# ProPrj_MN42_v2_2026-01-12.net
KiCad netlist of a schematic drawn in EasyEDA Pro
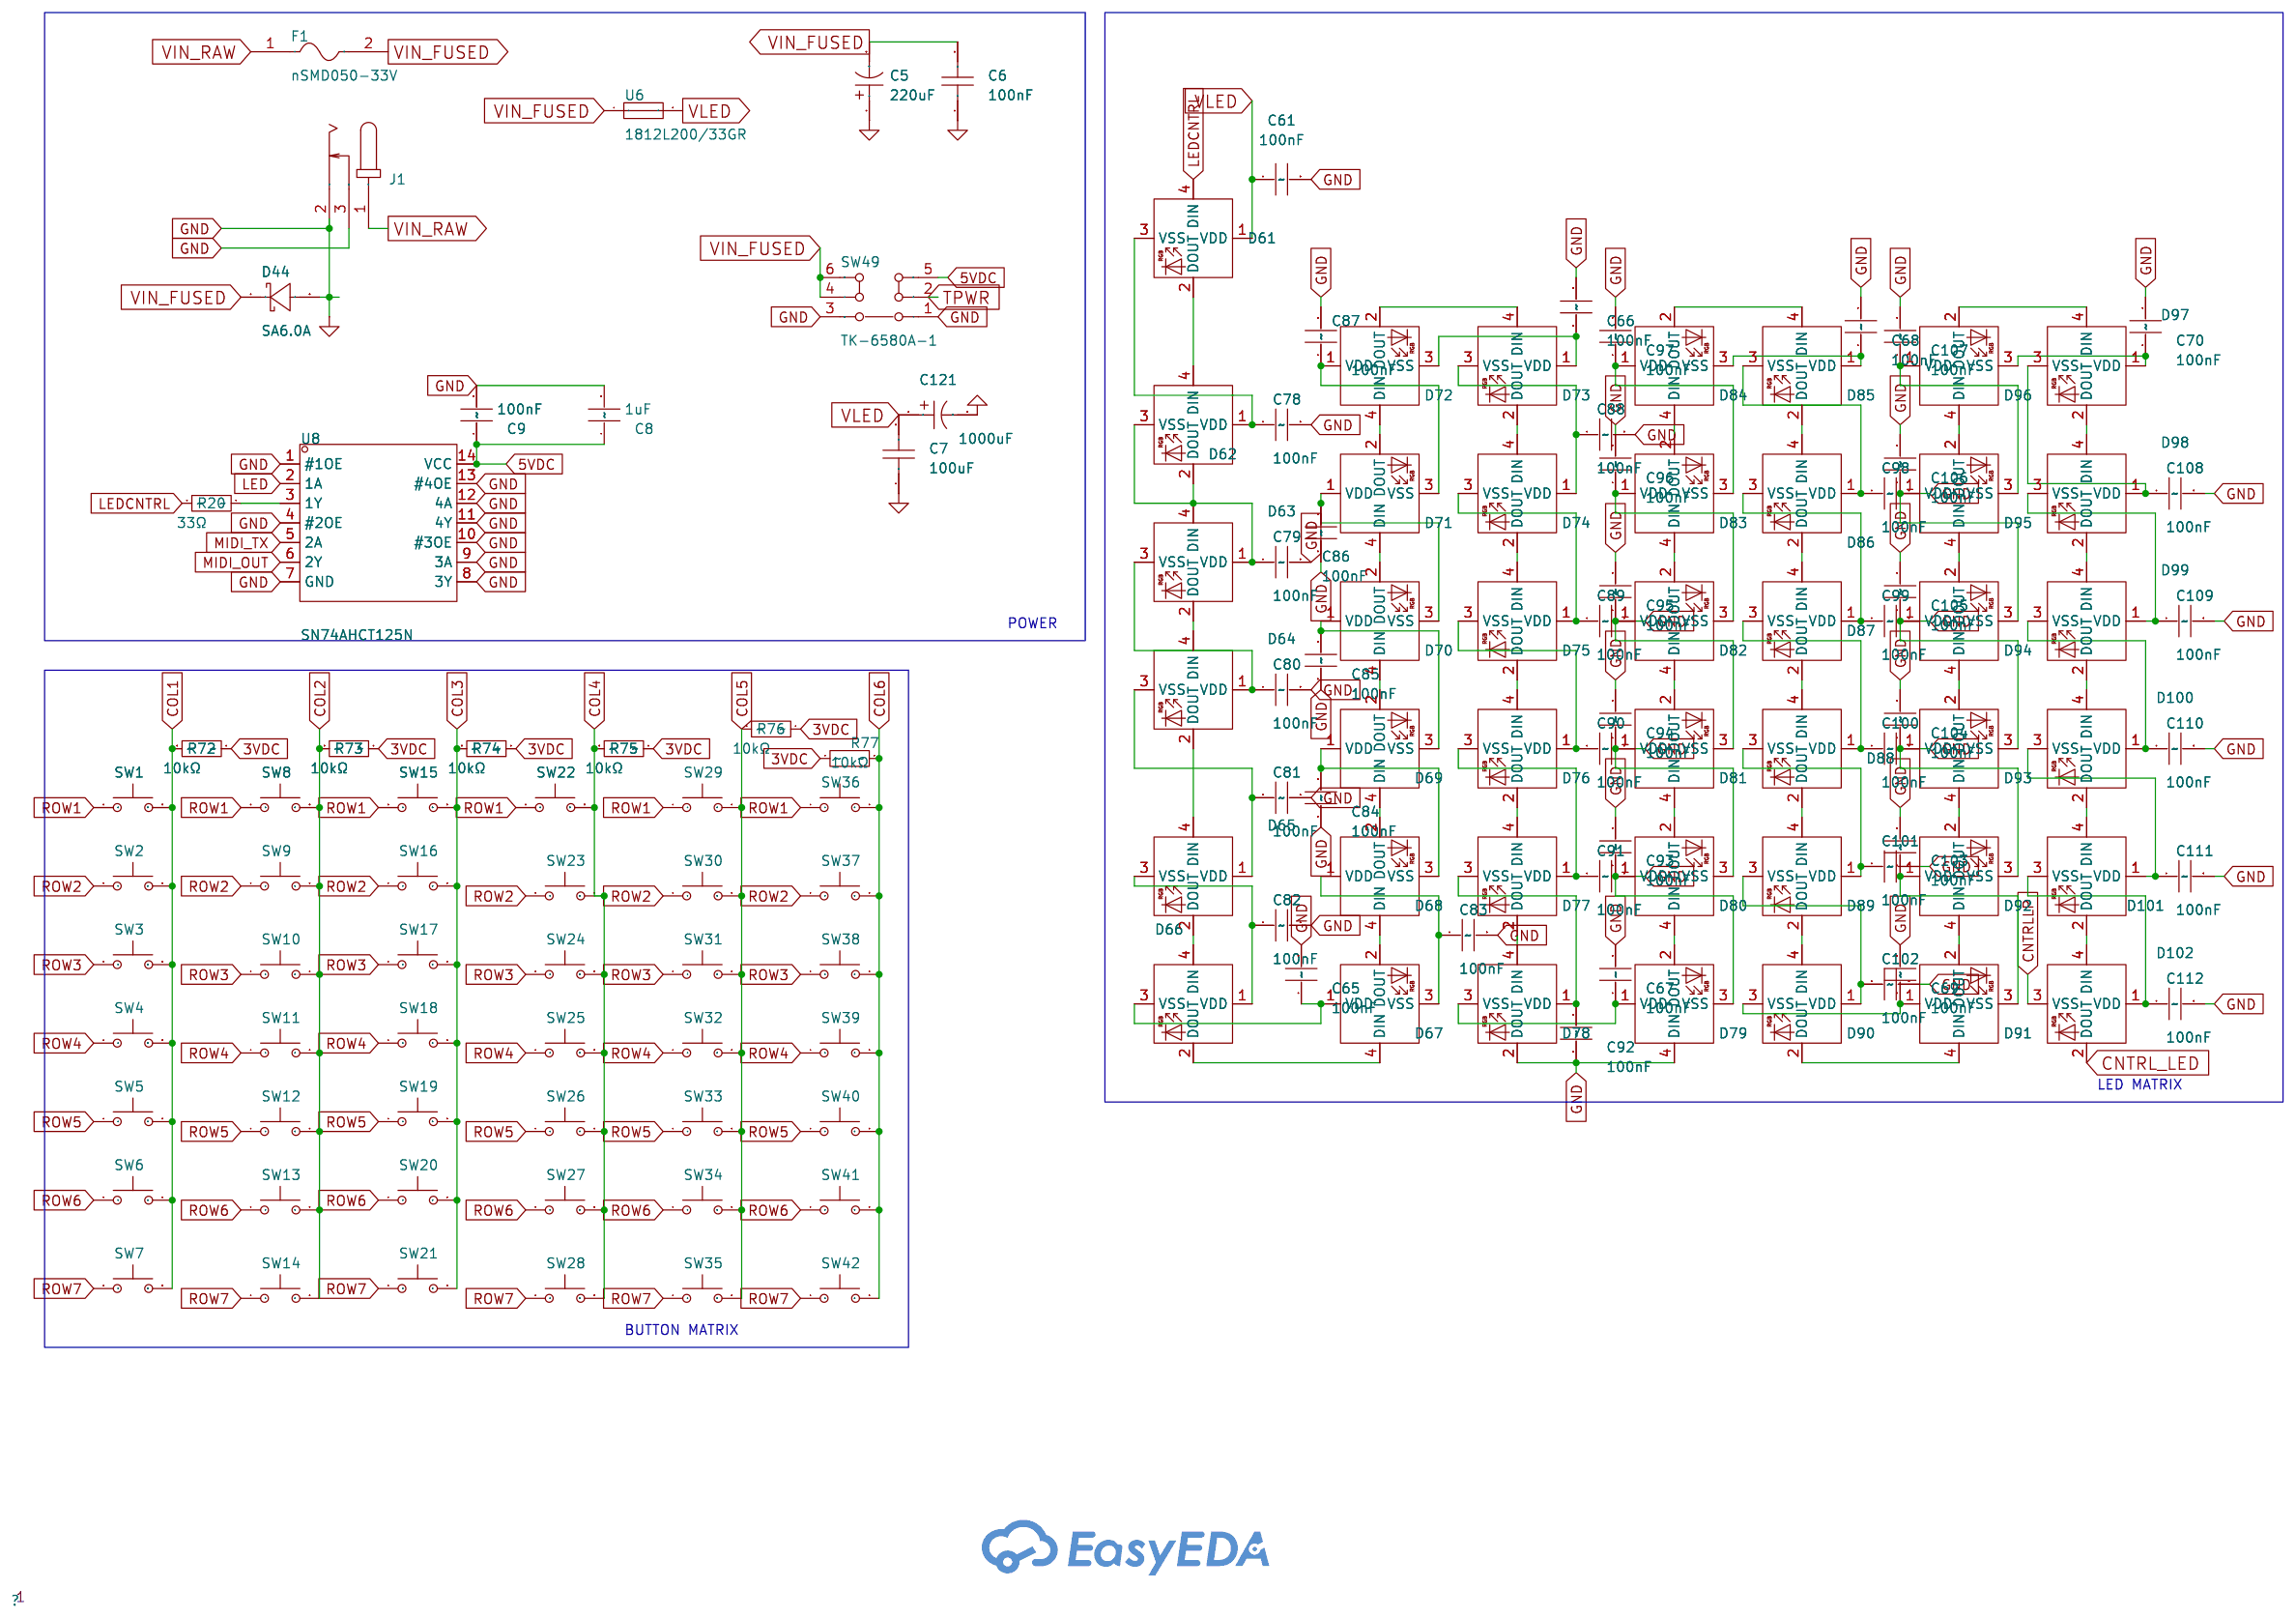
[diagram p0: PWR/BUTTON/LED]
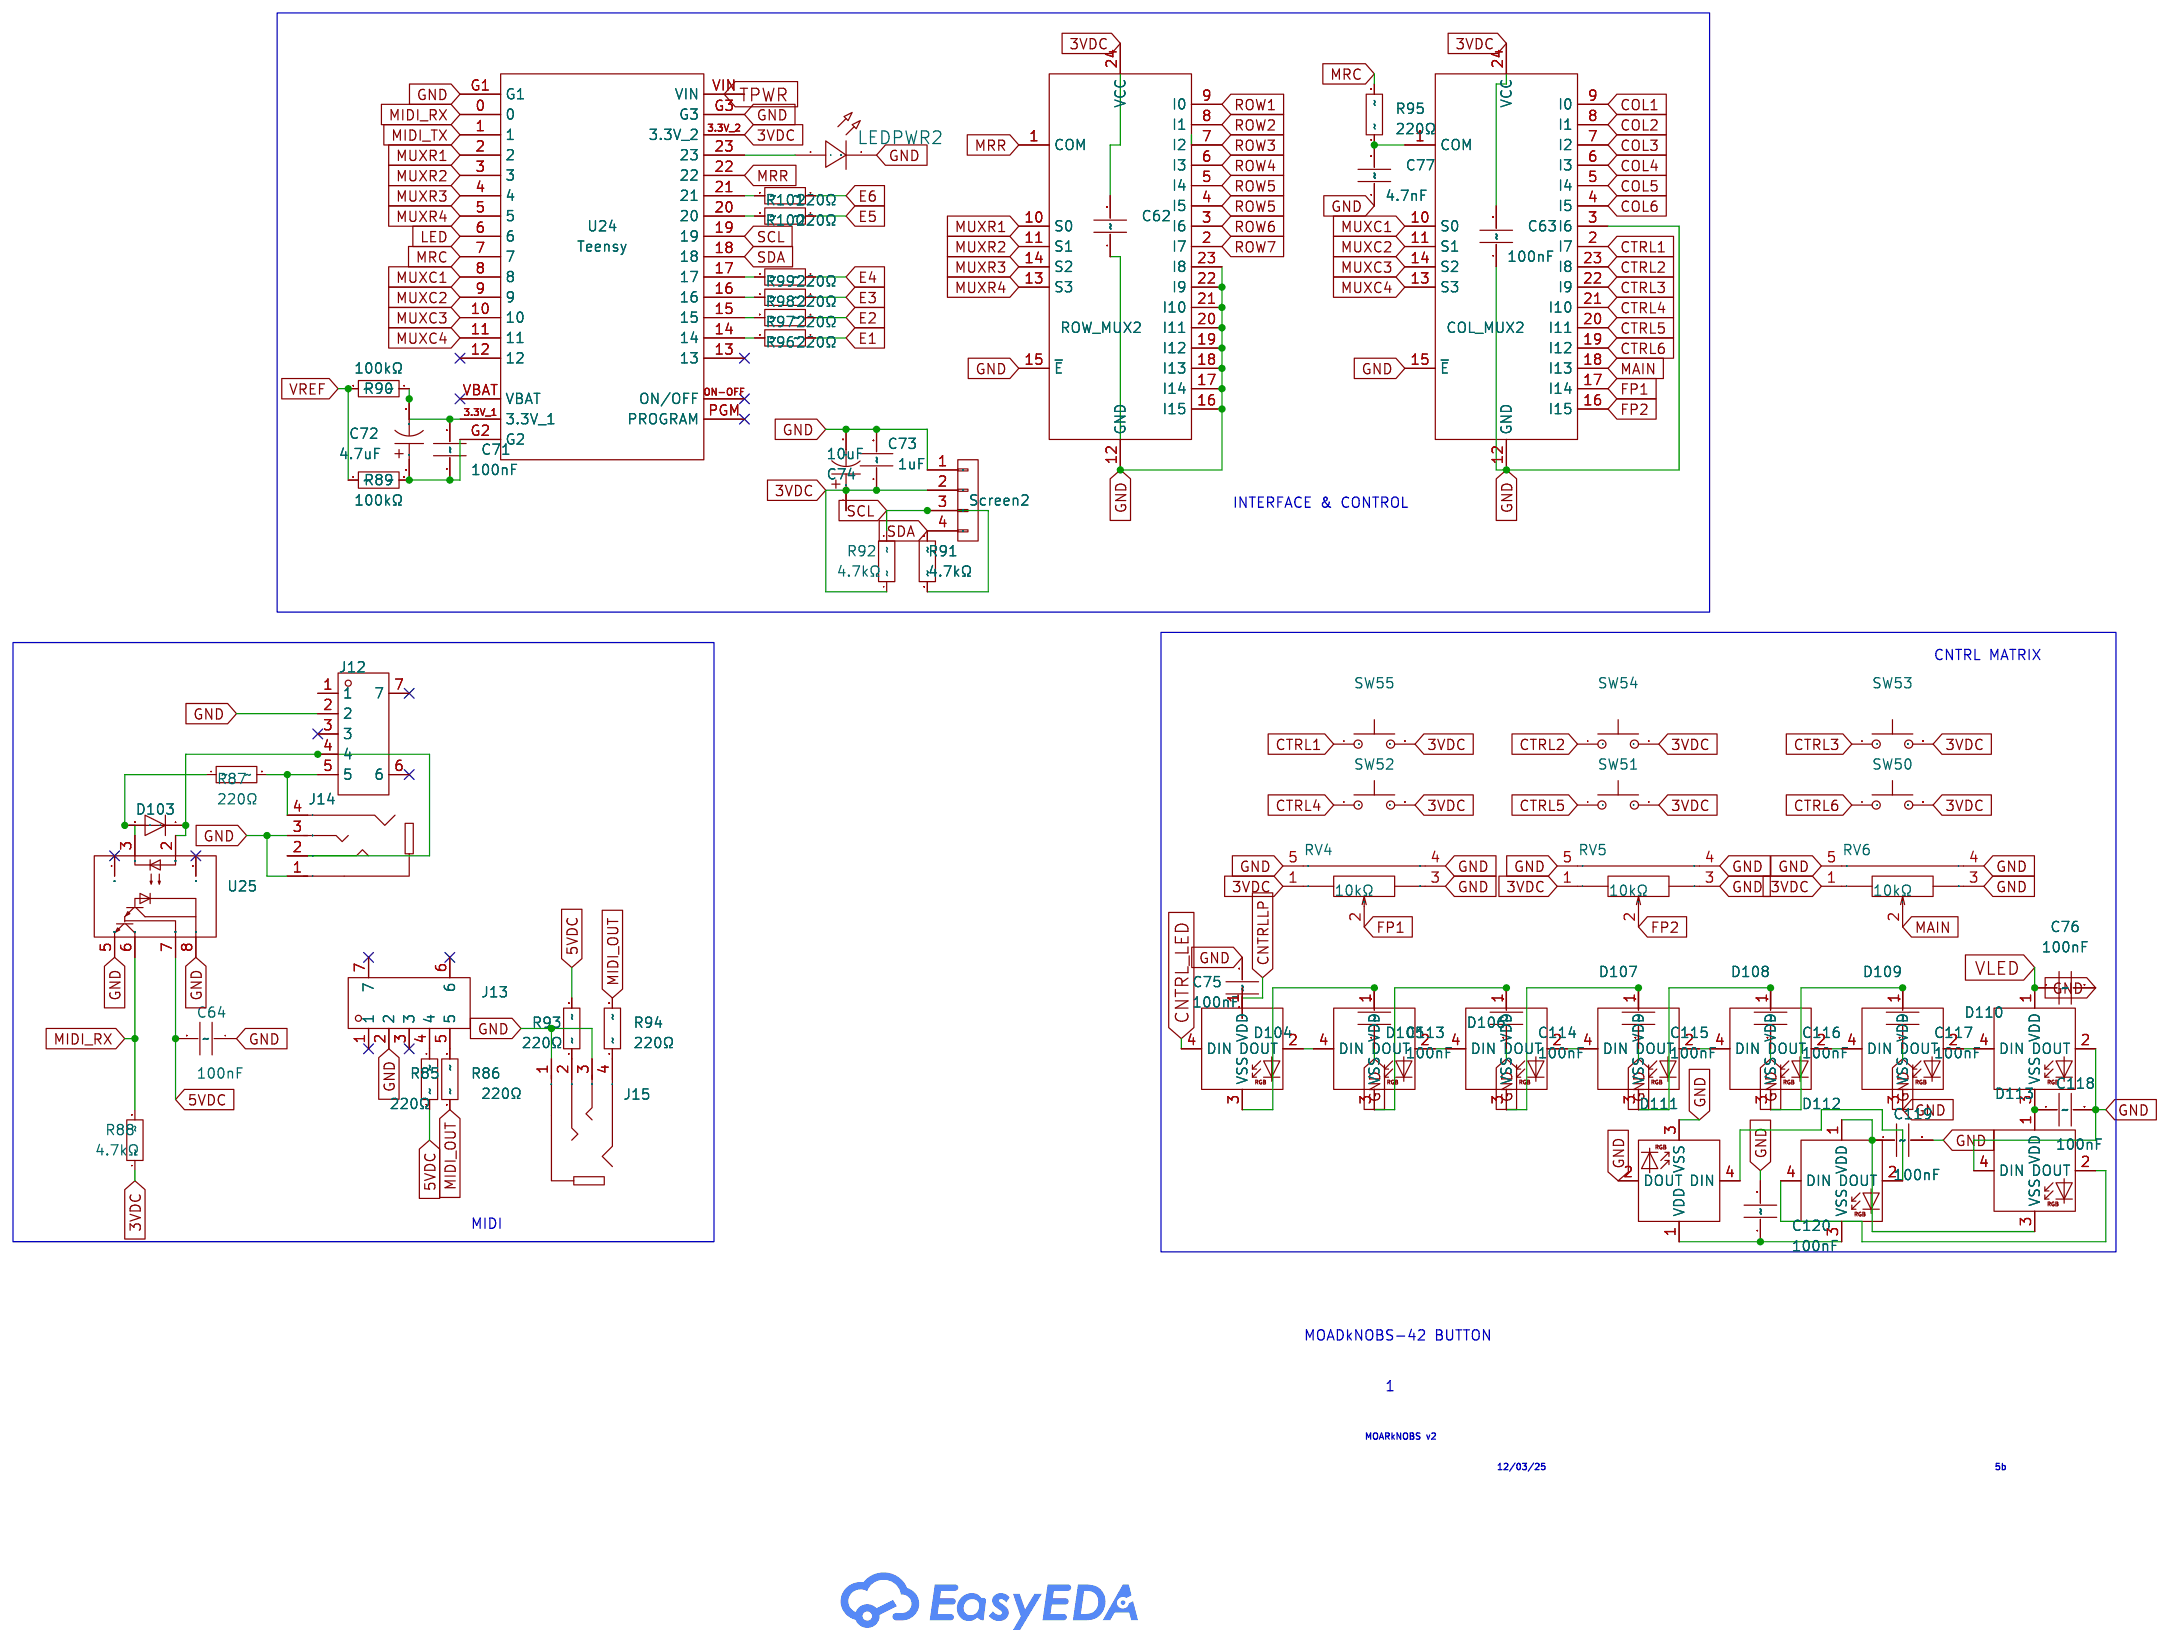
[diagram p1: INTERFACE/MIDI/CNTRL]
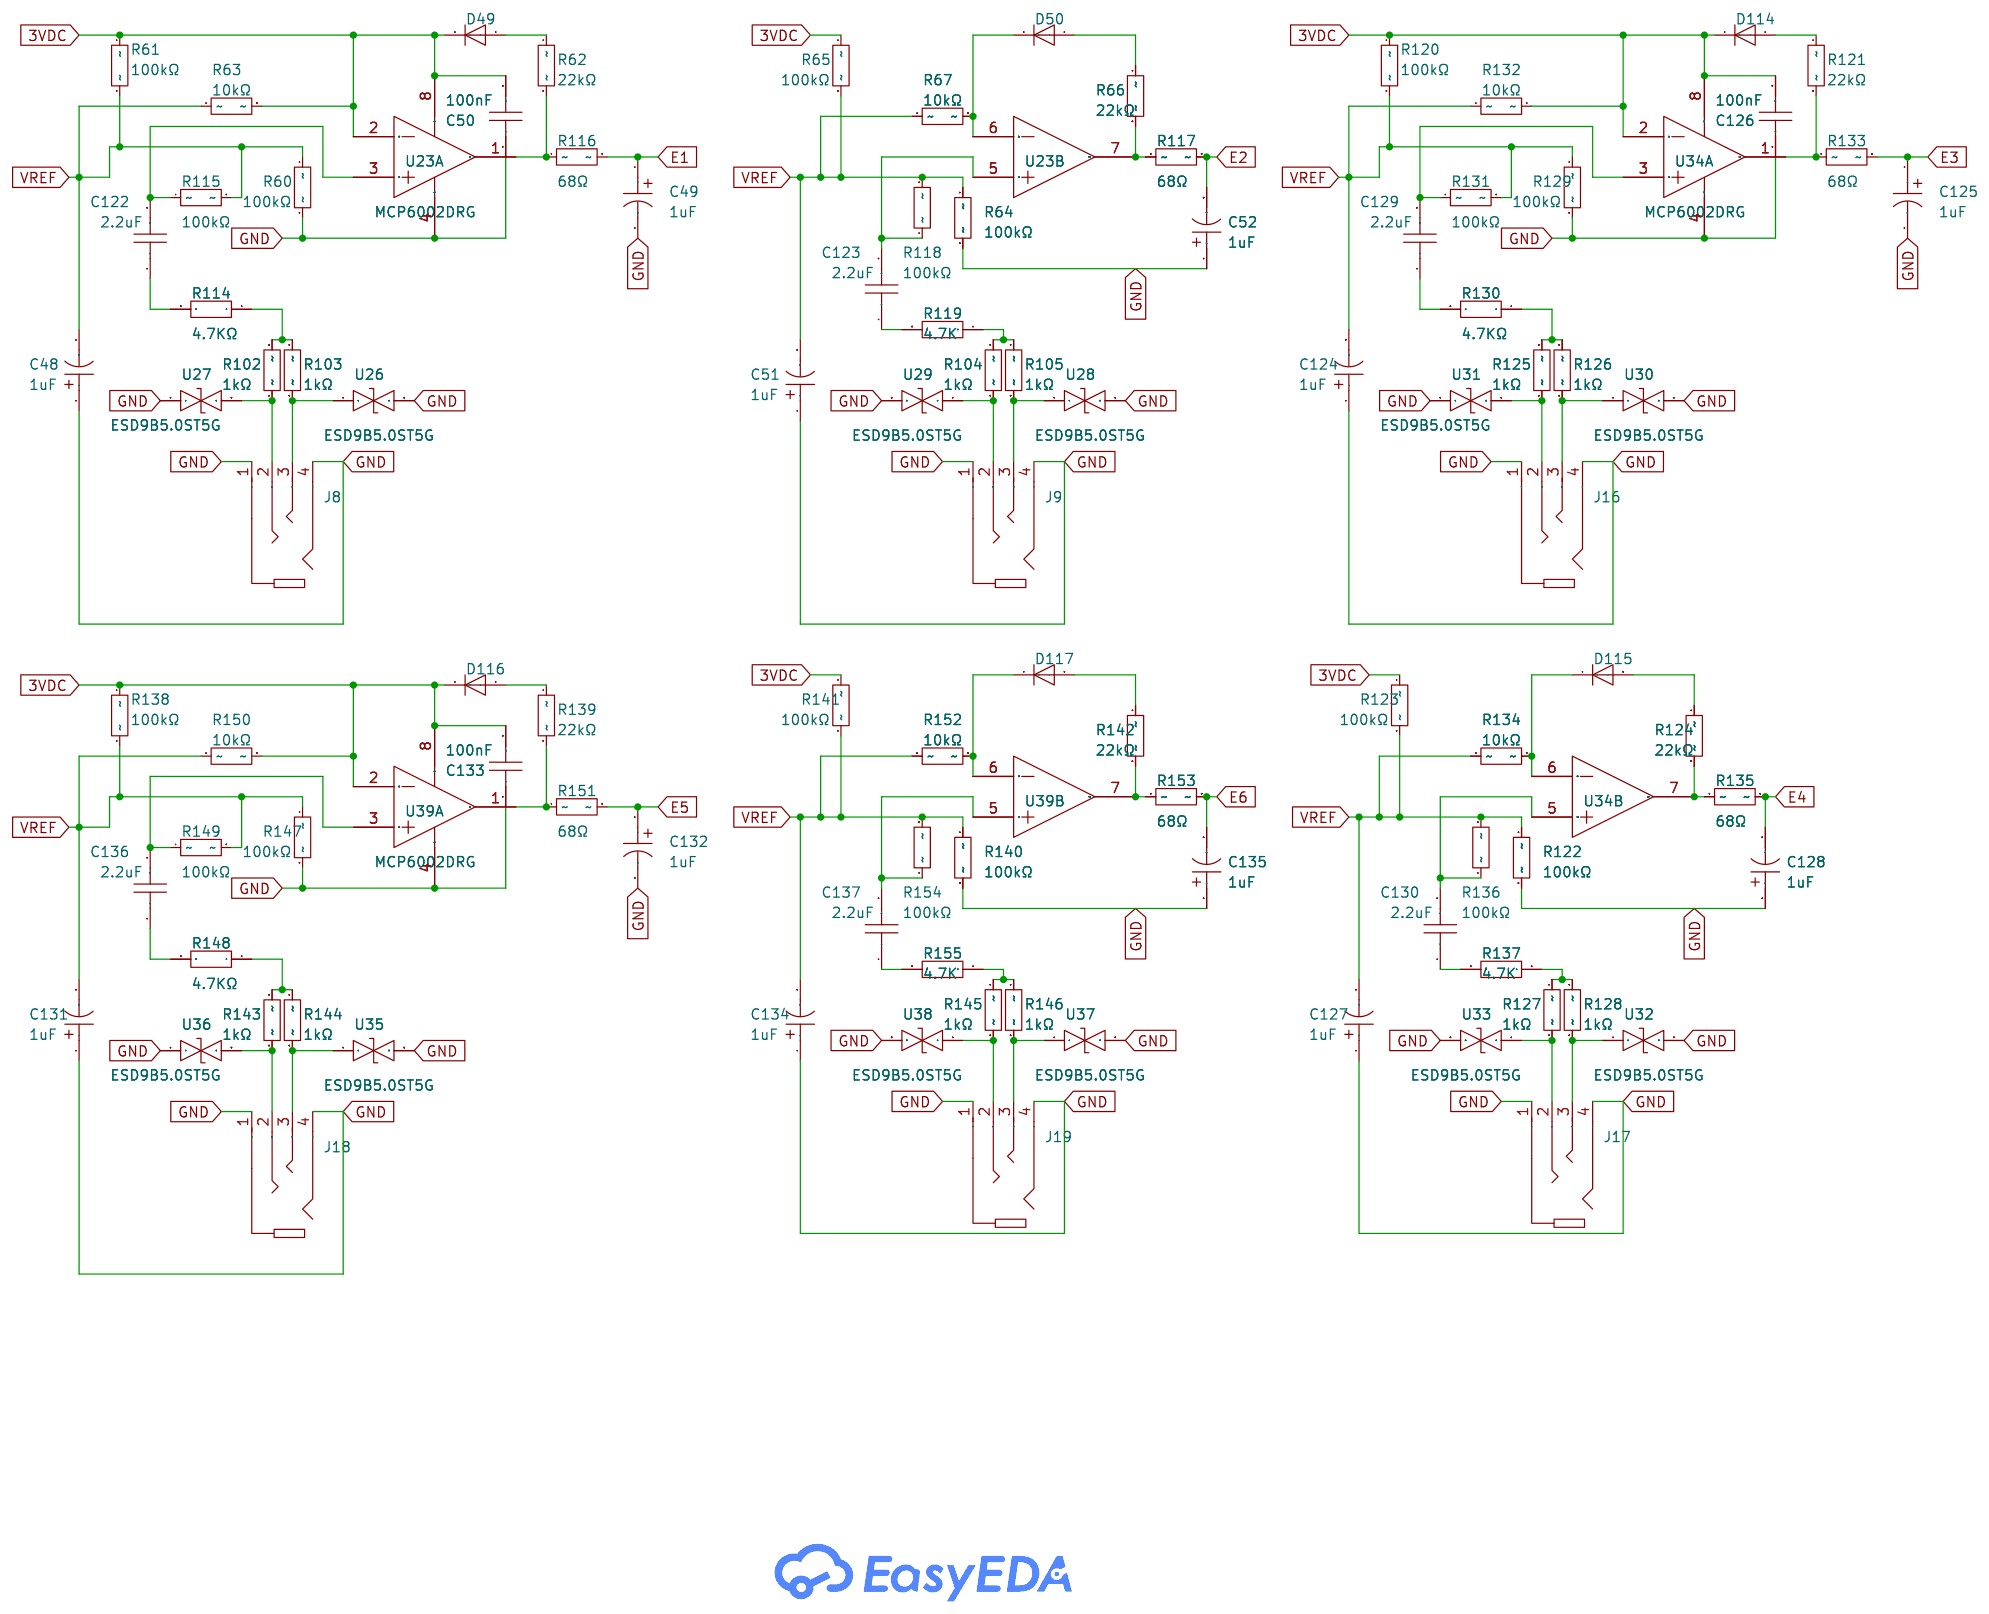
[diagram p2: ENVELOPE]

(export (version "E")
  (design (tool "Eeschema 10.0.6"))
  (components
    (comp (ref "C5")
      (value "220uF")
      (footprint "easyedapro:CAP-SMD_BD6.3-L6.6-W6.6-FD")
      (fields (field (name "Manufacturer Part") "189RV0019") (field (name "Manufacturer") "KNSCHA(科尼盛)"))
      (libsource (lib "easyedapro") (part "189RV0019"))
    )
    (comp (ref "C6")
      (value "100nF")
      (footprint "easyedapro:CAP-TH_L5.0-W2.5-P5.00-D1.0")
      (fields
        (field (name "Manufacturer Part") "CC1H104MC1FD3F6C10MF")
        (field (name "Manufacturer") "Dersonic(德尔创)")
      )
      (libsource (lib "easyedapro") (part "CC1H104MC1FD3F6C10MF"))
    )
    (comp (ref "C7")
      (value "100uF")
      (footprint "easyedapro:C1206")
      (description "Capacitance:100uF Tolerance:±20% Tolerance:±20% Voltage Rating:10V Temperature Coefficient:X5R")
      (fields
        (field (name "Manufacturer Part") "HGC1206R5107M100NSPJ")
        (field (name "Manufacturer") "Chinocera(华瓷)")
      )
      (libsource (lib "easyedapro") (part "HGC1206R5107M100NSPJ"))
    )
    (comp (ref "C8")
      (value "1uF")
      (footprint "easyedapro:Capacitor_THT:C_Disc_D3.4mm_W2.1mm_P2.50mm")
      (description "Capacitance:100nF Tolerance:±10% Tolerance:±10% Voltage Rating:63V Temperature Coefficient:-")
      (fields
        (field (name "Manufacturer Part") "CT4G-0805-2X1-63V-0.1μF-K")
        (field (name "Manufacturer") "TORCH(火炬)")
      )
      (libsource (lib "easyedapro") (part "Device_C"))
    )
    (comp (ref "C9")
      (value "100nF")
      (footprint "easyedapro:Capacitor_THT:C_Disc_D3.4mm_W2.1mm_P2.50mm")
      (description "Capacitance:100nF Tolerance:±10% Tolerance:±10% Voltage Rating:50V Temperature Coefficient:X7R")
      (fields
        (field (name "Manufacturer Part") "TCC0603X7R104K500CT")
        (field (name "Manufacturer") "CCTC(三环)")
      )
      (libsource (lib "easyedapro") (part "Device_C"))
    )
    (comp (ref "C61")
      (value "100nF")
      (footprint "easyedapro:Capacitor_THT:C_Disc_D3.4mm_W2.1mm_P2.50mm")
      (description "Capacitance:100nF Tolerance:±10% Tolerance:±10% Voltage Rating:50V Temperature Coefficient:X7R")
      (fields
        (field (name "Manufacturer Part") "TCC0603X7R104K500CT")
        (field (name "Manufacturer") "CCTC(三环)")
      )
      (libsource (lib "easyedapro") (part "Device_C"))
    )
    (comp (ref "C65")
      (value "100nF")
      (footprint "easyedapro:Capacitor_THT:C_Disc_D3.4mm_W2.1mm_P2.50mm")
      (description "Capacitance:100nF Tolerance:±10% Tolerance:±10% Voltage Rating:50V Temperature Coefficient:X7R")
      (fields
        (field (name "Manufacturer Part") "TCC0603X7R104K500CT")
        (field (name "Manufacturer") "CCTC(三环)")
      )
      (libsource (lib "easyedapro") (part "Device_C"))
    )
    (comp (ref "C66")
      (value "100nF")
      (footprint "easyedapro:Capacitor_THT:C_Disc_D3.4mm_W2.1mm_P2.50mm")
      (description "Capacitance:100nF Tolerance:±10% Tolerance:±10% Voltage Rating:50V Temperature Coefficient:X7R")
      (fields
        (field (name "Manufacturer Part") "TCC0603X7R104K500CT")
        (field (name "Manufacturer") "CCTC(三环)")
      )
      (libsource (lib "easyedapro") (part "Device_C"))
    )
    (comp (ref "C67")
      (value "100nF")
      (footprint "easyedapro:Capacitor_THT:C_Disc_D3.4mm_W2.1mm_P2.50mm")
      (description "Capacitance:100nF Tolerance:±10% Tolerance:±10% Voltage Rating:50V Temperature Coefficient:X7R")
      (fields
        (field (name "Manufacturer Part") "TCC0603X7R104K500CT")
        (field (name "Manufacturer") "CCTC(三环)")
      )
      (libsource (lib "easyedapro") (part "Device_C"))
    )
    (comp (ref "C68")
      (value "100nF")
      (footprint "easyedapro:Capacitor_THT:C_Disc_D3.4mm_W2.1mm_P2.50mm")
      (description "Capacitance:100nF Tolerance:±10% Tolerance:±10% Voltage Rating:50V Temperature Coefficient:X7R")
      (fields
        (field (name "Manufacturer Part") "TCC0603X7R104K500CT")
        (field (name "Manufacturer") "CCTC(三环)")
      )
      (libsource (lib "easyedapro") (part "Device_C"))
    )
    (comp (ref "C69")
      (value "100nF")
      (footprint "easyedapro:Capacitor_THT:C_Disc_D3.4mm_W2.1mm_P2.50mm")
      (description "Capacitance:100nF Tolerance:±10% Tolerance:±10% Voltage Rating:50V Temperature Coefficient:X7R")
      (fields
        (field (name "Manufacturer Part") "TCC0603X7R104K500CT")
        (field (name "Manufacturer") "CCTC(三环)")
      )
      (libsource (lib "easyedapro") (part "Device_C"))
    )
    (comp (ref "C70")
      (value "100nF")
      (footprint "easyedapro:Capacitor_THT:C_Disc_D3.4mm_W2.1mm_P2.50mm")
      (description "Capacitance:100nF Tolerance:±10% Tolerance:±10% Voltage Rating:50V Temperature Coefficient:X7R")
      (fields
        (field (name "Manufacturer Part") "TCC0603X7R104K500CT")
        (field (name "Manufacturer") "CCTC(三环)")
      )
      (libsource (lib "easyedapro") (part "Device_C"))
    )
    (comp (ref "C78")
      (value "100nF")
      (footprint "easyedapro:Capacitor_THT:C_Disc_D3.4mm_W2.1mm_P2.50mm")
      (description "Capacitance:100nF Tolerance:±10% Tolerance:±10% Voltage Rating:50V Temperature Coefficient:X7R")
      (fields
        (field (name "Manufacturer Part") "TCC0603X7R104K500CT")
        (field (name "Manufacturer") "CCTC(三环)")
      )
      (libsource (lib "easyedapro") (part "Device_C"))
    )
    (comp (ref "C79")
      (value "100nF")
      (footprint "easyedapro:Capacitor_THT:C_Disc_D3.4mm_W2.1mm_P2.50mm")
      (description "Capacitance:100nF Tolerance:±10% Tolerance:±10% Voltage Rating:50V Temperature Coefficient:X7R")
      (fields
        (field (name "Manufacturer Part") "TCC0603X7R104K500CT")
        (field (name "Manufacturer") "CCTC(三环)")
      )
      (libsource (lib "easyedapro") (part "Device_C"))
    )
    (comp (ref "C80")
      (value "100nF")
      (footprint "easyedapro:Capacitor_THT:C_Disc_D3.4mm_W2.1mm_P2.50mm")
      (description "Capacitance:100nF Tolerance:±10% Tolerance:±10% Voltage Rating:50V Temperature Coefficient:X7R")
      (fields
        (field (name "Manufacturer Part") "TCC0603X7R104K500CT")
        (field (name "Manufacturer") "CCTC(三环)")
      )
      (libsource (lib "easyedapro") (part "Device_C"))
    )
    (comp (ref "C81")
      (value "100nF")
      (footprint "easyedapro:Capacitor_THT:C_Disc_D3.4mm_W2.1mm_P2.50mm")
      (description "Capacitance:100nF Tolerance:±10% Tolerance:±10% Voltage Rating:50V Temperature Coefficient:X7R")
      (fields
        (field (name "Manufacturer Part") "TCC0603X7R104K500CT")
        (field (name "Manufacturer") "CCTC(三环)")
      )
      (libsource (lib "easyedapro") (part "Device_C"))
    )
    (comp (ref "C82")
      (value "100nF")
      (footprint "easyedapro:Capacitor_THT:C_Disc_D3.4mm_W2.1mm_P2.50mm")
      (description "Capacitance:100nF Tolerance:±10% Tolerance:±10% Voltage Rating:50V Temperature Coefficient:X7R")
      (fields
        (field (name "Manufacturer Part") "TCC0603X7R104K500CT")
        (field (name "Manufacturer") "CCTC(三环)")
      )
      (libsource (lib "easyedapro") (part "Device_C"))
    )
    (comp (ref "C83")
      (value "100nF")
      (footprint "easyedapro:Capacitor_THT:C_Disc_D3.4mm_W2.1mm_P2.50mm")
      (description "Capacitance:100nF Tolerance:±10% Tolerance:±10% Voltage Rating:50V Temperature Coefficient:X7R")
      (fields
        (field (name "Manufacturer Part") "TCC0603X7R104K500CT")
        (field (name "Manufacturer") "CCTC(三环)")
      )
      (libsource (lib "easyedapro") (part "Device_C"))
    )
    (comp (ref "C84")
      (value "100nF")
      (footprint "easyedapro:Capacitor_THT:C_Disc_D3.4mm_W2.1mm_P2.50mm")
      (description "Capacitance:100nF Tolerance:±10% Tolerance:±10% Voltage Rating:50V Temperature Coefficient:X7R")
      (fields
        (field (name "Manufacturer Part") "TCC0603X7R104K500CT")
        (field (name "Manufacturer") "CCTC(三环)")
      )
      (libsource (lib "easyedapro") (part "Device_C"))
    )
    (comp (ref "C85")
      (value "100nF")
      (footprint "easyedapro:Capacitor_THT:C_Disc_D3.4mm_W2.1mm_P2.50mm")
      (description "Capacitance:100nF Tolerance:±10% Tolerance:±10% Voltage Rating:50V Temperature Coefficient:X7R")
      (fields
        (field (name "Manufacturer Part") "TCC0603X7R104K500CT")
        (field (name "Manufacturer") "CCTC(三环)")
      )
      (libsource (lib "easyedapro") (part "Device_C"))
    )
    (comp (ref "C86")
      (value "100nF")
      (footprint "easyedapro:Capacitor_THT:C_Disc_D3.4mm_W2.1mm_P2.50mm")
      (description "Capacitance:100nF Tolerance:±10% Tolerance:±10% Voltage Rating:50V Temperature Coefficient:X7R")
      (fields
        (field (name "Manufacturer Part") "TCC0603X7R104K500CT")
        (field (name "Manufacturer") "CCTC(三环)")
      )
      (libsource (lib "easyedapro") (part "Device_C"))
    )
    (comp (ref "C87")
      (value "100nF")
      (footprint "easyedapro:Capacitor_THT:C_Disc_D3.4mm_W2.1mm_P2.50mm")
      (description "Capacitance:100nF Tolerance:±10% Tolerance:±10% Voltage Rating:50V Temperature Coefficient:X7R")
      (fields
        (field (name "Manufacturer Part") "TCC0603X7R104K500CT")
        (field (name "Manufacturer") "CCTC(三环)")
      )
      (libsource (lib "easyedapro") (part "Device_C"))
    )
    (comp (ref "C88")
      (value "100nF")
      (footprint "easyedapro:Capacitor_THT:C_Disc_D3.4mm_W2.1mm_P2.50mm")
      (description "Capacitance:100nF Tolerance:±10% Tolerance:±10% Voltage Rating:50V Temperature Coefficient:X7R")
      (fields
        (field (name "Manufacturer Part") "TCC0603X7R104K500CT")
        (field (name "Manufacturer") "CCTC(三环)")
      )
      (libsource (lib "easyedapro") (part "Device_C"))
    )
    (comp (ref "C89")
      (value "100nF")
      (footprint "easyedapro:Capacitor_THT:C_Disc_D3.4mm_W2.1mm_P2.50mm")
      (description "Capacitance:100nF Tolerance:±10% Tolerance:±10% Voltage Rating:50V Temperature Coefficient:X7R")
      (fields
        (field (name "Manufacturer Part") "TCC0603X7R104K500CT")
        (field (name "Manufacturer") "CCTC(三环)")
      )
      (libsource (lib "easyedapro") (part "Device_C"))
    )
    (comp (ref "C90")
      (value "100nF")
      (footprint "easyedapro:Capacitor_THT:C_Disc_D3.4mm_W2.1mm_P2.50mm")
      (description "Capacitance:100nF Tolerance:±10% Tolerance:±10% Voltage Rating:50V Temperature Coefficient:X7R")
      (fields
        (field (name "Manufacturer Part") "TCC0603X7R104K500CT")
        (field (name "Manufacturer") "CCTC(三环)")
      )
      (libsource (lib "easyedapro") (part "Device_C"))
    )
    (comp (ref "C91")
      (value "100nF")
      (footprint "easyedapro:Capacitor_THT:C_Disc_D3.4mm_W2.1mm_P2.50mm")
      (description "Capacitance:100nF Tolerance:±10% Tolerance:±10% Voltage Rating:50V Temperature Coefficient:X7R")
      (fields
        (field (name "Manufacturer Part") "TCC0603X7R104K500CT")
        (field (name "Manufacturer") "CCTC(三环)")
      )
      (libsource (lib "easyedapro") (part "Device_C"))
    )
    (comp (ref "C92")
      (value "100nF")
      (footprint "easyedapro:Capacitor_THT:C_Disc_D3.4mm_W2.1mm_P2.50mm")
      (description "Capacitance:100nF Tolerance:±10% Tolerance:±10% Voltage Rating:50V Temperature Coefficient:X7R")
      (fields
        (field (name "Manufacturer Part") "TCC0603X7R104K500CT")
        (field (name "Manufacturer") "CCTC(三环)")
      )
      (libsource (lib "easyedapro") (part "Device_C"))
    )
    (comp (ref "C93")
      (value "100nF")
      (footprint "easyedapro:Capacitor_THT:C_Disc_D3.4mm_W2.1mm_P2.50mm")
      (description "Capacitance:100nF Tolerance:±10% Tolerance:±10% Voltage Rating:50V Temperature Coefficient:X7R")
      (fields
        (field (name "Manufacturer Part") "TCC0603X7R104K500CT")
        (field (name "Manufacturer") "CCTC(三环)")
      )
      (libsource (lib "easyedapro") (part "Device_C"))
    )
    (comp (ref "C94")
      (value "100nF")
      (footprint "easyedapro:Capacitor_THT:C_Disc_D3.4mm_W2.1mm_P2.50mm")
      (description "Capacitance:100nF Tolerance:±10% Tolerance:±10% Voltage Rating:50V Temperature Coefficient:X7R")
      (fields
        (field (name "Manufacturer Part") "TCC0603X7R104K500CT")
        (field (name "Manufacturer") "CCTC(三环)")
      )
      (libsource (lib "easyedapro") (part "Device_C"))
    )
    (comp (ref "C95")
      (value "100nF")
      (footprint "easyedapro:Capacitor_THT:C_Disc_D3.4mm_W2.1mm_P2.50mm")
      (description "Capacitance:100nF Tolerance:±10% Tolerance:±10% Voltage Rating:50V Temperature Coefficient:X7R")
      (fields
        (field (name "Manufacturer Part") "TCC0603X7R104K500CT")
        (field (name "Manufacturer") "CCTC(三环)")
      )
      (libsource (lib "easyedapro") (part "Device_C"))
    )
    (comp (ref "C96")
      (value "100nF")
      (footprint "easyedapro:Capacitor_THT:C_Disc_D3.4mm_W2.1mm_P2.50mm")
      (description "Capacitance:100nF Tolerance:±10% Tolerance:±10% Voltage Rating:50V Temperature Coefficient:X7R")
      (fields
        (field (name "Manufacturer Part") "TCC0603X7R104K500CT")
        (field (name "Manufacturer") "CCTC(三环)")
      )
      (libsource (lib "easyedapro") (part "Device_C"))
    )
    (comp (ref "C97")
      (value "100nF")
      (footprint "easyedapro:Capacitor_THT:C_Disc_D3.4mm_W2.1mm_P2.50mm")
      (description "Capacitance:100nF Tolerance:±10% Tolerance:±10% Voltage Rating:50V Temperature Coefficient:X7R")
      (fields
        (field (name "Manufacturer Part") "TCC0603X7R104K500CT")
        (field (name "Manufacturer") "CCTC(三环)")
      )
      (libsource (lib "easyedapro") (part "Device_C"))
    )
    (comp (ref "C98")
      (value "100nF")
      (footprint "easyedapro:Capacitor_THT:C_Disc_D3.4mm_W2.1mm_P2.50mm")
      (description "Capacitance:100nF Tolerance:±10% Tolerance:±10% Voltage Rating:50V Temperature Coefficient:X7R")
      (fields
        (field (name "Manufacturer Part") "TCC0603X7R104K500CT")
        (field (name "Manufacturer") "CCTC(三环)")
      )
      (libsource (lib "easyedapro") (part "Device_C"))
    )
    (comp (ref "C99")
      (value "100nF")
      (footprint "easyedapro:Capacitor_THT:C_Disc_D3.4mm_W2.1mm_P2.50mm")
      (description "Capacitance:100nF Tolerance:±10% Tolerance:±10% Voltage Rating:50V Temperature Coefficient:X7R")
      (fields
        (field (name "Manufacturer Part") "TCC0603X7R104K500CT")
        (field (name "Manufacturer") "CCTC(三环)")
      )
      (libsource (lib "easyedapro") (part "Device_C"))
    )
    (comp (ref "C100")
      (value "100nF")
      (footprint "easyedapro:Capacitor_THT:C_Disc_D3.4mm_W2.1mm_P2.50mm")
      (description "Capacitance:100nF Tolerance:±10% Tolerance:±10% Voltage Rating:50V Temperature Coefficient:X7R")
      (fields
        (field (name "Manufacturer Part") "TCC0603X7R104K500CT")
        (field (name "Manufacturer") "CCTC(三环)")
      )
      (libsource (lib "easyedapro") (part "Device_C"))
    )
    (comp (ref "C101")
      (value "100nF")
      (footprint "easyedapro:Capacitor_THT:C_Disc_D3.4mm_W2.1mm_P2.50mm")
      (description "Capacitance:100nF Tolerance:±10% Tolerance:±10% Voltage Rating:50V Temperature Coefficient:X7R")
      (fields
        (field (name "Manufacturer Part") "TCC0603X7R104K500CT")
        (field (name "Manufacturer") "CCTC(三环)")
      )
      (libsource (lib "easyedapro") (part "Device_C"))
    )
    (comp (ref "C102")
      (value "100nF")
      (footprint "easyedapro:Capacitor_THT:C_Disc_D3.4mm_W2.1mm_P2.50mm")
      (description "Capacitance:100nF Tolerance:±10% Tolerance:±10% Voltage Rating:50V Temperature Coefficient:X7R")
      (fields
        (field (name "Manufacturer Part") "TCC0603X7R104K500CT")
        (field (name "Manufacturer") "CCTC(三环)")
      )
      (libsource (lib "easyedapro") (part "Device_C"))
    )
    (comp (ref "C103")
      (value "100nF")
      (footprint "easyedapro:Capacitor_THT:C_Disc_D3.4mm_W2.1mm_P2.50mm")
      (description "Capacitance:100nF Tolerance:±10% Tolerance:±10% Voltage Rating:50V Temperature Coefficient:X7R")
      (fields
        (field (name "Manufacturer Part") "TCC0603X7R104K500CT")
        (field (name "Manufacturer") "CCTC(三环)")
      )
      (libsource (lib "easyedapro") (part "Device_C"))
    )
    (comp (ref "C104")
      (value "100nF")
      (footprint "easyedapro:Capacitor_THT:C_Disc_D3.4mm_W2.1mm_P2.50mm")
      (description "Capacitance:100nF Tolerance:±10% Tolerance:±10% Voltage Rating:50V Temperature Coefficient:X7R")
      (fields
        (field (name "Manufacturer Part") "TCC0603X7R104K500CT")
        (field (name "Manufacturer") "CCTC(三环)")
      )
      (libsource (lib "easyedapro") (part "Device_C"))
    )
    (comp (ref "C105")
      (value "100nF")
      (footprint "easyedapro:Capacitor_THT:C_Disc_D3.4mm_W2.1mm_P2.50mm")
      (description "Capacitance:100nF Tolerance:±10% Tolerance:±10% Voltage Rating:50V Temperature Coefficient:X7R")
      (fields
        (field (name "Manufacturer Part") "TCC0603X7R104K500CT")
        (field (name "Manufacturer") "CCTC(三环)")
      )
      (libsource (lib "easyedapro") (part "Device_C"))
    )
    (comp (ref "C106")
      (value "100nF")
      (footprint "easyedapro:Capacitor_THT:C_Disc_D3.4mm_W2.1mm_P2.50mm")
      (description "Capacitance:100nF Tolerance:±10% Tolerance:±10% Voltage Rating:50V Temperature Coefficient:X7R")
      (fields
        (field (name "Manufacturer Part") "TCC0603X7R104K500CT")
        (field (name "Manufacturer") "CCTC(三环)")
      )
      (libsource (lib "easyedapro") (part "Device_C"))
    )
    (comp (ref "C107")
      (value "100nF")
      (footprint "easyedapro:Capacitor_THT:C_Disc_D3.4mm_W2.1mm_P2.50mm")
      (description "Capacitance:100nF Tolerance:±10% Tolerance:±10% Voltage Rating:50V Temperature Coefficient:X7R")
      (fields
        (field (name "Manufacturer Part") "TCC0603X7R104K500CT")
        (field (name "Manufacturer") "CCTC(三环)")
      )
      (libsource (lib "easyedapro") (part "Device_C"))
    )
    (comp (ref "C108")
      (value "100nF")
      (footprint "easyedapro:Capacitor_THT:C_Disc_D3.4mm_W2.1mm_P2.50mm")
      (description "Capacitance:100nF Tolerance:±10% Tolerance:±10% Voltage Rating:50V Temperature Coefficient:X7R")
      (fields
        (field (name "Manufacturer Part") "TCC0603X7R104K500CT")
        (field (name "Manufacturer") "CCTC(三环)")
      )
      (libsource (lib "easyedapro") (part "Device_C"))
    )
    (comp (ref "C109")
      (value "100nF")
      (footprint "easyedapro:Capacitor_THT:C_Disc_D3.4mm_W2.1mm_P2.50mm")
      (description "Capacitance:100nF Tolerance:±10% Tolerance:±10% Voltage Rating:50V Temperature Coefficient:X7R")
      (fields
        (field (name "Manufacturer Part") "TCC0603X7R104K500CT")
        (field (name "Manufacturer") "CCTC(三环)")
      )
      (libsource (lib "easyedapro") (part "Device_C"))
    )
    (comp (ref "C110")
      (value "100nF")
      (footprint "easyedapro:Capacitor_THT:C_Disc_D3.4mm_W2.1mm_P2.50mm")
      (description "Capacitance:100nF Tolerance:±10% Tolerance:±10% Voltage Rating:50V Temperature Coefficient:X7R")
      (fields
        (field (name "Manufacturer Part") "TCC0603X7R104K500CT")
        (field (name "Manufacturer") "CCTC(三环)")
      )
      (libsource (lib "easyedapro") (part "Device_C"))
    )
    (comp (ref "C111")
      (value "100nF")
      (footprint "easyedapro:Capacitor_THT:C_Disc_D3.4mm_W2.1mm_P2.50mm")
      (description "Capacitance:100nF Tolerance:±10% Tolerance:±10% Voltage Rating:50V Temperature Coefficient:X7R")
      (fields
        (field (name "Manufacturer Part") "TCC0603X7R104K500CT")
        (field (name "Manufacturer") "CCTC(三环)")
      )
      (libsource (lib "easyedapro") (part "Device_C"))
    )
    (comp (ref "C112")
      (value "100nF")
      (footprint "easyedapro:Capacitor_THT:C_Disc_D3.4mm_W2.1mm_P2.50mm")
      (description "Capacitance:100nF Tolerance:±10% Tolerance:±10% Voltage Rating:50V Temperature Coefficient:X7R")
      (fields
        (field (name "Manufacturer Part") "TCC0603X7R104K500CT")
        (field (name "Manufacturer") "CCTC(三环)")
      )
      (libsource (lib "easyedapro") (part "Device_C"))
    )
    (comp (ref "C121")
      (value "1000uF")
      (footprint "easyedapro:CAP-TH_BD8.0-P3.50-D0.6-FD")
      (fields (field (name "Manufacturer Part") "NPXD0901B102MJTM") (field (name "Manufacturer") "Ymin(永铭)"))
      (libsource (lib "easyedapro") (part "NPXD0901B102MJTM"))
    )
    (comp (ref "D44")
      (value "SA6.0A")
      (footprint "easyedapro:DO-15_BD3.1-L6.7-P10.70-D0.8-RD")
      (fields (field (name "Manufacturer") "Littelfuse(美国力特)"))
      (libsource (lib "easyedapro") (part "SA6.0A_C1973281"))
    )
    (comp (ref "D61")
      (value "XL-5050RGBC-WS2812B")
      (footprint "easyedapro:LED_SMD:LED_WS2812B_PLCC4_5.0x5.0mm_P3.2mm")
      (fields (field (name "Manufacturer") "XINGLIGHT(成兴光)"))
      (libsource (lib "easyedapro") (part "LED_WS2812B"))
    )
    (comp (ref "D62")
      (value "XL-5050RGBC-WS2812B")
      (footprint "easyedapro:LED_SMD:LED_WS2812B_PLCC4_5.0x5.0mm_P3.2mm")
      (fields (field (name "Manufacturer") "XINGLIGHT(成兴光)"))
      (libsource (lib "easyedapro") (part "LED_WS2812B"))
    )
    (comp (ref "D63")
      (value "XL-5050RGBC-WS2812B")
      (footprint "easyedapro:LED_SMD:LED_WS2812B_PLCC4_5.0x5.0mm_P3.2mm")
      (fields (field (name "Manufacturer") "XINGLIGHT(成兴光)"))
      (libsource (lib "easyedapro") (part "LED_WS2812B"))
    )
    (comp (ref "D64")
      (value "XL-5050RGBC-WS2812B")
      (footprint "easyedapro:LED_SMD:LED_WS2812B_PLCC4_5.0x5.0mm_P3.2mm")
      (fields (field (name "Manufacturer") "XINGLIGHT(成兴光)"))
      (libsource (lib "easyedapro") (part "LED_WS2812B"))
    )
    (comp (ref "D65")
      (value "XL-5050RGBC-WS2812B")
      (footprint "easyedapro:LED_SMD:LED_WS2812B_PLCC4_5.0x5.0mm_P3.2mm")
      (fields (field (name "Manufacturer") "XINGLIGHT(成兴光)"))
      (libsource (lib "easyedapro") (part "LED_WS2812B"))
    )
    (comp (ref "D66")
      (value "XL-5050RGBC-WS2812B")
      (footprint "easyedapro:LED_SMD:LED_WS2812B_PLCC4_5.0x5.0mm_P3.2mm")
      (fields (field (name "Manufacturer") "XINGLIGHT(成兴光)"))
      (libsource (lib "easyedapro") (part "LED_WS2812B"))
    )
    (comp (ref "D67")
      (value "XL-5050RGBC-WS2812B")
      (footprint "easyedapro:LED_SMD:LED_WS2812B_PLCC4_5.0x5.0mm_P3.2mm")
      (fields (field (name "Manufacturer") "XINGLIGHT(成兴光)"))
      (libsource (lib "easyedapro") (part "LED_WS2812B"))
    )
    (comp (ref "D68")
      (value "XL-5050RGBC-WS2812B")
      (footprint "easyedapro:LED_SMD:LED_WS2812B_PLCC4_5.0x5.0mm_P3.2mm")
      (fields (field (name "Manufacturer") "XINGLIGHT(成兴光)"))
      (libsource (lib "easyedapro") (part "LED_WS2812B"))
    )
    (comp (ref "D69")
      (value "XL-5050RGBC-WS2812B")
      (footprint "easyedapro:LED_SMD:LED_WS2812B_PLCC4_5.0x5.0mm_P3.2mm")
      (fields (field (name "Manufacturer") "XINGLIGHT(成兴光)"))
      (libsource (lib "easyedapro") (part "LED_WS2812B"))
    )
    (comp (ref "D70")
      (value "XL-5050RGBC-WS2812B")
      (footprint "easyedapro:LED_SMD:LED_WS2812B_PLCC4_5.0x5.0mm_P3.2mm")
      (fields (field (name "Manufacturer") "XINGLIGHT(成兴光)"))
      (libsource (lib "easyedapro") (part "LED_WS2812B"))
    )
    (comp (ref "D71")
      (value "XL-5050RGBC-WS2812B")
      (footprint "easyedapro:LED_SMD:LED_WS2812B_PLCC4_5.0x5.0mm_P3.2mm")
      (fields (field (name "Manufacturer") "XINGLIGHT(成兴光)"))
      (libsource (lib "easyedapro") (part "LED_WS2812B"))
    )
    (comp (ref "D72")
      (value "XL-5050RGBC-WS2812B")
      (footprint "easyedapro:LED_SMD:LED_WS2812B_PLCC4_5.0x5.0mm_P3.2mm")
      (fields (field (name "Manufacturer") "XINGLIGHT(成兴光)"))
      (libsource (lib "easyedapro") (part "LED_WS2812B"))
    )
    (comp (ref "D73")
      (value "XL-5050RGBC-WS2812B")
      (footprint "easyedapro:LED_SMD:LED_WS2812B_PLCC4_5.0x5.0mm_P3.2mm")
      (fields (field (name "Manufacturer") "XINGLIGHT(成兴光)"))
      (libsource (lib "easyedapro") (part "LED_WS2812B"))
    )
    (comp (ref "D74")
      (value "XL-5050RGBC-WS2812B")
      (footprint "easyedapro:LED_SMD:LED_WS2812B_PLCC4_5.0x5.0mm_P3.2mm")
      (fields (field (name "Manufacturer") "XINGLIGHT(成兴光)"))
      (libsource (lib "easyedapro") (part "LED_WS2812B"))
    )
    (comp (ref "D75")
      (value "XL-5050RGBC-WS2812B")
      (footprint "easyedapro:LED_SMD:LED_WS2812B_PLCC4_5.0x5.0mm_P3.2mm")
      (fields (field (name "Manufacturer") "XINGLIGHT(成兴光)"))
      (libsource (lib "easyedapro") (part "LED_WS2812B"))
    )
    (comp (ref "D76")
      (value "XL-5050RGBC-WS2812B")
      (footprint "easyedapro:LED_SMD:LED_WS2812B_PLCC4_5.0x5.0mm_P3.2mm")
      (fields (field (name "Manufacturer") "XINGLIGHT(成兴光)"))
      (libsource (lib "easyedapro") (part "LED_WS2812B"))
    )
    (comp (ref "D77")
      (value "XL-5050RGBC-WS2812B")
      (footprint "easyedapro:LED_SMD:LED_WS2812B_PLCC4_5.0x5.0mm_P3.2mm")
      (fields (field (name "Manufacturer") "XINGLIGHT(成兴光)"))
      (libsource (lib "easyedapro") (part "LED_WS2812B"))
    )
    (comp (ref "D78")
      (value "XL-5050RGBC-WS2812B")
      (footprint "easyedapro:LED_SMD:LED_WS2812B_PLCC4_5.0x5.0mm_P3.2mm")
      (fields (field (name "Manufacturer") "XINGLIGHT(成兴光)"))
      (libsource (lib "easyedapro") (part "LED_WS2812B"))
    )
    (comp (ref "D79")
      (value "XL-5050RGBC-WS2812B")
      (footprint "easyedapro:LED_SMD:LED_WS2812B_PLCC4_5.0x5.0mm_P3.2mm")
      (fields (field (name "Manufacturer") "XINGLIGHT(成兴光)"))
      (libsource (lib "easyedapro") (part "LED_WS2812B"))
    )
    (comp (ref "D80")
      (value "XL-5050RGBC-WS2812B")
      (footprint "easyedapro:LED_SMD:LED_WS2812B_PLCC4_5.0x5.0mm_P3.2mm")
      (fields (field (name "Manufacturer") "XINGLIGHT(成兴光)"))
      (libsource (lib "easyedapro") (part "LED_WS2812B"))
    )
    (comp (ref "D81")
      (value "XL-5050RGBC-WS2812B")
      (footprint "easyedapro:LED_SMD:LED_WS2812B_PLCC4_5.0x5.0mm_P3.2mm")
      (fields (field (name "Manufacturer") "XINGLIGHT(成兴光)"))
      (libsource (lib "easyedapro") (part "LED_WS2812B"))
    )
    (comp (ref "D82")
      (value "XL-5050RGBC-WS2812B")
      (footprint "easyedapro:LED_SMD:LED_WS2812B_PLCC4_5.0x5.0mm_P3.2mm")
      (fields (field (name "Manufacturer") "XINGLIGHT(成兴光)"))
      (libsource (lib "easyedapro") (part "LED_WS2812B"))
    )
    (comp (ref "D83")
      (value "XL-5050RGBC-WS2812B")
      (footprint "easyedapro:LED_SMD:LED_WS2812B_PLCC4_5.0x5.0mm_P3.2mm")
      (fields (field (name "Manufacturer") "XINGLIGHT(成兴光)"))
      (libsource (lib "easyedapro") (part "LED_WS2812B"))
    )
    (comp (ref "D84")
      (value "XL-5050RGBC-WS2812B")
      (footprint "easyedapro:LED_SMD:LED_WS2812B_PLCC4_5.0x5.0mm_P3.2mm")
      (fields (field (name "Manufacturer") "XINGLIGHT(成兴光)"))
      (libsource (lib "easyedapro") (part "LED_WS2812B"))
    )
    (comp (ref "D85")
      (value "XL-5050RGBC-WS2812B")
      (footprint "easyedapro:LED_SMD:LED_WS2812B_PLCC4_5.0x5.0mm_P3.2mm")
      (fields (field (name "Manufacturer") "XINGLIGHT(成兴光)"))
      (libsource (lib "easyedapro") (part "LED_WS2812B"))
    )
    (comp (ref "D86")
      (value "XL-5050RGBC-WS2812B")
      (footprint "easyedapro:LED_SMD:LED_WS2812B_PLCC4_5.0x5.0mm_P3.2mm")
      (fields (field (name "Manufacturer") "XINGLIGHT(成兴光)"))
      (libsource (lib "easyedapro") (part "LED_WS2812B"))
    )
    (comp (ref "D87")
      (value "XL-5050RGBC-WS2812B")
      (footprint "easyedapro:LED_SMD:LED_WS2812B_PLCC4_5.0x5.0mm_P3.2mm")
      (fields (field (name "Manufacturer") "XINGLIGHT(成兴光)"))
      (libsource (lib "easyedapro") (part "LED_WS2812B"))
    )
    (comp (ref "D88")
      (value "XL-5050RGBC-WS2812B")
      (footprint "easyedapro:LED_SMD:LED_WS2812B_PLCC4_5.0x5.0mm_P3.2mm")
      (fields (field (name "Manufacturer") "XINGLIGHT(成兴光)"))
      (libsource (lib "easyedapro") (part "LED_WS2812B"))
    )
    (comp (ref "D89")
      (value "XL-5050RGBC-WS2812B")
      (footprint "easyedapro:LED_SMD:LED_WS2812B_PLCC4_5.0x5.0mm_P3.2mm")
      (fields (field (name "Manufacturer") "XINGLIGHT(成兴光)"))
      (libsource (lib "easyedapro") (part "LED_WS2812B"))
    )
    (comp (ref "D90")
      (value "XL-5050RGBC-WS2812B")
      (footprint "easyedapro:LED_SMD:LED_WS2812B_PLCC4_5.0x5.0mm_P3.2mm")
      (fields (field (name "Manufacturer") "XINGLIGHT(成兴光)"))
      (libsource (lib "easyedapro") (part "LED_WS2812B"))
    )
    (comp (ref "D91")
      (value "XL-5050RGBC-WS2812B")
      (footprint "easyedapro:LED_SMD:LED_WS2812B_PLCC4_5.0x5.0mm_P3.2mm")
      (fields (field (name "Manufacturer") "XINGLIGHT(成兴光)"))
      (libsource (lib "easyedapro") (part "LED_WS2812B"))
    )
    (comp (ref "D92")
      (value "XL-5050RGBC-WS2812B")
      (footprint "easyedapro:LED_SMD:LED_WS2812B_PLCC4_5.0x5.0mm_P3.2mm")
      (fields (field (name "Manufacturer") "XINGLIGHT(成兴光)"))
      (libsource (lib "easyedapro") (part "LED_WS2812B"))
    )
    (comp (ref "D93")
      (value "XL-5050RGBC-WS2812B")
      (footprint "easyedapro:LED_SMD:LED_WS2812B_PLCC4_5.0x5.0mm_P3.2mm")
      (fields (field (name "Manufacturer") "XINGLIGHT(成兴光)"))
      (libsource (lib "easyedapro") (part "LED_WS2812B"))
    )
    (comp (ref "D94")
      (value "XL-5050RGBC-WS2812B")
      (footprint "easyedapro:LED_SMD:LED_WS2812B_PLCC4_5.0x5.0mm_P3.2mm")
      (fields (field (name "Manufacturer") "XINGLIGHT(成兴光)"))
      (libsource (lib "easyedapro") (part "LED_WS2812B"))
    )
    (comp (ref "D95")
      (value "XL-5050RGBC-WS2812B")
      (footprint "easyedapro:LED_SMD:LED_WS2812B_PLCC4_5.0x5.0mm_P3.2mm")
      (fields (field (name "Manufacturer") "XINGLIGHT(成兴光)"))
      (libsource (lib "easyedapro") (part "LED_WS2812B"))
    )
    (comp (ref "D96")
      (value "XL-5050RGBC-WS2812B")
      (footprint "easyedapro:LED_SMD:LED_WS2812B_PLCC4_5.0x5.0mm_P3.2mm")
      (fields (field (name "Manufacturer") "XINGLIGHT(成兴光)"))
      (libsource (lib "easyedapro") (part "LED_WS2812B"))
    )
    (comp (ref "D97")
      (value "XL-5050RGBC-WS2812B")
      (footprint "easyedapro:LED_SMD:LED_WS2812B_PLCC4_5.0x5.0mm_P3.2mm")
      (fields (field (name "Manufacturer") "XINGLIGHT(成兴光)"))
      (libsource (lib "easyedapro") (part "LED_WS2812B"))
    )
    (comp (ref "D98")
      (value "XL-5050RGBC-WS2812B")
      (footprint "easyedapro:LED_SMD:LED_WS2812B_PLCC4_5.0x5.0mm_P3.2mm")
      (fields (field (name "Manufacturer") "XINGLIGHT(成兴光)"))
      (libsource (lib "easyedapro") (part "LED_WS2812B"))
    )
    (comp (ref "D99")
      (value "XL-5050RGBC-WS2812B")
      (footprint "easyedapro:LED_SMD:LED_WS2812B_PLCC4_5.0x5.0mm_P3.2mm")
      (fields (field (name "Manufacturer") "XINGLIGHT(成兴光)"))
      (libsource (lib "easyedapro") (part "LED_WS2812B"))
    )
    (comp (ref "D100")
      (value "XL-5050RGBC-WS2812B")
      (footprint "easyedapro:LED_SMD:LED_WS2812B_PLCC4_5.0x5.0mm_P3.2mm")
      (fields (field (name "Manufacturer") "XINGLIGHT(成兴光)"))
      (libsource (lib "easyedapro") (part "LED_WS2812B"))
    )
    (comp (ref "D101")
      (value "XL-5050RGBC-WS2812B")
      (footprint "easyedapro:LED_SMD:LED_WS2812B_PLCC4_5.0x5.0mm_P3.2mm")
      (fields (field (name "Manufacturer") "XINGLIGHT(成兴光)"))
      (libsource (lib "easyedapro") (part "LED_WS2812B"))
    )
    (comp (ref "D102")
      (value "XL-5050RGBC-WS2812B")
      (footprint "easyedapro:LED_SMD:LED_WS2812B_PLCC4_5.0x5.0mm_P3.2mm")
      (fields (field (name "Manufacturer") "XINGLIGHT(成兴光)"))
      (libsource (lib "easyedapro") (part "LED_WS2812B"))
    )
    (comp (ref "F1")
      (value "nSMD050-33V")
      (footprint "easyedapro:F1206")
      (description "Voltage - Max:33V Current - Max:100A Hold Current:500mA Trip Current:1A")
      (fields (field (name "Manufacturer") "台湾陆海"))
      (libsource (lib "easyedapro") (part "nSMD050-33V"))
    )
    (comp (ref "J1")
      (value "DC005")
      (footprint "easyedapro:DC-IN-TH_DC005")
      (fields (field (name "Manufacturer") "SHOU HAN(首韩)"))
      (libsource (lib "easyedapro") (part "DC005_C431533"))
    )
    (comp (ref "R20")
      (value "33Ω")
      (footprint "easyedapro:Resistor_THT:R_Axial_DIN0204_L3.6mm_D1.6mm_P2.54mm_Vertical")
      (fields
        (field (name "Manufacturer Part") "RN1/8W10KFT/BA1")
        (field (name "Manufacturer") "Tyohm(幸亚电阻)")
      )
      (libsource (lib "easyedapro") (part "Device_R"))
    )
    (comp (ref "R72")
      (value "10kΩ")
      (footprint "easyedapro:Resistor_THT:R_Axial_DIN0204_L3.6mm_D1.6mm_P2.54mm_Vertical")
      (fields
        (field (name "Manufacturer Part") "RN1/8W10KFT/BA1")
        (field (name "Manufacturer") "Tyohm(幸亚电阻)")
      )
      (libsource (lib "easyedapro") (part "Device_R"))
    )
    (comp (ref "R73")
      (value "10kΩ")
      (footprint "easyedapro:Resistor_THT:R_Axial_DIN0204_L3.6mm_D1.6mm_P2.54mm_Vertical")
      (fields
        (field (name "Manufacturer Part") "RN1/8W10KFT/BA1")
        (field (name "Manufacturer") "Tyohm(幸亚电阻)")
      )
      (libsource (lib "easyedapro") (part "Device_R"))
    )
    (comp (ref "R74")
      (value "10kΩ")
      (footprint "easyedapro:Resistor_THT:R_Axial_DIN0204_L3.6mm_D1.6mm_P2.54mm_Vertical")
      (fields
        (field (name "Manufacturer Part") "RN1/8W10KFT/BA1")
        (field (name "Manufacturer") "Tyohm(幸亚电阻)")
      )
      (libsource (lib "easyedapro") (part "Device_R"))
    )
    (comp (ref "R75")
      (value "10kΩ")
      (footprint "easyedapro:Resistor_THT:R_Axial_DIN0204_L3.6mm_D1.6mm_P2.54mm_Vertical")
      (fields
        (field (name "Manufacturer Part") "RN1/8W10KFT/BA1")
        (field (name "Manufacturer") "Tyohm(幸亚电阻)")
      )
      (libsource (lib "easyedapro") (part "Device_R"))
    )
    (comp (ref "R76")
      (value "10kΩ")
      (footprint "easyedapro:Resistor_THT:R_Axial_DIN0204_L3.6mm_D1.6mm_P2.54mm_Vertical")
      (fields
        (field (name "Manufacturer Part") "RN1/8W10KFT/BA1")
        (field (name "Manufacturer") "Tyohm(幸亚电阻)")
      )
      (libsource (lib "easyedapro") (part "Device_R"))
    )
    (comp (ref "R77")
      (value "10kΩ")
      (footprint "easyedapro:Resistor_THT:R_Axial_DIN0204_L3.6mm_D1.6mm_P2.54mm_Vertical")
      (fields
        (field (name "Manufacturer Part") "RN1/8W10KFT/BA1")
        (field (name "Manufacturer") "Tyohm(幸亚电阻)")
      )
      (libsource (lib "easyedapro") (part "Device_R"))
    )
    (comp (ref "SW1")
      (value "HX B3F-4055-Y")
      (footprint "easyedapro:Button_Switch_SMD:SW_SPST_PTS645")
      (fields (field (name "Manufacturer") "hanxia(韩下)"))
      (libsource (lib "easyedapro") (part "Switch_SW_Push"))
    )
    (comp (ref "SW2")
      (value "HX B3F-4055-Y")
      (footprint "easyedapro:Button_Switch_SMD:SW_SPST_PTS645")
      (fields (field (name "Manufacturer") "hanxia(韩下)"))
      (libsource (lib "easyedapro") (part "Switch_SW_Push"))
    )
    (comp (ref "SW3")
      (value "HX B3F-4055-Y")
      (footprint "easyedapro:Button_Switch_SMD:SW_SPST_PTS645")
      (fields (field (name "Manufacturer") "hanxia(韩下)"))
      (libsource (lib "easyedapro") (part "Switch_SW_Push"))
    )
    (comp (ref "SW4")
      (value "HX B3F-4055-Y")
      (footprint "easyedapro:Button_Switch_SMD:SW_SPST_PTS645")
      (fields (field (name "Manufacturer") "hanxia(韩下)"))
      (libsource (lib "easyedapro") (part "Switch_SW_Push"))
    )
    (comp (ref "SW5")
      (value "HX B3F-4055-Y")
      (footprint "easyedapro:Button_Switch_SMD:SW_SPST_PTS645")
      (fields (field (name "Manufacturer") "hanxia(韩下)"))
      (libsource (lib "easyedapro") (part "Switch_SW_Push"))
    )
    (comp (ref "SW6")
      (value "HX B3F-4055-Y")
      (footprint "easyedapro:Button_Switch_SMD:SW_SPST_PTS645")
      (fields (field (name "Manufacturer") "hanxia(韩下)"))
      (libsource (lib "easyedapro") (part "Switch_SW_Push"))
    )
    (comp (ref "SW7")
      (value "HX B3F-4055-Y")
      (footprint "easyedapro:Button_Switch_SMD:SW_SPST_PTS645")
      (fields (field (name "Manufacturer") "hanxia(韩下)"))
      (libsource (lib "easyedapro") (part "Switch_SW_Push"))
    )
    (comp (ref "SW8")
      (value "HX B3F-4055-Y")
      (footprint "easyedapro:Button_Switch_SMD:SW_SPST_PTS645")
      (fields (field (name "Manufacturer") "hanxia(韩下)"))
      (libsource (lib "easyedapro") (part "Switch_SW_Push"))
    )
    (comp (ref "SW9")
      (value "HX B3F-4055-Y")
      (footprint "easyedapro:Button_Switch_SMD:SW_SPST_PTS645")
      (fields (field (name "Manufacturer") "hanxia(韩下)"))
      (libsource (lib "easyedapro") (part "Switch_SW_Push"))
    )
    (comp (ref "SW10")
      (value "HX B3F-4055-Y")
      (footprint "easyedapro:Button_Switch_SMD:SW_SPST_PTS645")
      (fields (field (name "Manufacturer") "hanxia(韩下)"))
      (libsource (lib "easyedapro") (part "Switch_SW_Push"))
    )
    (comp (ref "SW11")
      (value "HX B3F-4055-Y")
      (footprint "easyedapro:Button_Switch_SMD:SW_SPST_PTS645")
      (fields (field (name "Manufacturer") "hanxia(韩下)"))
      (libsource (lib "easyedapro") (part "Switch_SW_Push"))
    )
    (comp (ref "SW12")
      (value "HX B3F-4055-Y")
      (footprint "easyedapro:Button_Switch_SMD:SW_SPST_PTS645")
      (fields (field (name "Manufacturer") "hanxia(韩下)"))
      (libsource (lib "easyedapro") (part "Switch_SW_Push"))
    )
    (comp (ref "SW13")
      (value "HX B3F-4055-Y")
      (footprint "easyedapro:Button_Switch_SMD:SW_SPST_PTS645")
      (fields (field (name "Manufacturer") "hanxia(韩下)"))
      (libsource (lib "easyedapro") (part "Switch_SW_Push"))
    )
    (comp (ref "SW14")
      (value "HX B3F-4055-Y")
      (footprint "easyedapro:Button_Switch_SMD:SW_SPST_PTS645")
      (fields (field (name "Manufacturer") "hanxia(韩下)"))
      (libsource (lib "easyedapro") (part "Switch_SW_Push"))
    )
    (comp (ref "SW15")
      (value "HX B3F-4055-Y")
      (footprint "easyedapro:Button_Switch_SMD:SW_SPST_PTS645")
      (fields (field (name "Manufacturer") "hanxia(韩下)"))
      (libsource (lib "easyedapro") (part "Switch_SW_Push"))
    )
    (comp (ref "SW16")
      (value "HX B3F-4055-Y")
      (footprint "easyedapro:Button_Switch_SMD:SW_SPST_PTS645")
      (fields (field (name "Manufacturer") "hanxia(韩下)"))
      (libsource (lib "easyedapro") (part "Switch_SW_Push"))
    )
    (comp (ref "SW17")
      (value "HX B3F-4055-Y")
      (footprint "easyedapro:Button_Switch_SMD:SW_SPST_PTS645")
      (fields (field (name "Manufacturer") "hanxia(韩下)"))
      (libsource (lib "easyedapro") (part "Switch_SW_Push"))
    )
    (comp (ref "SW18")
      (value "HX B3F-4055-Y")
      (footprint "easyedapro:Button_Switch_SMD:SW_SPST_PTS645")
      (fields (field (name "Manufacturer") "hanxia(韩下)"))
      (libsource (lib "easyedapro") (part "Switch_SW_Push"))
    )
    (comp (ref "SW19")
      (value "HX B3F-4055-Y")
      (footprint "easyedapro:Button_Switch_SMD:SW_SPST_PTS645")
      (fields (field (name "Manufacturer") "hanxia(韩下)"))
      (libsource (lib "easyedapro") (part "Switch_SW_Push"))
    )
    (comp (ref "SW20")
      (value "HX B3F-4055-Y")
      (footprint "easyedapro:Button_Switch_SMD:SW_SPST_PTS645")
      (fields (field (name "Manufacturer") "hanxia(韩下)"))
      (libsource (lib "easyedapro") (part "Switch_SW_Push"))
    )
    (comp (ref "SW21")
      (value "HX B3F-4055-Y")
      (footprint "easyedapro:Button_Switch_SMD:SW_SPST_PTS645")
      (fields (field (name "Manufacturer") "hanxia(韩下)"))
      (libsource (lib "easyedapro") (part "Switch_SW_Push"))
    )
    (comp (ref "SW22")
      (value "HX B3F-4055-Y")
      (footprint "easyedapro:Button_Switch_SMD:SW_SPST_PTS645")
      (fields (field (name "Manufacturer") "hanxia(韩下)"))
      (libsource (lib "easyedapro") (part "Switch_SW_Push"))
    )
    (comp (ref "SW23")
      (value "HX B3F-4055-Y")
      (footprint "easyedapro:Button_Switch_SMD:SW_SPST_PTS645")
      (fields (field (name "Manufacturer") "hanxia(韩下)"))
      (libsource (lib "easyedapro") (part "Switch_SW_Push"))
    )
    (comp (ref "SW24")
      (value "HX B3F-4055-Y")
      (footprint "easyedapro:Button_Switch_SMD:SW_SPST_PTS645")
      (fields (field (name "Manufacturer") "hanxia(韩下)"))
      (libsource (lib "easyedapro") (part "Switch_SW_Push"))
    )
    (comp (ref "SW25")
      (value "HX B3F-4055-Y")
      (footprint "easyedapro:Button_Switch_SMD:SW_SPST_PTS645")
      (fields (field (name "Manufacturer") "hanxia(韩下)"))
      (libsource (lib "easyedapro") (part "Switch_SW_Push"))
    )
    (comp (ref "SW26")
      (value "HX B3F-4055-Y")
      (footprint "easyedapro:Button_Switch_SMD:SW_SPST_PTS645")
      (fields (field (name "Manufacturer") "hanxia(韩下)"))
      (libsource (lib "easyedapro") (part "Switch_SW_Push"))
    )
    (comp (ref "SW27")
      (value "HX B3F-4055-Y")
      (footprint "easyedapro:Button_Switch_SMD:SW_SPST_PTS645")
      (fields (field (name "Manufacturer") "hanxia(韩下)"))
      (libsource (lib "easyedapro") (part "Switch_SW_Push"))
    )
    (comp (ref "SW28")
      (value "HX B3F-4055-Y")
      (footprint "easyedapro:Button_Switch_SMD:SW_SPST_PTS645")
      (fields (field (name "Manufacturer") "hanxia(韩下)"))
      (libsource (lib "easyedapro") (part "Switch_SW_Push"))
    )
    (comp (ref "SW29")
      (value "HX B3F-4055-Y")
      (footprint "easyedapro:Button_Switch_SMD:SW_SPST_PTS645")
      (fields (field (name "Manufacturer") "hanxia(韩下)"))
      (libsource (lib "easyedapro") (part "Switch_SW_Push"))
    )
    (comp (ref "SW30")
      (value "HX B3F-4055-Y")
      (footprint "easyedapro:Button_Switch_SMD:SW_SPST_PTS645")
      (fields (field (name "Manufacturer") "hanxia(韩下)"))
      (libsource (lib "easyedapro") (part "Switch_SW_Push"))
    )
    (comp (ref "SW31")
      (value "HX B3F-4055-Y")
      (footprint "easyedapro:Button_Switch_SMD:SW_SPST_PTS645")
      (fields (field (name "Manufacturer") "hanxia(韩下)"))
      (libsource (lib "easyedapro") (part "Switch_SW_Push"))
    )
    (comp (ref "SW32")
      (value "HX B3F-4055-Y")
      (footprint "easyedapro:Button_Switch_SMD:SW_SPST_PTS645")
      (fields (field (name "Manufacturer") "hanxia(韩下)"))
      (libsource (lib "easyedapro") (part "Switch_SW_Push"))
    )
    (comp (ref "SW33")
      (value "HX B3F-4055-Y")
      (footprint "easyedapro:Button_Switch_SMD:SW_SPST_PTS645")
      (fields (field (name "Manufacturer") "hanxia(韩下)"))
      (libsource (lib "easyedapro") (part "Switch_SW_Push"))
    )
    (comp (ref "SW34")
      (value "HX B3F-4055-Y")
      (footprint "easyedapro:Button_Switch_SMD:SW_SPST_PTS645")
      (fields (field (name "Manufacturer") "hanxia(韩下)"))
      (libsource (lib "easyedapro") (part "Switch_SW_Push"))
    )
    (comp (ref "SW35")
      (value "HX B3F-4055-Y")
      (footprint "easyedapro:Button_Switch_SMD:SW_SPST_PTS645")
      (fields (field (name "Manufacturer") "hanxia(韩下)"))
      (libsource (lib "easyedapro") (part "Switch_SW_Push"))
    )
    (comp (ref "SW36")
      (value "HX B3F-4055-Y")
      (footprint "easyedapro:Button_Switch_SMD:SW_SPST_PTS645")
      (fields (field (name "Manufacturer") "hanxia(韩下)"))
      (libsource (lib "easyedapro") (part "Switch_SW_Push"))
    )
    (comp (ref "SW37")
      (value "HX B3F-4055-Y")
      (footprint "easyedapro:Button_Switch_SMD:SW_SPST_PTS645")
      (fields (field (name "Manufacturer") "hanxia(韩下)"))
      (libsource (lib "easyedapro") (part "Switch_SW_Push"))
    )
    (comp (ref "SW38")
      (value "HX B3F-4055-Y")
      (footprint "easyedapro:Button_Switch_SMD:SW_SPST_PTS645")
      (fields (field (name "Manufacturer") "hanxia(韩下)"))
      (libsource (lib "easyedapro") (part "Switch_SW_Push"))
    )
    (comp (ref "SW39")
      (value "HX B3F-4055-Y")
      (footprint "easyedapro:Button_Switch_SMD:SW_SPST_PTS645")
      (fields (field (name "Manufacturer") "hanxia(韩下)"))
      (libsource (lib "easyedapro") (part "Switch_SW_Push"))
    )
    (comp (ref "SW40")
      (value "HX B3F-4055-Y")
      (footprint "easyedapro:Button_Switch_SMD:SW_SPST_PTS645")
      (fields (field (name "Manufacturer") "hanxia(韩下)"))
      (libsource (lib "easyedapro") (part "Switch_SW_Push"))
    )
    (comp (ref "SW41")
      (value "HX B3F-4055-Y")
      (footprint "easyedapro:Button_Switch_SMD:SW_SPST_PTS645")
      (fields (field (name "Manufacturer") "hanxia(韩下)"))
      (libsource (lib "easyedapro") (part "Switch_SW_Push"))
    )
    (comp (ref "SW42")
      (value "HX B3F-4055-Y")
      (footprint "easyedapro:Button_Switch_SMD:SW_SPST_PTS645")
      (fields (field (name "Manufacturer") "hanxia(韩下)"))
      (libsource (lib "easyedapro") (part "Switch_SW_Push"))
    )
    (comp (ref "SW49")
      (value "TK-6580A-1")
      (footprint "easyedapro:SW-TH_TK-6580A-1")
      (fields (field (name "Manufacturer") "Yuandi(元迪)"))
      (libsource (lib "easyedapro") (part "TK-6580A-1"))
    )
    (comp (ref "U6")
      (value "1812L200/33GR")
      (footprint "easyedapro:F1812")
      (fields (field (name "Manufacturer") "LUTE(陆特)"))
      (libsource (lib "easyedapro") (part "1812L200/33GR"))
    )
    (comp (ref "U8")
      (value "SN74AHCT125N")
      (footprint "easyedapro:PDIP-14_L19.3-W6.4-P2.54-LS7.6-BL")
      (fields (field (name "Manufacturer") "TI(德州仪器)"))
      (libsource (lib "easyedapro") (part "SN74AHCT125N"))
    )
    (comp (ref "C62")
      (value "100nF")
      (footprint "easyedapro:Capacitor_THT:C_Disc_D3.4mm_W2.1mm_P2.50mm")
      (description "Capacitance:100nF Tolerance:±10% Tolerance:±10% Voltage Rating:50V Temperature Coefficient:X7R")
      (fields
        (field (name "Manufacturer Part") "TCC0603X7R104K500CT")
        (field (name "Manufacturer") "CCTC(三环)")
      )
      (libsource (lib "easyedapro") (part "Device_C"))
    )
    (comp (ref "C63")
      (value "100nF")
      (footprint "easyedapro:Capacitor_THT:C_Disc_D3.4mm_W2.1mm_P2.50mm")
      (description "Capacitance:100nF Tolerance:±10% Tolerance:±10% Voltage Rating:50V Temperature Coefficient:X7R")
      (fields
        (field (name "Manufacturer Part") "TCC0603X7R104K500CT")
        (field (name "Manufacturer") "CCTC(三环)")
      )
      (libsource (lib "easyedapro") (part "Device_C"))
    )
    (comp (ref "C64")
      (value "100nF")
      (footprint "easyedapro:Capacitor_THT:C_Disc_D3.4mm_W2.1mm_P2.50mm")
      (description "Capacitance:100nF Tolerance:±10% Tolerance:±10% Voltage Rating:50V Temperature Coefficient:X7R")
      (fields
        (field (name "Manufacturer Part") "TCC0603X7R104K500CT")
        (field (name "Manufacturer") "CCTC(三环)")
      )
      (libsource (lib "easyedapro") (part "Device_C"))
    )
    (comp (ref "C71")
      (value "100nF")
      (footprint "easyedapro:Capacitor_THT:C_Disc_D3.4mm_W2.1mm_P2.50mm")
      (description "Capacitance:100nF Tolerance:±10% Tolerance:±10% Voltage Rating:50V Temperature Coefficient:X7R")
      (fields
        (field (name "Manufacturer Part") "TCC0603X7R104K500CT")
        (field (name "Manufacturer") "CCTC(三环)")
      )
      (libsource (lib "easyedapro") (part "Device_C"))
    )
    (comp (ref "C72")
      (value "4.7uF")
      (footprint "easyedapro:CAP-SMD_BD6.3-L6.6-W6.6-FD")
      (fields (field (name "Manufacturer Part") "189RV0019") (field (name "Manufacturer") "KNSCHA(科尼盛)"))
      (libsource (lib "easyedapro") (part "189RV0019"))
    )
    (comp (ref "C73")
      (value "1uF")
      (footprint "easyedapro:Capacitor_THT:C_Disc_D3.4mm_W2.1mm_P2.50mm")
      (description "Capacitance:100nF Tolerance:±10% Tolerance:±10% Voltage Rating:63V Temperature Coefficient:-")
      (fields
        (field (name "Manufacturer Part") "CT4G-0805-2X1-63V-0.1μF-K")
        (field (name "Manufacturer") "TORCH(火炬)")
      )
      (libsource (lib "easyedapro") (part "Device_C"))
    )
    (comp (ref "C74")
      (value "10uF")
      (footprint "easyedapro:CAP-SMD_BD6.3-L6.6-W6.6-FD")
      (fields (field (name "Manufacturer Part") "189RV0019") (field (name "Manufacturer") "KNSCHA(科尼盛)"))
      (libsource (lib "easyedapro") (part "189RV0019"))
    )
    (comp (ref "C75")
      (value "100nF")
      (footprint "easyedapro:Capacitor_THT:C_Disc_D3.4mm_W2.1mm_P2.50mm")
      (description "Capacitance:100nF Tolerance:±10% Tolerance:±10% Voltage Rating:50V Temperature Coefficient:X7R")
      (fields
        (field (name "Manufacturer Part") "TCC0603X7R104K500CT")
        (field (name "Manufacturer") "CCTC(三环)")
      )
      (libsource (lib "easyedapro") (part "Device_C"))
    )
    (comp (ref "C76")
      (value "100nF")
      (footprint "easyedapro:Capacitor_THT:C_Disc_D3.4mm_W2.1mm_P2.50mm")
      (description "Capacitance:100nF Tolerance:±10% Tolerance:±10% Voltage Rating:50V Temperature Coefficient:X7R")
      (fields
        (field (name "Manufacturer Part") "TCC0603X7R104K500CT")
        (field (name "Manufacturer") "CCTC(三环)")
      )
      (libsource (lib "easyedapro") (part "Device_C"))
    )
    (comp (ref "C77")
      (value "4.7nF")
      (footprint "easyedapro:Capacitor_THT:C_Disc_D3.4mm_W2.1mm_P2.50mm")
      (description "Capacitance:100nF Tolerance:±10% Tolerance:±10% Voltage Rating:63V Temperature Coefficient:-")
      (fields
        (field (name "Manufacturer Part") "CT4G-0805-2X1-63V-0.1μF-K")
        (field (name "Manufacturer") "TORCH(火炬)")
      )
      (libsource (lib "easyedapro") (part "Device_C"))
    )
    (comp (ref "C113")
      (value "100nF")
      (footprint "easyedapro:Capacitor_THT:C_Disc_D3.4mm_W2.1mm_P2.50mm")
      (description "Capacitance:100nF Tolerance:±10% Tolerance:±10% Voltage Rating:50V Temperature Coefficient:X7R")
      (fields
        (field (name "Manufacturer Part") "TCC0603X7R104K500CT")
        (field (name "Manufacturer") "CCTC(三环)")
      )
      (libsource (lib "easyedapro") (part "Device_C"))
    )
    (comp (ref "C114")
      (value "100nF")
      (footprint "easyedapro:Capacitor_THT:C_Disc_D3.4mm_W2.1mm_P2.50mm")
      (description "Capacitance:100nF Tolerance:±10% Tolerance:±10% Voltage Rating:50V Temperature Coefficient:X7R")
      (fields
        (field (name "Manufacturer Part") "TCC0603X7R104K500CT")
        (field (name "Manufacturer") "CCTC(三环)")
      )
      (libsource (lib "easyedapro") (part "Device_C"))
    )
    (comp (ref "C115")
      (value "100nF")
      (footprint "easyedapro:Capacitor_THT:C_Disc_D3.4mm_W2.1mm_P2.50mm")
      (description "Capacitance:100nF Tolerance:±10% Tolerance:±10% Voltage Rating:50V Temperature Coefficient:X7R")
      (fields
        (field (name "Manufacturer Part") "TCC0603X7R104K500CT")
        (field (name "Manufacturer") "CCTC(三环)")
      )
      (libsource (lib "easyedapro") (part "Device_C"))
    )
    (comp (ref "C116")
      (value "100nF")
      (footprint "easyedapro:Capacitor_THT:C_Disc_D3.4mm_W2.1mm_P2.50mm")
      (description "Capacitance:100nF Tolerance:±10% Tolerance:±10% Voltage Rating:50V Temperature Coefficient:X7R")
      (fields
        (field (name "Manufacturer Part") "TCC0603X7R104K500CT")
        (field (name "Manufacturer") "CCTC(三环)")
      )
      (libsource (lib "easyedapro") (part "Device_C"))
    )
    (comp (ref "C117")
      (value "100nF")
      (footprint "easyedapro:Capacitor_THT:C_Disc_D3.4mm_W2.1mm_P2.50mm")
      (description "Capacitance:100nF Tolerance:±10% Tolerance:±10% Voltage Rating:50V Temperature Coefficient:X7R")
      (fields
        (field (name "Manufacturer Part") "TCC0603X7R104K500CT")
        (field (name "Manufacturer") "CCTC(三环)")
      )
      (libsource (lib "easyedapro") (part "Device_C"))
    )
    (comp (ref "C118")
      (value "100nF")
      (footprint "easyedapro:Capacitor_THT:C_Disc_D3.4mm_W2.1mm_P2.50mm")
      (description "Capacitance:100nF Tolerance:±10% Tolerance:±10% Voltage Rating:50V Temperature Coefficient:X7R")
      (fields
        (field (name "Manufacturer Part") "TCC0603X7R104K500CT")
        (field (name "Manufacturer") "CCTC(三环)")
      )
      (libsource (lib "easyedapro") (part "Device_C"))
    )
    (comp (ref "C119")
      (value "100nF")
      (footprint "easyedapro:Capacitor_THT:C_Disc_D3.4mm_W2.1mm_P2.50mm")
      (description "Capacitance:100nF Tolerance:±10% Tolerance:±10% Voltage Rating:50V Temperature Coefficient:X7R")
      (fields
        (field (name "Manufacturer Part") "TCC0603X7R104K500CT")
        (field (name "Manufacturer") "CCTC(三环)")
      )
      (libsource (lib "easyedapro") (part "Device_C"))
    )
    (comp (ref "C120")
      (value "100nF")
      (footprint "easyedapro:Capacitor_THT:C_Disc_D3.4mm_W2.1mm_P2.50mm")
      (description "Capacitance:100nF Tolerance:±10% Tolerance:±10% Voltage Rating:50V Temperature Coefficient:X7R")
      (fields
        (field (name "Manufacturer Part") "TCC0603X7R104K500CT")
        (field (name "Manufacturer") "CCTC(三环)")
      )
      (libsource (lib "easyedapro") (part "Device_C"))
    )
    (comp (ref "COL_MUX2")
      (value "CD74HC4067M96")
      (footprint "easyedapro:Package_SO:SOIC-24W_7.5x15.4mm_P1.27mm")
      (fields (field (name "Manufacturer") "TI(德州仪器)"))
      (libsource (lib "easyedapro") (part "74xx_CD74HC4067M"))
    )
    (comp (ref "D103")
      (value "1N4148PF")
      (footprint "easyedapro:Diode_THT:D_DO-35_SOD27_P7.62mm_Horizontal")
      (fields (field (name "Manufacturer") "ST(先科)"))
      (libsource (lib "easyedapro") (part "Diode_1N4148"))
    )
    (comp (ref "D104")
      (value "XL-5050RGBC-WS2812B")
      (footprint "easyedapro:LED_SMD:LED_WS2812B_PLCC4_5.0x5.0mm_P3.2mm")
      (fields (field (name "Manufacturer") "XINGLIGHT(成兴光)"))
      (libsource (lib "easyedapro") (part "LED_WS2812B"))
    )
    (comp (ref "D105")
      (value "XL-5050RGBC-WS2812B")
      (footprint "easyedapro:LED_SMD:LED_WS2812B_PLCC4_5.0x5.0mm_P3.2mm")
      (fields (field (name "Manufacturer") "XINGLIGHT(成兴光)"))
      (libsource (lib "easyedapro") (part "LED_WS2812B"))
    )
    (comp (ref "D106")
      (value "XL-5050RGBC-WS2812B")
      (footprint "easyedapro:LED_SMD:LED_WS2812B_PLCC4_5.0x5.0mm_P3.2mm")
      (fields (field (name "Manufacturer") "XINGLIGHT(成兴光)"))
      (libsource (lib "easyedapro") (part "LED_WS2812B"))
    )
    (comp (ref "D107")
      (value "XL-5050RGBC-WS2812B")
      (footprint "easyedapro:LED_SMD:LED_WS2812B_PLCC4_5.0x5.0mm_P3.2mm")
      (fields (field (name "Manufacturer") "XINGLIGHT(成兴光)"))
      (libsource (lib "easyedapro") (part "LED_WS2812B"))
    )
    (comp (ref "D108")
      (value "XL-5050RGBC-WS2812B")
      (footprint "easyedapro:LED_SMD:LED_WS2812B_PLCC4_5.0x5.0mm_P3.2mm")
      (fields (field (name "Manufacturer") "XINGLIGHT(成兴光)"))
      (libsource (lib "easyedapro") (part "LED_WS2812B"))
    )
    (comp (ref "D109")
      (value "XL-5050RGBC-WS2812B")
      (footprint "easyedapro:LED_SMD:LED_WS2812B_PLCC4_5.0x5.0mm_P3.2mm")
      (fields (field (name "Manufacturer") "XINGLIGHT(成兴光)"))
      (libsource (lib "easyedapro") (part "LED_WS2812B"))
    )
    (comp (ref "D110")
      (value "XL-5050RGBC-WS2812B")
      (footprint "easyedapro:LED_SMD:LED_WS2812B_PLCC4_5.0x5.0mm_P3.2mm")
      (fields (field (name "Manufacturer") "XINGLIGHT(成兴光)"))
      (libsource (lib "easyedapro") (part "LED_WS2812B"))
    )
    (comp (ref "D111")
      (value "XL-5050RGBC-WS2812B")
      (footprint "easyedapro:LED_SMD:LED_WS2812B_PLCC4_5.0x5.0mm_P3.2mm")
      (fields (field (name "Manufacturer") "XINGLIGHT(成兴光)"))
      (libsource (lib "easyedapro") (part "LED_WS2812B"))
    )
    (comp (ref "D112")
      (value "XL-5050RGBC-WS2812B")
      (footprint "easyedapro:LED_SMD:LED_WS2812B_PLCC4_5.0x5.0mm_P3.2mm")
      (fields (field (name "Manufacturer") "XINGLIGHT(成兴光)"))
      (libsource (lib "easyedapro") (part "LED_WS2812B"))
    )
    (comp (ref "D113")
      (value "XL-5050RGBC-WS2812B")
      (footprint "easyedapro:LED_SMD:LED_WS2812B_PLCC4_5.0x5.0mm_P3.2mm")
      (fields (field (name "Manufacturer") "XINGLIGHT(成兴光)"))
      (libsource (lib "easyedapro") (part "LED_WS2812B"))
    )
    (comp (ref "J12")
      (value "DIN-504B-M10")
      (footprint "easyedapro:CONN-TH_DIN-504B-M10")
      (fields (field (name "Manufacturer") "HOOYA(皓宇电子)"))
      (libsource (lib "easyedapro") (part "DIN-504B-M10"))
    )
    (comp (ref "J13")
      (value "DIN-504B-M10")
      (footprint "easyedapro:CONN-TH_DIN-504B-M10")
      (fields (field (name "Manufacturer") "HOOYA(皓宇电子)"))
      (libsource (lib "easyedapro") (part "DIN-504B-M10"))
    )
    (comp (ref "J14")
      (value "HC-PJ-320A")
      (footprint "easyedapro:AUDIO-SMD_HC-PJ-320A")
      (fields (field (name "Manufacturer") "HC(虹成电子)"))
      (libsource (lib "easyedapro") (part "HC-PJ-320A"))
    )
    (comp (ref "J15")
      (value "HC-PJ-320A")
      (footprint "easyedapro:AUDIO-SMD_HC-PJ-320A")
      (fields (field (name "Manufacturer") "HC(虹成电子)"))
      (libsource (lib "easyedapro") (part "HC-PJ-320A"))
    )
    (comp (ref "LEDPWR2")
      (value "~")
      (footprint "easyedapro:LED_0603")
      (libsource (lib "easyedapro") (part "LED_R"))
    )
    (comp (ref "R85")
      (value "220Ω")
      (footprint "easyedapro:Resistor_THT:R_Axial_DIN0204_L3.6mm_D1.6mm_P2.54mm_Vertical")
      (fields
        (field (name "Manufacturer Part") "RN 1/8W 220R F T/B A1")
        (field (name "Manufacturer") "Tyohm(幸亚电阻)")
      )
      (libsource (lib "easyedapro") (part "Device_R"))
    )
    (comp (ref "R86")
      (value "220Ω")
      (footprint "easyedapro:Resistor_THT:R_Axial_DIN0204_L3.6mm_D1.6mm_P2.54mm_Vertical")
      (fields
        (field (name "Manufacturer Part") "RN 1/8W 220R F T/B A1")
        (field (name "Manufacturer") "Tyohm(幸亚电阻)")
      )
      (libsource (lib "easyedapro") (part "Device_R"))
    )
    (comp (ref "R87")
      (value "220Ω")
      (footprint "easyedapro:Resistor_THT:R_Axial_DIN0204_L3.6mm_D1.6mm_P2.54mm_Vertical")
      (fields
        (field (name "Manufacturer Part") "RN 1/8W 220R F T/B A1")
        (field (name "Manufacturer") "Tyohm(幸亚电阻)")
      )
      (libsource (lib "easyedapro") (part "Device_R"))
    )
    (comp (ref "R88")
      (value "4.7kΩ")
      (footprint "easyedapro:Resistor_THT:R_Axial_DIN0204_L3.6mm_D1.6mm_P2.54mm_Vertical")
      (fields
        (field (name "Manufacturer Part") "RN 1/8W 4K7 F T/B A1")
        (field (name "Manufacturer") "Tyohm(幸亚电阻)")
      )
      (libsource (lib "easyedapro") (part "Device_R"))
    )
    (comp (ref "R89")
      (value "100kΩ")
      (footprint "easyedapro:Resistor_THT:R_Axial_DIN0204_L3.6mm_D1.6mm_P2.54mm_Vertical")
      (fields
        (field (name "Manufacturer Part") "RN1/8W10KFT/BA1")
        (field (name "Manufacturer") "Tyohm(幸亚电阻)")
      )
      (libsource (lib "easyedapro") (part "Device_R"))
    )
    (comp (ref "R90")
      (value "100kΩ")
      (footprint "easyedapro:Resistor_THT:R_Axial_DIN0204_L3.6mm_D1.6mm_P2.54mm_Vertical")
      (fields
        (field (name "Manufacturer Part") "RN1/8W10KFT/BA1")
        (field (name "Manufacturer") "Tyohm(幸亚电阻)")
      )
      (libsource (lib "easyedapro") (part "Device_R"))
    )
    (comp (ref "R91")
      (value "4.7kΩ")
      (footprint "easyedapro:Resistor_THT:R_Axial_DIN0204_L3.6mm_D1.6mm_P2.54mm_Vertical")
      (fields
        (field (name "Manufacturer Part") "RN 1/8W 4K7 F T/B A1")
        (field (name "Manufacturer") "Tyohm(幸亚电阻)")
      )
      (libsource (lib "easyedapro") (part "Device_R"))
    )
    (comp (ref "R92")
      (value "4.7kΩ")
      (footprint "easyedapro:Resistor_THT:R_Axial_DIN0204_L3.6mm_D1.6mm_P2.54mm_Vertical")
      (fields
        (field (name "Manufacturer Part") "RN 1/8W 4K7 F T/B A1")
        (field (name "Manufacturer") "Tyohm(幸亚电阻)")
      )
      (libsource (lib "easyedapro") (part "Device_R"))
    )
    (comp (ref "R93")
      (value "220Ω")
      (footprint "easyedapro:Resistor_THT:R_Axial_DIN0204_L3.6mm_D1.6mm_P2.54mm_Vertical")
      (fields
        (field (name "Manufacturer Part") "RN 1/8W 220R F T/B A1")
        (field (name "Manufacturer") "Tyohm(幸亚电阻)")
      )
      (libsource (lib "easyedapro") (part "Device_R"))
    )
    (comp (ref "R94")
      (value "220Ω")
      (footprint "easyedapro:Resistor_THT:R_Axial_DIN0204_L3.6mm_D1.6mm_P2.54mm_Vertical")
      (fields
        (field (name "Manufacturer Part") "RN 1/8W 220R F T/B A1")
        (field (name "Manufacturer") "Tyohm(幸亚电阻)")
      )
      (libsource (lib "easyedapro") (part "Device_R"))
    )
    (comp (ref "R95")
      (value "220Ω")
      (footprint "easyedapro:Resistor_THT:R_Axial_DIN0204_L3.6mm_D1.6mm_P2.54mm_Vertical")
      (fields
        (field (name "Manufacturer Part") "RN 1/8W 220R F T/B A1")
        (field (name "Manufacturer") "Tyohm(幸亚电阻)")
      )
      (libsource (lib "easyedapro") (part "Device_R"))
    )
    (comp (ref "R96")
      (value "220Ω")
      (footprint "easyedapro:Resistor_THT:R_Axial_DIN0204_L3.6mm_D1.6mm_P2.54mm_Vertical")
      (fields
        (field (name "Manufacturer Part") "RN 1/8W 4K7 F T/B A1")
        (field (name "Manufacturer") "Tyohm(幸亚电阻)")
      )
      (libsource (lib "easyedapro") (part "Device_R"))
    )
    (comp (ref "R97")
      (value "220Ω")
      (footprint "easyedapro:Resistor_THT:R_Axial_DIN0204_L3.6mm_D1.6mm_P2.54mm_Vertical")
      (fields
        (field (name "Manufacturer Part") "RN 1/8W 4K7 F T/B A1")
        (field (name "Manufacturer") "Tyohm(幸亚电阻)")
      )
      (libsource (lib "easyedapro") (part "Device_R"))
    )
    (comp (ref "R98")
      (value "220Ω")
      (footprint "easyedapro:Resistor_THT:R_Axial_DIN0204_L3.6mm_D1.6mm_P2.54mm_Vertical")
      (fields
        (field (name "Manufacturer Part") "RN 1/8W 4K7 F T/B A1")
        (field (name "Manufacturer") "Tyohm(幸亚电阻)")
      )
      (libsource (lib "easyedapro") (part "Device_R"))
    )
    (comp (ref "R99")
      (value "220Ω")
      (footprint "easyedapro:Resistor_THT:R_Axial_DIN0204_L3.6mm_D1.6mm_P2.54mm_Vertical")
      (fields
        (field (name "Manufacturer Part") "RN 1/8W 4K7 F T/B A1")
        (field (name "Manufacturer") "Tyohm(幸亚电阻)")
      )
      (libsource (lib "easyedapro") (part "Device_R"))
    )
    (comp (ref "R100")
      (value "220Ω")
      (footprint "easyedapro:Resistor_THT:R_Axial_DIN0204_L3.6mm_D1.6mm_P2.54mm_Vertical")
      (fields
        (field (name "Manufacturer Part") "RN 1/8W 4K7 F T/B A1")
        (field (name "Manufacturer") "Tyohm(幸亚电阻)")
      )
      (libsource (lib "easyedapro") (part "Device_R"))
    )
    (comp (ref "R101")
      (value "220Ω")
      (footprint "easyedapro:Resistor_THT:R_Axial_DIN0204_L3.6mm_D1.6mm_P2.54mm_Vertical")
      (fields
        (field (name "Manufacturer Part") "RN 1/8W 4K7 F T/B A1")
        (field (name "Manufacturer") "Tyohm(幸亚电阻)")
      )
      (libsource (lib "easyedapro") (part "Device_R"))
    )
    (comp (ref "ROW_MUX2")
      (value "CD74HC4067M96")
      (footprint "easyedapro:Package_SO:SOIC-24W_7.5x15.4mm_P1.27mm")
      (fields (field (name "Manufacturer") "TI(德州仪器)"))
      (libsource (lib "easyedapro") (part "74xx_CD74HC4067M"))
    )
    (comp (ref "RV4")
      (value "10kΩ")
      (footprint "easyedapro:RES-ADJ-TH_RK09K1130A5R")
      (description "Resistance: Tolerance:±20% Tolerance:±20%")
      (fields
        (field (name "Manufacturer Part") "RK09K1130A5R")
        (field (name "Manufacturer") "ALPSALPINE(阿尔卑斯阿尔派)")
      )
      (libsource (lib "easyedapro") (part "RK09K1130A5R"))
    )
    (comp (ref "RV5")
      (value "10kΩ")
      (footprint "easyedapro:RES-ADJ-TH_RK09K1130A5R")
      (description "Resistance: Tolerance:±20% Tolerance:±20%")
      (fields
        (field (name "Manufacturer Part") "RK09K1130A5R")
        (field (name "Manufacturer") "ALPSALPINE(阿尔卑斯阿尔派)")
      )
      (libsource (lib "easyedapro") (part "RK09K1130A5R"))
    )
    (comp (ref "RV6")
      (value "10kΩ")
      (footprint "easyedapro:RES-ADJ-TH_RK09K1130A5R")
      (description "Resistance: Tolerance:±20% Tolerance:±20%")
      (fields
        (field (name "Manufacturer Part") "RK09K1130A5R")
        (field (name "Manufacturer") "ALPSALPINE(阿尔卑斯阿尔派)")
      )
      (libsource (lib "easyedapro") (part "RK09K1130A5R"))
    )
    (comp (ref "Screen2")
      (value "HS96L03W2C03")
      (footprint "easyedapro:Connector_JST:JST_EH_S4B-EH_1x04_P2.50mm_Horizontal")
      (fields (field (name "Manufacturer") "HS(汉昇)"))
      (libsource (lib "easyedapro") (part "Connector_Generic_Conn_01x04"))
    )
    (comp (ref "SW50")
      (value "HX B3F-4055-Y")
      (footprint "easyedapro:Button_Switch_SMD:SW_SPST_PTS645")
      (fields (field (name "Manufacturer") "hanxia(韩下)"))
      (libsource (lib "easyedapro") (part "Switch_SW_Push"))
    )
    (comp (ref "SW51")
      (value "HX B3F-4055-Y")
      (footprint "easyedapro:Button_Switch_SMD:SW_SPST_PTS645")
      (fields (field (name "Manufacturer") "hanxia(韩下)"))
      (libsource (lib "easyedapro") (part "Switch_SW_Push"))
    )
    (comp (ref "SW52")
      (value "HX B3F-4055-Y")
      (footprint "easyedapro:Button_Switch_SMD:SW_SPST_PTS645")
      (fields (field (name "Manufacturer") "hanxia(韩下)"))
      (libsource (lib "easyedapro") (part "Switch_SW_Push"))
    )
    (comp (ref "SW53")
      (value "HX B3F-4055-Y")
      (footprint "easyedapro:Button_Switch_SMD:SW_SPST_PTS645")
      (fields (field (name "Manufacturer") "hanxia(韩下)"))
      (libsource (lib "easyedapro") (part "Switch_SW_Push"))
    )
    (comp (ref "SW54")
      (value "HX B3F-4055-Y")
      (footprint "easyedapro:Button_Switch_SMD:SW_SPST_PTS645")
      (fields (field (name "Manufacturer") "hanxia(韩下)"))
      (libsource (lib "easyedapro") (part "Switch_SW_Push"))
    )
    (comp (ref "SW55")
      (value "HX B3F-4055-Y")
      (footprint "easyedapro:Button_Switch_SMD:SW_SPST_PTS645")
      (fields (field (name "Manufacturer") "hanxia(韩下)"))
      (libsource (lib "easyedapro") (part "Switch_SW_Push"))
    )
    (comp (ref "U24")
      (value "Teensy")
      (footprint "easyedapro:teensy 4.0:MODULE_DEV-15583")
      (libsource (lib "easyedapro") (part "teensy40_DEV-15583"))
    )
    (comp (ref "U25")
      (value "6N138")
      (footprint "easyedapro:Package_DIP:DIP-8_W7.62mm")
      (fields (field (name "Manufacturer") "ISOCOM(英国安数光)"))
      (libsource (lib "easyedapro") (part "Isolator_6N138"))
    )
    (comp (ref "C48")
      (value "1uF")
      (footprint "easyedapro:CAP-SMD_BD6.3-L6.6-W6.6-FD")
      (fields (field (name "Manufacturer Part") "189RV0019") (field (name "Manufacturer") "KNSCHA(科尼盛)"))
      (libsource (lib "easyedapro") (part "189RV0019"))
    )
    (comp (ref "C49")
      (value "1uF")
      (footprint "easyedapro:CAP-SMD_BD6.3-L6.6-W6.6-FD")
      (fields (field (name "Manufacturer Part") "189RV0019") (field (name "Manufacturer") "KNSCHA(科尼盛)"))
      (libsource (lib "easyedapro") (part "189RV0019"))
    )
    (comp (ref "C50")
      (value "100nF")
      (footprint "easyedapro:CAP-TH_L5.0-W2.5-P5.00-D1.0")
      (fields
        (field (name "Manufacturer Part") "CC1H104MC1FD3F6C10MF")
        (field (name "Manufacturer") "Dersonic(德尔创)")
      )
      (libsource (lib "easyedapro") (part "CC1H104MC1FD3F6C10MF"))
    )
    (comp (ref "C51")
      (value "1uF")
      (footprint "easyedapro:CAP-SMD_BD6.3-L6.6-W6.6-FD")
      (fields (field (name "Manufacturer Part") "189RV0019") (field (name "Manufacturer") "KNSCHA(科尼盛)"))
      (libsource (lib "easyedapro") (part "189RV0019"))
    )
    (comp (ref "C52")
      (value "1uF")
      (footprint "easyedapro:CAP-SMD_BD6.3-L6.6-W6.6-FD")
      (fields (field (name "Manufacturer Part") "189RV0019") (field (name "Manufacturer") "KNSCHA(科尼盛)"))
      (libsource (lib "easyedapro") (part "189RV0019"))
    )
    (comp (ref "C122")
      (value "2.2uF")
      (footprint "easyedapro:CAP-TH_L5.0-W2.5-P5.00-D1.0")
      (fields
        (field (name "Manufacturer Part") "CC1H104MC1FD3F6C10MF")
        (field (name "Manufacturer") "Dersonic(德尔创)")
      )
      (libsource (lib "easyedapro") (part "CC1H104MC1FD3F6C10MF"))
    )
    (comp (ref "C123")
      (value "2.2uF")
      (footprint "easyedapro:CAP-TH_L5.0-W2.5-P5.00-D1.0")
      (fields
        (field (name "Manufacturer Part") "CC1H104MC1FD3F6C10MF")
        (field (name "Manufacturer") "Dersonic(德尔创)")
      )
      (libsource (lib "easyedapro") (part "CC1H104MC1FD3F6C10MF"))
    )
    (comp (ref "C124")
      (value "1uF")
      (footprint "easyedapro:CAP-SMD_BD6.3-L6.6-W6.6-FD")
      (fields (field (name "Manufacturer Part") "189RV0019") (field (name "Manufacturer") "KNSCHA(科尼盛)"))
      (libsource (lib "easyedapro") (part "189RV0019"))
    )
    (comp (ref "C125")
      (value "1uF")
      (footprint "easyedapro:CAP-SMD_BD6.3-L6.6-W6.6-FD")
      (fields (field (name "Manufacturer Part") "189RV0019") (field (name "Manufacturer") "KNSCHA(科尼盛)"))
      (libsource (lib "easyedapro") (part "189RV0019"))
    )
    (comp (ref "C126")
      (value "100nF")
      (footprint "easyedapro:CAP-TH_L5.0-W2.5-P5.00-D1.0")
      (fields
        (field (name "Manufacturer Part") "CC1H104MC1FD3F6C10MF")
        (field (name "Manufacturer") "Dersonic(德尔创)")
      )
      (libsource (lib "easyedapro") (part "CC1H104MC1FD3F6C10MF"))
    )
    (comp (ref "C127")
      (value "1uF")
      (footprint "easyedapro:CAP-SMD_BD6.3-L6.6-W6.6-FD")
      (fields (field (name "Manufacturer Part") "189RV0019") (field (name "Manufacturer") "KNSCHA(科尼盛)"))
      (libsource (lib "easyedapro") (part "189RV0019"))
    )
    (comp (ref "C128")
      (value "1uF")
      (footprint "easyedapro:CAP-SMD_BD6.3-L6.6-W6.6-FD")
      (fields (field (name "Manufacturer Part") "189RV0019") (field (name "Manufacturer") "KNSCHA(科尼盛)"))
      (libsource (lib "easyedapro") (part "189RV0019"))
    )
    (comp (ref "C129")
      (value "2.2uF")
      (footprint "easyedapro:CAP-TH_L5.0-W2.5-P5.00-D1.0")
      (fields
        (field (name "Manufacturer Part") "CC1H104MC1FD3F6C10MF")
        (field (name "Manufacturer") "Dersonic(德尔创)")
      )
      (libsource (lib "easyedapro") (part "CC1H104MC1FD3F6C10MF"))
    )
    (comp (ref "C130")
      (value "2.2uF")
      (footprint "easyedapro:CAP-TH_L5.0-W2.5-P5.00-D1.0")
      (fields
        (field (name "Manufacturer Part") "CC1H104MC1FD3F6C10MF")
        (field (name "Manufacturer") "Dersonic(德尔创)")
      )
      (libsource (lib "easyedapro") (part "CC1H104MC1FD3F6C10MF"))
    )
    (comp (ref "C131")
      (value "1uF")
      (footprint "easyedapro:CAP-SMD_BD6.3-L6.6-W6.6-FD")
      (fields (field (name "Manufacturer Part") "189RV0019") (field (name "Manufacturer") "KNSCHA(科尼盛)"))
      (libsource (lib "easyedapro") (part "189RV0019"))
    )
    (comp (ref "C132")
      (value "1uF")
      (footprint "easyedapro:CAP-SMD_BD6.3-L6.6-W6.6-FD")
      (fields (field (name "Manufacturer Part") "189RV0019") (field (name "Manufacturer") "KNSCHA(科尼盛)"))
      (libsource (lib "easyedapro") (part "189RV0019"))
    )
    (comp (ref "C133")
      (value "100nF")
      (footprint "easyedapro:CAP-TH_L5.0-W2.5-P5.00-D1.0")
      (fields
        (field (name "Manufacturer Part") "CC1H104MC1FD3F6C10MF")
        (field (name "Manufacturer") "Dersonic(德尔创)")
      )
      (libsource (lib "easyedapro") (part "CC1H104MC1FD3F6C10MF"))
    )
    (comp (ref "C134")
      (value "1uF")
      (footprint "easyedapro:CAP-SMD_BD6.3-L6.6-W6.6-FD")
      (fields (field (name "Manufacturer Part") "189RV0019") (field (name "Manufacturer") "KNSCHA(科尼盛)"))
      (libsource (lib "easyedapro") (part "189RV0019"))
    )
    (comp (ref "C135")
      (value "1uF")
      (footprint "easyedapro:CAP-SMD_BD6.3-L6.6-W6.6-FD")
      (fields (field (name "Manufacturer Part") "189RV0019") (field (name "Manufacturer") "KNSCHA(科尼盛)"))
      (libsource (lib "easyedapro") (part "189RV0019"))
    )
    (comp (ref "C136")
      (value "2.2uF")
      (footprint "easyedapro:CAP-TH_L5.0-W2.5-P5.00-D1.0")
      (fields
        (field (name "Manufacturer Part") "CC1H104MC1FD3F6C10MF")
        (field (name "Manufacturer") "Dersonic(德尔创)")
      )
      (libsource (lib "easyedapro") (part "CC1H104MC1FD3F6C10MF"))
    )
    (comp (ref "C137")
      (value "2.2uF")
      (footprint "easyedapro:CAP-TH_L5.0-W2.5-P5.00-D1.0")
      (fields
        (field (name "Manufacturer Part") "CC1H104MC1FD3F6C10MF")
        (field (name "Manufacturer") "Dersonic(德尔创)")
      )
      (libsource (lib "easyedapro") (part "CC1H104MC1FD3F6C10MF"))
    )
    (comp (ref "D49")
      (value "1N4148PF")
      (footprint "easyedapro:Diode_THT:D_DO-35_SOD27_P7.62mm_Horizontal")
      (fields (field (name "Manufacturer") "ST(先科)"))
      (libsource (lib "easyedapro") (part "Diode_1N4148"))
    )
    (comp (ref "D50")
      (value "1N4148PF")
      (footprint "easyedapro:Diode_THT:D_DO-35_SOD27_P7.62mm_Horizontal")
      (fields (field (name "Manufacturer") "ST(先科)"))
      (libsource (lib "easyedapro") (part "Diode_1N4148"))
    )
    (comp (ref "D114")
      (value "1N4148PF")
      (footprint "easyedapro:Diode_THT:D_DO-35_SOD27_P7.62mm_Horizontal")
      (fields (field (name "Manufacturer") "ST(先科)"))
      (libsource (lib "easyedapro") (part "Diode_1N4148"))
    )
    (comp (ref "D115")
      (value "1N4148PF")
      (footprint "easyedapro:Diode_THT:D_DO-35_SOD27_P7.62mm_Horizontal")
      (fields (field (name "Manufacturer") "ST(先科)"))
      (libsource (lib "easyedapro") (part "Diode_1N4148"))
    )
    (comp (ref "D116")
      (value "1N4148PF")
      (footprint "easyedapro:Diode_THT:D_DO-35_SOD27_P7.62mm_Horizontal")
      (fields (field (name "Manufacturer") "ST(先科)"))
      (libsource (lib "easyedapro") (part "Diode_1N4148"))
    )
    (comp (ref "D117")
      (value "1N4148PF")
      (footprint "easyedapro:Diode_THT:D_DO-35_SOD27_P7.62mm_Horizontal")
      (fields (field (name "Manufacturer") "ST(先科)"))
      (libsource (lib "easyedapro") (part "Diode_1N4148"))
    )
    (comp (ref "J8")
      (value "HC-PJ-320A")
      (footprint "easyedapro:AUDIO-SMD_HC-PJ-320A")
      (fields (field (name "Manufacturer") "HC(虹成电子)"))
      (libsource (lib "easyedapro") (part "HC-PJ-320A"))
    )
    (comp (ref "J9")
      (value "HC-PJ-320A")
      (footprint "easyedapro:AUDIO-SMD_HC-PJ-320A")
      (fields (field (name "Manufacturer") "HC(虹成电子)"))
      (libsource (lib "easyedapro") (part "HC-PJ-320A"))
    )
    (comp (ref "J16")
      (value "HC-PJ-320A")
      (footprint "easyedapro:AUDIO-SMD_HC-PJ-320A")
      (fields (field (name "Manufacturer") "HC(虹成电子)"))
      (libsource (lib "easyedapro") (part "HC-PJ-320A"))
    )
    (comp (ref "J17")
      (value "HC-PJ-320A")
      (footprint "easyedapro:AUDIO-SMD_HC-PJ-320A")
      (fields (field (name "Manufacturer") "HC(虹成电子)"))
      (libsource (lib "easyedapro") (part "HC-PJ-320A"))
    )
    (comp (ref "J18")
      (value "HC-PJ-320A")
      (footprint "easyedapro:AUDIO-SMD_HC-PJ-320A")
      (fields (field (name "Manufacturer") "HC(虹成电子)"))
      (libsource (lib "easyedapro") (part "HC-PJ-320A"))
    )
    (comp (ref "J19")
      (value "HC-PJ-320A")
      (footprint "easyedapro:AUDIO-SMD_HC-PJ-320A")
      (fields (field (name "Manufacturer") "HC(虹成电子)"))
      (libsource (lib "easyedapro") (part "HC-PJ-320A"))
    )
    (comp (ref "R60")
      (value "100kΩ")
      (footprint "easyedapro:Resistor_THT:R_Axial_DIN0204_L3.6mm_D1.6mm_P2.54mm_Vertical")
      (fields
        (field (name "Manufacturer Part") "RN 1/8W 4K7 F T/B A1")
        (field (name "Manufacturer") "Tyohm(幸亚电阻)")
      )
      (libsource (lib "easyedapro") (part "Device_R"))
    )
    (comp (ref "R61")
      (value "100kΩ")
      (footprint "easyedapro:Resistor_THT:R_Axial_DIN0204_L3.6mm_D1.6mm_P2.54mm_Vertical")
      (fields
        (field (name "Manufacturer Part") "RN 1/8W 4K7 F T/B A1")
        (field (name "Manufacturer") "Tyohm(幸亚电阻)")
      )
      (libsource (lib "easyedapro") (part "Device_R"))
    )
    (comp (ref "R62")
      (value "22kΩ")
      (footprint "easyedapro:Resistor_THT:R_Axial_DIN0204_L3.6mm_D1.6mm_P2.54mm_Vertical")
      (fields
        (field (name "Manufacturer Part") "RN 1/8W 4K7 F T/B A1")
        (field (name "Manufacturer") "Tyohm(幸亚电阻)")
      )
      (libsource (lib "easyedapro") (part "Device_R"))
    )
    (comp (ref "R63")
      (value "10kΩ")
      (footprint "easyedapro:Resistor_THT:R_Axial_DIN0204_L3.6mm_D1.6mm_P2.54mm_Vertical")
      (fields
        (field (name "Manufacturer Part") "RN 1/8W 4K7 F T/B A1")
        (field (name "Manufacturer") "Tyohm(幸亚电阻)")
      )
      (libsource (lib "easyedapro") (part "Device_R"))
    )
    (comp (ref "R64")
      (value "100kΩ")
      (footprint "easyedapro:Resistor_THT:R_Axial_DIN0204_L3.6mm_D1.6mm_P2.54mm_Vertical")
      (fields
        (field (name "Manufacturer Part") "RN 1/8W 4K7 F T/B A1")
        (field (name "Manufacturer") "Tyohm(幸亚电阻)")
      )
      (libsource (lib "easyedapro") (part "Device_R"))
    )
    (comp (ref "R65")
      (value "100kΩ")
      (footprint "easyedapro:Resistor_THT:R_Axial_DIN0204_L3.6mm_D1.6mm_P2.54mm_Vertical")
      (fields
        (field (name "Manufacturer Part") "RN 1/8W 4K7 F T/B A1")
        (field (name "Manufacturer") "Tyohm(幸亚电阻)")
      )
      (libsource (lib "easyedapro") (part "Device_R"))
    )
    (comp (ref "R66")
      (value "22kΩ")
      (footprint "easyedapro:Resistor_THT:R_Axial_DIN0204_L3.6mm_D1.6mm_P2.54mm_Vertical")
      (fields
        (field (name "Manufacturer Part") "RN 1/8W 4K7 F T/B A1")
        (field (name "Manufacturer") "Tyohm(幸亚电阻)")
      )
      (libsource (lib "easyedapro") (part "Device_R"))
    )
    (comp (ref "R67")
      (value "10kΩ")
      (footprint "easyedapro:Resistor_THT:R_Axial_DIN0204_L3.6mm_D1.6mm_P2.54mm_Vertical")
      (fields
        (field (name "Manufacturer Part") "RN 1/8W 4K7 F T/B A1")
        (field (name "Manufacturer") "Tyohm(幸亚电阻)")
      )
      (libsource (lib "easyedapro") (part "Device_R"))
    )
    (comp (ref "R102")
      (value "1kΩ")
      (footprint "easyedapro:Resistor_THT:R_Axial_DIN0204_L3.6mm_D1.6mm_P2.54mm_Vertical")
      (fields
        (field (name "Manufacturer Part") "RN 1/8W 4K7 F T/B A1")
        (field (name "Manufacturer") "Tyohm(幸亚电阻)")
      )
      (libsource (lib "easyedapro") (part "Device_R"))
    )
    (comp (ref "R103")
      (value "1kΩ")
      (footprint "easyedapro:Resistor_THT:R_Axial_DIN0204_L3.6mm_D1.6mm_P2.54mm_Vertical")
      (fields
        (field (name "Manufacturer Part") "RN 1/8W 4K7 F T/B A1")
        (field (name "Manufacturer") "Tyohm(幸亚电阻)")
      )
      (libsource (lib "easyedapro") (part "Device_R"))
    )
    (comp (ref "R104")
      (value "1kΩ")
      (footprint "easyedapro:Resistor_THT:R_Axial_DIN0204_L3.6mm_D1.6mm_P2.54mm_Vertical")
      (fields
        (field (name "Manufacturer Part") "RN 1/8W 4K7 F T/B A1")
        (field (name "Manufacturer") "Tyohm(幸亚电阻)")
      )
      (libsource (lib "easyedapro") (part "Device_R"))
    )
    (comp (ref "R105")
      (value "1kΩ")
      (footprint "easyedapro:Resistor_THT:R_Axial_DIN0204_L3.6mm_D1.6mm_P2.54mm_Vertical")
      (fields
        (field (name "Manufacturer Part") "RN 1/8W 4K7 F T/B A1")
        (field (name "Manufacturer") "Tyohm(幸亚电阻)")
      )
      (libsource (lib "easyedapro") (part "Device_R"))
    )
    (comp (ref "R114")
      (value "4.7KΩ")
      (footprint "easyedapro:R0603")
      (libsource (lib "easyedapro") (part "Res"))
    )
    (comp (ref "R115")
      (value "100kΩ")
      (footprint "easyedapro:Resistor_THT:R_Axial_DIN0204_L3.6mm_D1.6mm_P2.54mm_Vertical")
      (fields
        (field (name "Manufacturer Part") "RN 1/8W 4K7 F T/B A1")
        (field (name "Manufacturer") "Tyohm(幸亚电阻)")
      )
      (libsource (lib "easyedapro") (part "Device_R"))
    )
    (comp (ref "R116")
      (value "68Ω")
      (footprint "easyedapro:Resistor_THT:R_Axial_DIN0204_L3.6mm_D1.6mm_P2.54mm_Vertical")
      (fields
        (field (name "Manufacturer Part") "RN 1/8W 4K7 F T/B A1")
        (field (name "Manufacturer") "Tyohm(幸亚电阻)")
      )
      (libsource (lib "easyedapro") (part "Device_R"))
    )
    (comp (ref "R117")
      (value "68Ω")
      (footprint "easyedapro:Resistor_THT:R_Axial_DIN0204_L3.6mm_D1.6mm_P2.54mm_Vertical")
      (fields
        (field (name "Manufacturer Part") "RN 1/8W 4K7 F T/B A1")
        (field (name "Manufacturer") "Tyohm(幸亚电阻)")
      )
      (libsource (lib "easyedapro") (part "Device_R"))
    )
    (comp (ref "R118")
      (value "100kΩ")
      (footprint "easyedapro:Resistor_THT:R_Axial_DIN0204_L3.6mm_D1.6mm_P2.54mm_Vertical")
      (fields
        (field (name "Manufacturer Part") "RN 1/8W 4K7 F T/B A1")
        (field (name "Manufacturer") "Tyohm(幸亚电阻)")
      )
      (libsource (lib "easyedapro") (part "Device_R"))
    )
    (comp (ref "R119")
      (value "4.7K")
      (footprint "easyedapro:R0603")
      (libsource (lib "easyedapro") (part "Res"))
    )
    (comp (ref "R120")
      (value "100kΩ")
      (footprint "easyedapro:Resistor_THT:R_Axial_DIN0204_L3.6mm_D1.6mm_P2.54mm_Vertical")
      (fields
        (field (name "Manufacturer Part") "RN 1/8W 4K7 F T/B A1")
        (field (name "Manufacturer") "Tyohm(幸亚电阻)")
      )
      (libsource (lib "easyedapro") (part "Device_R"))
    )
    (comp (ref "R121")
      (value "22kΩ")
      (footprint "easyedapro:Resistor_THT:R_Axial_DIN0204_L3.6mm_D1.6mm_P2.54mm_Vertical")
      (fields
        (field (name "Manufacturer Part") "RN 1/8W 4K7 F T/B A1")
        (field (name "Manufacturer") "Tyohm(幸亚电阻)")
      )
      (libsource (lib "easyedapro") (part "Device_R"))
    )
    (comp (ref "R122")
      (value "100kΩ")
      (footprint "easyedapro:Resistor_THT:R_Axial_DIN0204_L3.6mm_D1.6mm_P2.54mm_Vertical")
      (fields
        (field (name "Manufacturer Part") "RN 1/8W 4K7 F T/B A1")
        (field (name "Manufacturer") "Tyohm(幸亚电阻)")
      )
      (libsource (lib "easyedapro") (part "Device_R"))
    )
    (comp (ref "R123")
      (value "100kΩ")
      (footprint "easyedapro:Resistor_THT:R_Axial_DIN0204_L3.6mm_D1.6mm_P2.54mm_Vertical")
      (fields
        (field (name "Manufacturer Part") "RN 1/8W 4K7 F T/B A1")
        (field (name "Manufacturer") "Tyohm(幸亚电阻)")
      )
      (libsource (lib "easyedapro") (part "Device_R"))
    )
    (comp (ref "R124")
      (value "22kΩ")
      (footprint "easyedapro:Resistor_THT:R_Axial_DIN0204_L3.6mm_D1.6mm_P2.54mm_Vertical")
      (fields
        (field (name "Manufacturer Part") "RN 1/8W 4K7 F T/B A1")
        (field (name "Manufacturer") "Tyohm(幸亚电阻)")
      )
      (libsource (lib "easyedapro") (part "Device_R"))
    )
    (comp (ref "R125")
      (value "1kΩ")
      (footprint "easyedapro:Resistor_THT:R_Axial_DIN0204_L3.6mm_D1.6mm_P2.54mm_Vertical")
      (fields
        (field (name "Manufacturer Part") "RN 1/8W 4K7 F T/B A1")
        (field (name "Manufacturer") "Tyohm(幸亚电阻)")
      )
      (libsource (lib "easyedapro") (part "Device_R"))
    )
    (comp (ref "R126")
      (value "1kΩ")
      (footprint "easyedapro:Resistor_THT:R_Axial_DIN0204_L3.6mm_D1.6mm_P2.54mm_Vertical")
      (fields
        (field (name "Manufacturer Part") "RN 1/8W 4K7 F T/B A1")
        (field (name "Manufacturer") "Tyohm(幸亚电阻)")
      )
      (libsource (lib "easyedapro") (part "Device_R"))
    )
    (comp (ref "R127")
      (value "1kΩ")
      (footprint "easyedapro:Resistor_THT:R_Axial_DIN0204_L3.6mm_D1.6mm_P2.54mm_Vertical")
      (fields
        (field (name "Manufacturer Part") "RN 1/8W 4K7 F T/B A1")
        (field (name "Manufacturer") "Tyohm(幸亚电阻)")
      )
      (libsource (lib "easyedapro") (part "Device_R"))
    )
    (comp (ref "R128")
      (value "1kΩ")
      (footprint "easyedapro:Resistor_THT:R_Axial_DIN0204_L3.6mm_D1.6mm_P2.54mm_Vertical")
      (fields
        (field (name "Manufacturer Part") "RN 1/8W 4K7 F T/B A1")
        (field (name "Manufacturer") "Tyohm(幸亚电阻)")
      )
      (libsource (lib "easyedapro") (part "Device_R"))
    )
    (comp (ref "R129")
      (value "100kΩ")
      (footprint "easyedapro:Resistor_THT:R_Axial_DIN0204_L3.6mm_D1.6mm_P2.54mm_Vertical")
      (fields
        (field (name "Manufacturer Part") "RN 1/8W 4K7 F T/B A1")
        (field (name "Manufacturer") "Tyohm(幸亚电阻)")
      )
      (libsource (lib "easyedapro") (part "Device_R"))
    )
    (comp (ref "R130")
      (value "4.7KΩ")
      (footprint "easyedapro:R0603")
      (libsource (lib "easyedapro") (part "Res"))
    )
    (comp (ref "R131")
      (value "100kΩ")
      (footprint "easyedapro:Resistor_THT:R_Axial_DIN0204_L3.6mm_D1.6mm_P2.54mm_Vertical")
      (fields
        (field (name "Manufacturer Part") "RN 1/8W 4K7 F T/B A1")
        (field (name "Manufacturer") "Tyohm(幸亚电阻)")
      )
      (libsource (lib "easyedapro") (part "Device_R"))
    )
    (comp (ref "R132")
      (value "10kΩ")
      (footprint "easyedapro:Resistor_THT:R_Axial_DIN0204_L3.6mm_D1.6mm_P2.54mm_Vertical")
      (fields
        (field (name "Manufacturer Part") "RN 1/8W 4K7 F T/B A1")
        (field (name "Manufacturer") "Tyohm(幸亚电阻)")
      )
      (libsource (lib "easyedapro") (part "Device_R"))
    )
    (comp (ref "R133")
      (value "68Ω")
      (footprint "easyedapro:Resistor_THT:R_Axial_DIN0204_L3.6mm_D1.6mm_P2.54mm_Vertical")
      (fields
        (field (name "Manufacturer Part") "RN 1/8W 4K7 F T/B A1")
        (field (name "Manufacturer") "Tyohm(幸亚电阻)")
      )
      (libsource (lib "easyedapro") (part "Device_R"))
    )
    (comp (ref "R134")
      (value "10kΩ")
      (footprint "easyedapro:Resistor_THT:R_Axial_DIN0204_L3.6mm_D1.6mm_P2.54mm_Vertical")
      (fields
        (field (name "Manufacturer Part") "RN 1/8W 4K7 F T/B A1")
        (field (name "Manufacturer") "Tyohm(幸亚电阻)")
      )
      (libsource (lib "easyedapro") (part "Device_R"))
    )
    (comp (ref "R135")
      (value "68Ω")
      (footprint "easyedapro:Resistor_THT:R_Axial_DIN0204_L3.6mm_D1.6mm_P2.54mm_Vertical")
      (fields
        (field (name "Manufacturer Part") "RN 1/8W 4K7 F T/B A1")
        (field (name "Manufacturer") "Tyohm(幸亚电阻)")
      )
      (libsource (lib "easyedapro") (part "Device_R"))
    )
    (comp (ref "R136")
      (value "100kΩ")
      (footprint "easyedapro:Resistor_THT:R_Axial_DIN0204_L3.6mm_D1.6mm_P2.54mm_Vertical")
      (fields
        (field (name "Manufacturer Part") "RN 1/8W 4K7 F T/B A1")
        (field (name "Manufacturer") "Tyohm(幸亚电阻)")
      )
      (libsource (lib "easyedapro") (part "Device_R"))
    )
    (comp (ref "R137")
      (value "4.7K")
      (footprint "easyedapro:R0603")
      (libsource (lib "easyedapro") (part "Res"))
    )
    (comp (ref "R138")
      (value "100kΩ")
      (footprint "easyedapro:Resistor_THT:R_Axial_DIN0204_L3.6mm_D1.6mm_P2.54mm_Vertical")
      (fields
        (field (name "Manufacturer Part") "RN 1/8W 4K7 F T/B A1")
        (field (name "Manufacturer") "Tyohm(幸亚电阻)")
      )
      (libsource (lib "easyedapro") (part "Device_R"))
    )
    (comp (ref "R139")
      (value "22kΩ")
      (footprint "easyedapro:Resistor_THT:R_Axial_DIN0204_L3.6mm_D1.6mm_P2.54mm_Vertical")
      (fields
        (field (name "Manufacturer Part") "RN 1/8W 4K7 F T/B A1")
        (field (name "Manufacturer") "Tyohm(幸亚电阻)")
      )
      (libsource (lib "easyedapro") (part "Device_R"))
    )
    (comp (ref "R140")
      (value "100kΩ")
      (footprint "easyedapro:Resistor_THT:R_Axial_DIN0204_L3.6mm_D1.6mm_P2.54mm_Vertical")
      (fields
        (field (name "Manufacturer Part") "RN 1/8W 4K7 F T/B A1")
        (field (name "Manufacturer") "Tyohm(幸亚电阻)")
      )
      (libsource (lib "easyedapro") (part "Device_R"))
    )
    (comp (ref "R141")
      (value "100kΩ")
      (footprint "easyedapro:Resistor_THT:R_Axial_DIN0204_L3.6mm_D1.6mm_P2.54mm_Vertical")
      (fields
        (field (name "Manufacturer Part") "RN 1/8W 4K7 F T/B A1")
        (field (name "Manufacturer") "Tyohm(幸亚电阻)")
      )
      (libsource (lib "easyedapro") (part "Device_R"))
    )
    (comp (ref "R142")
      (value "22kΩ")
      (footprint "easyedapro:Resistor_THT:R_Axial_DIN0204_L3.6mm_D1.6mm_P2.54mm_Vertical")
      (fields
        (field (name "Manufacturer Part") "RN 1/8W 4K7 F T/B A1")
        (field (name "Manufacturer") "Tyohm(幸亚电阻)")
      )
      (libsource (lib "easyedapro") (part "Device_R"))
    )
    (comp (ref "R143")
      (value "1kΩ")
      (footprint "easyedapro:Resistor_THT:R_Axial_DIN0204_L3.6mm_D1.6mm_P2.54mm_Vertical")
      (fields
        (field (name "Manufacturer Part") "RN 1/8W 4K7 F T/B A1")
        (field (name "Manufacturer") "Tyohm(幸亚电阻)")
      )
      (libsource (lib "easyedapro") (part "Device_R"))
    )
    (comp (ref "R144")
      (value "1kΩ")
      (footprint "easyedapro:Resistor_THT:R_Axial_DIN0204_L3.6mm_D1.6mm_P2.54mm_Vertical")
      (fields
        (field (name "Manufacturer Part") "RN 1/8W 4K7 F T/B A1")
        (field (name "Manufacturer") "Tyohm(幸亚电阻)")
      )
      (libsource (lib "easyedapro") (part "Device_R"))
    )
    (comp (ref "R145")
      (value "1kΩ")
      (footprint "easyedapro:Resistor_THT:R_Axial_DIN0204_L3.6mm_D1.6mm_P2.54mm_Vertical")
      (fields
        (field (name "Manufacturer Part") "RN 1/8W 4K7 F T/B A1")
        (field (name "Manufacturer") "Tyohm(幸亚电阻)")
      )
      (libsource (lib "easyedapro") (part "Device_R"))
    )
    (comp (ref "R146")
      (value "1kΩ")
      (footprint "easyedapro:Resistor_THT:R_Axial_DIN0204_L3.6mm_D1.6mm_P2.54mm_Vertical")
      (fields
        (field (name "Manufacturer Part") "RN 1/8W 4K7 F T/B A1")
        (field (name "Manufacturer") "Tyohm(幸亚电阻)")
      )
      (libsource (lib "easyedapro") (part "Device_R"))
    )
    (comp (ref "R147")
      (value "100kΩ")
      (footprint "easyedapro:Resistor_THT:R_Axial_DIN0204_L3.6mm_D1.6mm_P2.54mm_Vertical")
      (fields
        (field (name "Manufacturer Part") "RN 1/8W 4K7 F T/B A1")
        (field (name "Manufacturer") "Tyohm(幸亚电阻)")
      )
      (libsource (lib "easyedapro") (part "Device_R"))
    )
    (comp (ref "R148")
      (value "4.7KΩ")
      (footprint "easyedapro:R0603")
      (libsource (lib "easyedapro") (part "Res"))
    )
    (comp (ref "R149")
      (value "100kΩ")
      (footprint "easyedapro:Resistor_THT:R_Axial_DIN0204_L3.6mm_D1.6mm_P2.54mm_Vertical")
      (fields
        (field (name "Manufacturer Part") "RN 1/8W 4K7 F T/B A1")
        (field (name "Manufacturer") "Tyohm(幸亚电阻)")
      )
      (libsource (lib "easyedapro") (part "Device_R"))
    )
    (comp (ref "R150")
      (value "10kΩ")
      (footprint "easyedapro:Resistor_THT:R_Axial_DIN0204_L3.6mm_D1.6mm_P2.54mm_Vertical")
      (fields
        (field (name "Manufacturer Part") "RN 1/8W 4K7 F T/B A1")
        (field (name "Manufacturer") "Tyohm(幸亚电阻)")
      )
      (libsource (lib "easyedapro") (part "Device_R"))
    )
    (comp (ref "R151")
      (value "68Ω")
      (footprint "easyedapro:Resistor_THT:R_Axial_DIN0204_L3.6mm_D1.6mm_P2.54mm_Vertical")
      (fields
        (field (name "Manufacturer Part") "RN 1/8W 4K7 F T/B A1")
        (field (name "Manufacturer") "Tyohm(幸亚电阻)")
      )
      (libsource (lib "easyedapro") (part "Device_R"))
    )
    (comp (ref "R152")
      (value "10kΩ")
      (footprint "easyedapro:Resistor_THT:R_Axial_DIN0204_L3.6mm_D1.6mm_P2.54mm_Vertical")
      (fields
        (field (name "Manufacturer Part") "RN 1/8W 4K7 F T/B A1")
        (field (name "Manufacturer") "Tyohm(幸亚电阻)")
      )
      (libsource (lib "easyedapro") (part "Device_R"))
    )
    (comp (ref "R153")
      (value "68Ω")
      (footprint "easyedapro:Resistor_THT:R_Axial_DIN0204_L3.6mm_D1.6mm_P2.54mm_Vertical")
      (fields
        (field (name "Manufacturer Part") "RN 1/8W 4K7 F T/B A1")
        (field (name "Manufacturer") "Tyohm(幸亚电阻)")
      )
      (libsource (lib "easyedapro") (part "Device_R"))
    )
    (comp (ref "R154")
      (value "100kΩ")
      (footprint "easyedapro:Resistor_THT:R_Axial_DIN0204_L3.6mm_D1.6mm_P2.54mm_Vertical")
      (fields
        (field (name "Manufacturer Part") "RN 1/8W 4K7 F T/B A1")
        (field (name "Manufacturer") "Tyohm(幸亚电阻)")
      )
      (libsource (lib "easyedapro") (part "Device_R"))
    )
    (comp (ref "R155")
      (value "4.7K")
      (footprint "easyedapro:R0603")
      (libsource (lib "easyedapro") (part "Res"))
    )
    (comp (ref "U23")
      (value "MCP6002DRG")
      (footprint "easyedapro:SOP-8_L4.9-W3.9-P1.27-LS6.0-BL")
      (fields (field (name "Manufacturer") "HGC(深圳汉芯)"))
      (libsource (lib "easyedapro") (part "MCP6002DRG"))
    )
    (comp (ref "U26")
      (value "ESD9B5.0ST5G")
      (footprint "easyedapro:SOD-923_L0.8-W0.6-LS1.0-BI")
      (fields (field (name "Manufacturer") "TECH PUBLIC(台舟)"))
      (libsource (lib "easyedapro") (part "ESD9B5.0ST5G_C3021104"))
    )
    (comp (ref "U27")
      (value "ESD9B5.0ST5G")
      (footprint "easyedapro:SOD-923_L0.8-W0.6-LS1.0-BI")
      (fields (field (name "Manufacturer") "TECH PUBLIC(台舟)"))
      (libsource (lib "easyedapro") (part "ESD9B5.0ST5G_C3021104"))
    )
    (comp (ref "U28")
      (value "ESD9B5.0ST5G")
      (footprint "easyedapro:SOD-923_L0.8-W0.6-LS1.0-BI")
      (fields (field (name "Manufacturer") "TECH PUBLIC(台舟)"))
      (libsource (lib "easyedapro") (part "ESD9B5.0ST5G_C3021104"))
    )
    (comp (ref "U29")
      (value "ESD9B5.0ST5G")
      (footprint "easyedapro:SOD-923_L0.8-W0.6-LS1.0-BI")
      (fields (field (name "Manufacturer") "TECH PUBLIC(台舟)"))
      (libsource (lib "easyedapro") (part "ESD9B5.0ST5G_C3021104"))
    )
    (comp (ref "U30")
      (value "ESD9B5.0ST5G")
      (footprint "easyedapro:SOD-923_L0.8-W0.6-LS1.0-BI")
      (fields (field (name "Manufacturer") "TECH PUBLIC(台舟)"))
      (libsource (lib "easyedapro") (part "ESD9B5.0ST5G_C3021104"))
    )
    (comp (ref "U31")
      (value "ESD9B5.0ST5G")
      (footprint "easyedapro:SOD-923_L0.8-W0.6-LS1.0-BI")
      (fields (field (name "Manufacturer") "TECH PUBLIC(台舟)"))
      (libsource (lib "easyedapro") (part "ESD9B5.0ST5G_C3021104"))
    )
    (comp (ref "U32")
      (value "ESD9B5.0ST5G")
      (footprint "easyedapro:SOD-923_L0.8-W0.6-LS1.0-BI")
      (fields (field (name "Manufacturer") "TECH PUBLIC(台舟)"))
      (libsource (lib "easyedapro") (part "ESD9B5.0ST5G_C3021104"))
    )
    (comp (ref "U33")
      (value "ESD9B5.0ST5G")
      (footprint "easyedapro:SOD-923_L0.8-W0.6-LS1.0-BI")
      (fields (field (name "Manufacturer") "TECH PUBLIC(台舟)"))
      (libsource (lib "easyedapro") (part "ESD9B5.0ST5G_C3021104"))
    )
    (comp (ref "U34")
      (value "MCP6002DRG")
      (footprint "easyedapro:SOP-8_L4.9-W3.9-P1.27-LS6.0-BL")
      (fields (field (name "Manufacturer") "HGC(深圳汉芯)"))
      (libsource (lib "easyedapro") (part "MCP6002DRG"))
    )
    (comp (ref "U35")
      (value "ESD9B5.0ST5G")
      (footprint "easyedapro:SOD-923_L0.8-W0.6-LS1.0-BI")
      (fields (field (name "Manufacturer") "TECH PUBLIC(台舟)"))
      (libsource (lib "easyedapro") (part "ESD9B5.0ST5G_C3021104"))
    )
    (comp (ref "U36")
      (value "ESD9B5.0ST5G")
      (footprint "easyedapro:SOD-923_L0.8-W0.6-LS1.0-BI")
      (fields (field (name "Manufacturer") "TECH PUBLIC(台舟)"))
      (libsource (lib "easyedapro") (part "ESD9B5.0ST5G_C3021104"))
    )
    (comp (ref "U37")
      (value "ESD9B5.0ST5G")
      (footprint "easyedapro:SOD-923_L0.8-W0.6-LS1.0-BI")
      (fields (field (name "Manufacturer") "TECH PUBLIC(台舟)"))
      (libsource (lib "easyedapro") (part "ESD9B5.0ST5G_C3021104"))
    )
    (comp (ref "U38")
      (value "ESD9B5.0ST5G")
      (footprint "easyedapro:SOD-923_L0.8-W0.6-LS1.0-BI")
      (fields (field (name "Manufacturer") "TECH PUBLIC(台舟)"))
      (libsource (lib "easyedapro") (part "ESD9B5.0ST5G_C3021104"))
    )
    (comp (ref "U39")
      (value "MCP6002DRG")
      (footprint "easyedapro:SOP-8_L4.9-W3.9-P1.27-LS6.0-BL")
      (fields (field (name "Manufacturer") "HGC(深圳汉芯)"))
      (libsource (lib "easyedapro") (part "MCP6002DRG"))
    )
  )
  (nets
    (net (code "1") (name "3VDC") (class "Default")
      (node (ref "C126") (pin "2") (pinfunction "2_2") (pintype "unspecified"))
      (node (ref "C133") (pin "2") (pinfunction "2_2") (pintype "unspecified"))
      (node (ref "C50") (pin "2") (pinfunction "2_2") (pintype "unspecified"))
      (node (ref "C62") (pin "2") (pinfunction "~_2") (pintype "unspecified"))
      (node (ref "C63") (pin "2") (pinfunction "~_2") (pintype "unspecified"))
      (node (ref "C73") (pin "1") (pinfunction "~_1") (pintype "unspecified"))
      (node (ref "C74") (pin "1") (pinfunction "1_1") (pintype "input"))
      (node (ref "COL_MUX2") (pin "24") (pinfunction "VCC_24") (pintype "unspecified"))
      (node (ref "D114") (pin "1") (pinfunction "K_1") (pintype "unspecified"))
      (node (ref "D116") (pin "1") (pinfunction "K_1") (pintype "unspecified"))
      (node (ref "D49") (pin "1") (pinfunction "K_1") (pintype "unspecified"))
      (node (ref "R120") (pin "1") (pinfunction "~_1") (pintype "unspecified"))
      (node (ref "R123") (pin "1") (pinfunction "~_1") (pintype "unspecified"))
      (node (ref "R132") (pin "2") (pinfunction "~_2") (pintype "unspecified"))
      (node (ref "R138") (pin "1") (pinfunction "~_1") (pintype "unspecified"))
      (node (ref "R141") (pin "1") (pinfunction "~_1") (pintype "unspecified"))
      (node (ref "R150") (pin "2") (pinfunction "~_2") (pintype "unspecified"))
      (node (ref "R61") (pin "1") (pinfunction "~_1") (pintype "unspecified"))
      (node (ref "R63") (pin "2") (pinfunction "~_2") (pintype "unspecified"))
      (node (ref "R65") (pin "1") (pinfunction "~_1") (pintype "unspecified"))
      (node (ref "R72") (pin "1") (pinfunction "~_1") (pintype "unspecified"))
      (node (ref "R73") (pin "1") (pinfunction "~_1") (pintype "unspecified"))
      (node (ref "R74") (pin "1") (pinfunction "~_1") (pintype "unspecified"))
      (node (ref "R75") (pin "1") (pinfunction "~_1") (pintype "unspecified"))
      (node (ref "R76") (pin "1") (pinfunction "~_1") (pintype "unspecified"))
      (node (ref "R77") (pin "1") (pinfunction "~_1") (pintype "unspecified"))
      (node (ref "R88") (pin "1") (pinfunction "~_1") (pintype "unspecified"))
      (node (ref "R92") (pin "1") (pinfunction "~_1") (pintype "unspecified"))
      (node (ref "ROW_MUX2") (pin "24") (pinfunction "VCC_24") (pintype "unspecified"))
      (node (ref "RV4") (pin "1") (pinfunction "1_1") (pintype "unspecified"))
      (node (ref "RV5") (pin "1") (pinfunction "1_1") (pintype "unspecified"))
      (node (ref "RV6") (pin "1") (pinfunction "1_1") (pintype "unspecified"))
      (node (ref "SW50") (pin "2") (pinfunction "2_2") (pintype "unspecified"))
      (node (ref "SW51") (pin "2") (pinfunction "2_2") (pintype "unspecified"))
      (node (ref "SW52") (pin "2") (pinfunction "2_2") (pintype "unspecified"))
      (node (ref "SW53") (pin "2") (pinfunction "2_2") (pintype "unspecified"))
      (node (ref "SW54") (pin "2") (pinfunction "2_2") (pintype "unspecified"))
      (node (ref "SW55") (pin "2") (pinfunction "2_2") (pintype "unspecified"))
      (node (ref "Screen2") (pin "2") (pinfunction "Pin_2_2") (pintype "unspecified"))
      (node (ref "U23") (pin "2") (pinfunction "INA-_2") (pintype "unspecified"))
      (node (ref "U23") (pin "8") (pinfunction "VDD_8") (pintype "unspecified"))
      (node (ref "U24") (pin "3.3V_2") (pinfunction "3.3V_2_3.3V_2") (pintype "unspecified"))
      (node (ref "U34") (pin "2") (pinfunction "INA-_2") (pintype "unspecified"))
      (node (ref "U34") (pin "8") (pinfunction "VDD_8") (pintype "unspecified"))
      (node (ref "U39") (pin "2") (pinfunction "INA-_2") (pintype "unspecified"))
      (node (ref "U39") (pin "8") (pinfunction "VDD_8") (pintype "unspecified"))
    )
    (net (code "2") (name "5VDC") (class "Default")
      (node (ref "C64") (pin "2") (pinfunction "~_2") (pintype "unspecified"))
      (node (ref "C8") (pin "1") (pinfunction "~_1") (pintype "unspecified"))
      (node (ref "C9") (pin "1") (pinfunction "~_1") (pintype "unspecified"))
      (node (ref "R85") (pin "2") (pinfunction "~_2") (pintype "unspecified"))
      (node (ref "R93") (pin "2") (pinfunction "~_2") (pintype "unspecified"))
      (node (ref "SW49") (pin "5") (pinfunction "5_5") (pintype "unspecified"))
      (node (ref "U25") (pin "7") (pinfunction "VO1_7") (pintype "unspecified"))
      (node (ref "U8") (pin "14") (pinfunction "VCC_14") (pintype "unspecified"))
    )
    (net (code "3") (name "CNTRLLP") (class "Default")
      (node (ref "C75") (pin "1") (pinfunction "~_1") (pintype "unspecified"))
      (node (ref "D102") (pin "3") (pinfunction "VSS_3") (pintype "unspecified"))
    )
    (net (code "4") (name "CNTRL_LED") (class "Default")
      (node (ref "D102") (pin "2") (pinfunction "DOUT_2") (pintype "output"))
      (node (ref "D104") (pin "4") (pinfunction "DIN_4") (pintype "input"))
    )
    (net (code "5") (name "COL1") (class "Default")
      (node (ref "COL_MUX2") (pin "9") (pinfunction "I0_9") (pintype "unspecified"))
      (node (ref "R72") (pin "2") (pinfunction "~_2") (pintype "unspecified"))
      (node (ref "SW1") (pin "2") (pinfunction "2_2") (pintype "unspecified"))
      (node (ref "SW2") (pin "2") (pinfunction "2_2") (pintype "unspecified"))
      (node (ref "SW3") (pin "2") (pinfunction "2_2") (pintype "unspecified"))
      (node (ref "SW4") (pin "2") (pinfunction "2_2") (pintype "unspecified"))
      (node (ref "SW5") (pin "2") (pinfunction "2_2") (pintype "unspecified"))
      (node (ref "SW6") (pin "2") (pinfunction "2_2") (pintype "unspecified"))
      (node (ref "SW7") (pin "2") (pinfunction "2_2") (pintype "unspecified"))
    )
    (net (code "6") (name "COL2") (class "Default")
      (node (ref "COL_MUX2") (pin "8") (pinfunction "I1_8") (pintype "unspecified"))
      (node (ref "R73") (pin "2") (pinfunction "~_2") (pintype "unspecified"))
      (node (ref "SW10") (pin "2") (pinfunction "2_2") (pintype "unspecified"))
      (node (ref "SW11") (pin "2") (pinfunction "2_2") (pintype "unspecified"))
      (node (ref "SW12") (pin "2") (pinfunction "2_2") (pintype "unspecified"))
      (node (ref "SW13") (pin "2") (pinfunction "2_2") (pintype "unspecified"))
      (node (ref "SW14") (pin "2") (pinfunction "2_2") (pintype "unspecified"))
      (node (ref "SW8") (pin "2") (pinfunction "2_2") (pintype "unspecified"))
      (node (ref "SW9") (pin "2") (pinfunction "2_2") (pintype "unspecified"))
    )
    (net (code "7") (name "COL3") (class "Default")
      (node (ref "COL_MUX2") (pin "7") (pinfunction "I2_7") (pintype "unspecified"))
      (node (ref "R74") (pin "2") (pinfunction "~_2") (pintype "unspecified"))
      (node (ref "SW15") (pin "2") (pinfunction "2_2") (pintype "unspecified"))
      (node (ref "SW16") (pin "2") (pinfunction "2_2") (pintype "unspecified"))
      (node (ref "SW17") (pin "2") (pinfunction "2_2") (pintype "unspecified"))
      (node (ref "SW18") (pin "2") (pinfunction "2_2") (pintype "unspecified"))
      (node (ref "SW19") (pin "2") (pinfunction "2_2") (pintype "unspecified"))
      (node (ref "SW20") (pin "2") (pinfunction "2_2") (pintype "unspecified"))
      (node (ref "SW21") (pin "2") (pinfunction "2_2") (pintype "unspecified"))
    )
    (net (code "8") (name "COL4") (class "Default")
      (node (ref "COL_MUX2") (pin "6") (pinfunction "I3_6") (pintype "unspecified"))
      (node (ref "R75") (pin "2") (pinfunction "~_2") (pintype "unspecified"))
      (node (ref "SW22") (pin "2") (pinfunction "2_2") (pintype "unspecified"))
      (node (ref "SW23") (pin "2") (pinfunction "2_2") (pintype "unspecified"))
      (node (ref "SW24") (pin "2") (pinfunction "2_2") (pintype "unspecified"))
      (node (ref "SW25") (pin "2") (pinfunction "2_2") (pintype "unspecified"))
      (node (ref "SW26") (pin "2") (pinfunction "2_2") (pintype "unspecified"))
      (node (ref "SW27") (pin "2") (pinfunction "2_2") (pintype "unspecified"))
      (node (ref "SW28") (pin "2") (pinfunction "2_2") (pintype "unspecified"))
    )
    (net (code "9") (name "COL5") (class "Default")
      (node (ref "COL_MUX2") (pin "5") (pinfunction "I4_5") (pintype "unspecified"))
      (node (ref "R76") (pin "2") (pinfunction "~_2") (pintype "unspecified"))
      (node (ref "SW29") (pin "2") (pinfunction "2_2") (pintype "unspecified"))
      (node (ref "SW30") (pin "2") (pinfunction "2_2") (pintype "unspecified"))
      (node (ref "SW31") (pin "2") (pinfunction "2_2") (pintype "unspecified"))
      (node (ref "SW32") (pin "2") (pinfunction "2_2") (pintype "unspecified"))
      (node (ref "SW33") (pin "2") (pinfunction "2_2") (pintype "unspecified"))
      (node (ref "SW34") (pin "2") (pinfunction "2_2") (pintype "unspecified"))
      (node (ref "SW35") (pin "2") (pinfunction "2_2") (pintype "unspecified"))
    )
    (net (code "10") (name "COL6") (class "Default")
      (node (ref "COL_MUX2") (pin "4") (pinfunction "I5_4") (pintype "unspecified"))
      (node (ref "R77") (pin "2") (pinfunction "~_2") (pintype "unspecified"))
      (node (ref "SW36") (pin "2") (pinfunction "2_2") (pintype "unspecified"))
      (node (ref "SW37") (pin "2") (pinfunction "2_2") (pintype "unspecified"))
      (node (ref "SW38") (pin "2") (pinfunction "2_2") (pintype "unspecified"))
      (node (ref "SW39") (pin "2") (pinfunction "2_2") (pintype "unspecified"))
      (node (ref "SW40") (pin "2") (pinfunction "2_2") (pintype "unspecified"))
      (node (ref "SW41") (pin "2") (pinfunction "2_2") (pintype "unspecified"))
      (node (ref "SW42") (pin "2") (pinfunction "2_2") (pintype "unspecified"))
    )
    (net (code "11") (name "CTRL1") (class "Default")
      (node (ref "COL_MUX2") (pin "2") (pinfunction "I7_2") (pintype "unspecified"))
      (node (ref "SW55") (pin "1") (pinfunction "1_1") (pintype "unspecified"))
    )
    (net (code "12") (name "CTRL2") (class "Default")
      (node (ref "COL_MUX2") (pin "23") (pinfunction "I8_23") (pintype "unspecified"))
      (node (ref "SW54") (pin "1") (pinfunction "1_1") (pintype "unspecified"))
    )
    (net (code "13") (name "CTRL3") (class "Default")
      (node (ref "COL_MUX2") (pin "22") (pinfunction "I9_22") (pintype "unspecified"))
      (node (ref "SW53") (pin "1") (pinfunction "1_1") (pintype "unspecified"))
    )
    (net (code "14") (name "CTRL4") (class "Default")
      (node (ref "COL_MUX2") (pin "21") (pinfunction "I10_21") (pintype "unspecified"))
      (node (ref "SW52") (pin "1") (pinfunction "1_1") (pintype "unspecified"))
    )
    (net (code "15") (name "CTRL5") (class "Default")
      (node (ref "COL_MUX2") (pin "20") (pinfunction "I11_20") (pintype "unspecified"))
      (node (ref "SW51") (pin "1") (pinfunction "1_1") (pintype "unspecified"))
    )
    (net (code "16") (name "CTRL6") (class "Default")
      (node (ref "COL_MUX2") (pin "19") (pinfunction "I12_19") (pintype "unspecified"))
      (node (ref "SW50") (pin "1") (pinfunction "1_1") (pintype "unspecified"))
    )
    (net (code "17") (name "E1") (class "Default")
      (node (ref "C49") (pin "1") (pinfunction "1_1") (pintype "input"))
      (node (ref "R116") (pin "2") (pinfunction "~_2") (pintype "unspecified"))
      (node (ref "R96") (pin "1") (pinfunction "~_1") (pintype "unspecified"))
    )
    (net (code "18") (name "E2") (class "Default")
      (node (ref "C52") (pin "2") (pinfunction "2_2") (pintype "input"))
      (node (ref "R117") (pin "2") (pinfunction "~_2") (pintype "unspecified"))
      (node (ref "R97") (pin "1") (pinfunction "~_1") (pintype "unspecified"))
    )
    (net (code "19") (name "E3") (class "Default")
      (node (ref "C125") (pin "1") (pinfunction "1_1") (pintype "input"))
      (node (ref "R133") (pin "2") (pinfunction "~_2") (pintype "unspecified"))
      (node (ref "R98") (pin "1") (pinfunction "~_1") (pintype "unspecified"))
    )
    (net (code "20") (name "E4") (class "Default")
      (node (ref "C128") (pin "2") (pinfunction "2_2") (pintype "input"))
      (node (ref "R135") (pin "2") (pinfunction "~_2") (pintype "unspecified"))
      (node (ref "R99") (pin "1") (pinfunction "~_1") (pintype "unspecified"))
    )
    (net (code "21") (name "E5") (class "Default")
      (node (ref "C132") (pin "1") (pinfunction "1_1") (pintype "input"))
      (node (ref "R100") (pin "1") (pinfunction "~_1") (pintype "unspecified"))
      (node (ref "R151") (pin "2") (pinfunction "~_2") (pintype "unspecified"))
    )
    (net (code "22") (name "E6") (class "Default")
      (node (ref "C135") (pin "2") (pinfunction "2_2") (pintype "input"))
      (node (ref "R101") (pin "1") (pinfunction "~_1") (pintype "unspecified"))
      (node (ref "R153") (pin "2") (pinfunction "~_2") (pintype "unspecified"))
    )
    (net (code "23") (name "FP1") (class "Default")
      (node (ref "COL_MUX2") (pin "17") (pinfunction "I14_17") (pintype "unspecified"))
      (node (ref "RV4") (pin "2") (pinfunction "2_2") (pintype "unspecified"))
    )
    (net (code "24") (name "FP2") (class "Default")
      (node (ref "COL_MUX2") (pin "16") (pinfunction "I15_16") (pintype "unspecified"))
      (node (ref "RV5") (pin "2") (pinfunction "2_2") (pintype "unspecified"))
    )
    (net (code "25") (name "GND") (class "Default")
      (node (ref "C100") (pin "2") (pinfunction "~_2") (pintype "unspecified"))
      (node (ref "C101") (pin "2") (pinfunction "~_2") (pintype "unspecified"))
      (node (ref "C102") (pin "2") (pinfunction "~_2") (pintype "unspecified"))
      (node (ref "C103") (pin "2") (pinfunction "~_2") (pintype "unspecified"))
      (node (ref "C104") (pin "2") (pinfunction "~_2") (pintype "unspecified"))
      (node (ref "C105") (pin "2") (pinfunction "~_2") (pintype "unspecified"))
      (node (ref "C106") (pin "2") (pinfunction "~_2") (pintype "unspecified"))
      (node (ref "C107") (pin "2") (pinfunction "~_2") (pintype "unspecified"))
      (node (ref "C108") (pin "2") (pinfunction "~_2") (pintype "unspecified"))
      (node (ref "C109") (pin "2") (pinfunction "~_2") (pintype "unspecified"))
      (node (ref "C110") (pin "2") (pinfunction "~_2") (pintype "unspecified"))
      (node (ref "C111") (pin "2") (pinfunction "~_2") (pintype "unspecified"))
      (node (ref "C112") (pin "2") (pinfunction "~_2") (pintype "unspecified"))
      (node (ref "C113") (pin "2") (pinfunction "~_2") (pintype "unspecified"))
      (node (ref "C114") (pin "2") (pinfunction "~_2") (pintype "unspecified"))
      (node (ref "C115") (pin "2") (pinfunction "~_2") (pintype "unspecified"))
      (node (ref "C116") (pin "2") (pinfunction "~_2") (pintype "unspecified"))
      (node (ref "C117") (pin "2") (pinfunction "~_2") (pintype "unspecified"))
      (node (ref "C118") (pin "2") (pinfunction "~_2") (pintype "unspecified"))
      (node (ref "C119") (pin "2") (pinfunction "~_2") (pintype "unspecified"))
      (node (ref "C120") (pin "2") (pinfunction "~_2") (pintype "unspecified"))
      (node (ref "C121") (pin "2") (pinfunction "2_2") (pintype "input"))
      (node (ref "C124") (pin "1") (pinfunction "1_1") (pintype "input"))
      (node (ref "C125") (pin "2") (pinfunction "2_2") (pintype "input"))
      (node (ref "C126") (pin "1") (pinfunction "1_1") (pintype "unspecified"))
      (node (ref "C127") (pin "1") (pinfunction "1_1") (pintype "input"))
      (node (ref "C128") (pin "1") (pinfunction "1_1") (pintype "input"))
      (node (ref "C131") (pin "1") (pinfunction "1_1") (pintype "input"))
      (node (ref "C132") (pin "2") (pinfunction "2_2") (pintype "input"))
      (node (ref "C133") (pin "1") (pinfunction "1_1") (pintype "unspecified"))
      (node (ref "C134") (pin "1") (pinfunction "1_1") (pintype "input"))
      (node (ref "C135") (pin "1") (pinfunction "1_1") (pintype "input"))
      (node (ref "C48") (pin "1") (pinfunction "1_1") (pintype "input"))
      (node (ref "C49") (pin "2") (pinfunction "2_2") (pintype "input"))
      (node (ref "C5") (pin "1") (pinfunction "1_1") (pintype "input"))
      (node (ref "C50") (pin "1") (pinfunction "1_1") (pintype "unspecified"))
      (node (ref "C51") (pin "1") (pinfunction "1_1") (pintype "input"))
      (node (ref "C52") (pin "1") (pinfunction "1_1") (pintype "input"))
      (node (ref "C6") (pin "1") (pinfunction "1_1") (pintype "unspecified"))
      (node (ref "C61") (pin "2") (pinfunction "~_2") (pintype "unspecified"))
      (node (ref "C62") (pin "1") (pinfunction "~_1") (pintype "unspecified"))
      (node (ref "C63") (pin "1") (pinfunction "~_1") (pintype "unspecified"))
      (node (ref "C64") (pin "1") (pinfunction "~_1") (pintype "unspecified"))
      (node (ref "C65") (pin "2") (pinfunction "~_2") (pintype "unspecified"))
      (node (ref "C66") (pin "2") (pinfunction "~_2") (pintype "unspecified"))
      (node (ref "C67") (pin "2") (pinfunction "~_2") (pintype "unspecified"))
      (node (ref "C68") (pin "2") (pinfunction "~_2") (pintype "unspecified"))
      (node (ref "C69") (pin "2") (pinfunction "~_2") (pintype "unspecified"))
      (node (ref "C7") (pin "1") (pinfunction "1_1") (pintype "unspecified"))
      (node (ref "C70") (pin "2") (pinfunction "~_2") (pintype "unspecified"))
      (node (ref "C73") (pin "2") (pinfunction "~_2") (pintype "unspecified"))
      (node (ref "C74") (pin "2") (pinfunction "2_2") (pintype "input"))
      (node (ref "C75") (pin "2") (pinfunction "~_2") (pintype "unspecified"))
      (node (ref "C76") (pin "2") (pinfunction "~_2") (pintype "unspecified"))
      (node (ref "C77") (pin "1") (pinfunction "~_1") (pintype "unspecified"))
      (node (ref "C78") (pin "2") (pinfunction "~_2") (pintype "unspecified"))
      (node (ref "C79") (pin "2") (pinfunction "~_2") (pintype "unspecified"))
      (node (ref "C8") (pin "2") (pinfunction "~_2") (pintype "unspecified"))
      (node (ref "C80") (pin "2") (pinfunction "~_2") (pintype "unspecified"))
      (node (ref "C81") (pin "2") (pinfunction "~_2") (pintype "unspecified"))
      (node (ref "C82") (pin "2") (pinfunction "~_2") (pintype "unspecified"))
      (node (ref "C83") (pin "2") (pinfunction "~_2") (pintype "unspecified"))
      (node (ref "C84") (pin "2") (pinfunction "~_2") (pintype "unspecified"))
      (node (ref "C85") (pin "2") (pinfunction "~_2") (pintype "unspecified"))
      (node (ref "C86") (pin "2") (pinfunction "~_2") (pintype "unspecified"))
      (node (ref "C87") (pin "2") (pinfunction "~_2") (pintype "unspecified"))
      (node (ref "C88") (pin "2") (pinfunction "~_2") (pintype "unspecified"))
      (node (ref "C89") (pin "2") (pinfunction "~_2") (pintype "unspecified"))
      (node (ref "C9") (pin "2") (pinfunction "~_2") (pintype "unspecified"))
      (node (ref "C90") (pin "2") (pinfunction "~_2") (pintype "unspecified"))
      (node (ref "C91") (pin "2") (pinfunction "~_2") (pintype "unspecified"))
      (node (ref "C92") (pin "2") (pinfunction "~_2") (pintype "unspecified"))
      (node (ref "C93") (pin "2") (pinfunction "~_2") (pintype "unspecified"))
      (node (ref "C94") (pin "2") (pinfunction "~_2") (pintype "unspecified"))
      (node (ref "C95") (pin "2") (pinfunction "~_2") (pintype "unspecified"))
      (node (ref "C96") (pin "2") (pinfunction "~_2") (pintype "unspecified"))
      (node (ref "C97") (pin "2") (pinfunction "~_2") (pintype "unspecified"))
      (node (ref "C98") (pin "2") (pinfunction "~_2") (pintype "unspecified"))
      (node (ref "C99") (pin "2") (pinfunction "~_2") (pintype "unspecified"))
      (node (ref "COL_MUX2") (pin "12") (pinfunction "GND_12") (pintype "unspecified"))
      (node (ref "COL_MUX2") (pin "15") (pinfunction "~{E}_15") (pintype "input"))
      (node (ref "COL_MUX2") (pin "3") (pinfunction "I6_3") (pintype "unspecified"))
      (node (ref "D109") (pin "3") (pinfunction "VSS_3") (pintype "unspecified"))
      (node (ref "D110") (pin "2") (pinfunction "DOUT_2") (pintype "output"))
      (node (ref "D111") (pin "2") (pinfunction "DOUT_2") (pintype "output"))
      (node (ref "D111") (pin "3") (pinfunction "VSS_3") (pintype "unspecified"))
      (node (ref "D113") (pin "4") (pinfunction "DIN_4") (pintype "input"))
      (node (ref "D44") (pin "2") (pinfunction "A_2") (pintype "input"))
      (node (ref "D78") (pin "2") (pinfunction "DOUT_2") (pintype "output"))
      (node (ref "D79") (pin "4") (pinfunction "DIN_4") (pintype "input"))
      (node (ref "J1") (pin "2") (pinfunction "2_2") (pintype "unspecified"))
      (node (ref "J1") (pin "3") (pinfunction "3_3") (pintype "unspecified"))
      (node (ref "J12") (pin "2") (pinfunction "2_2") (pintype "unspecified"))
      (node (ref "J13") (pin "2") (pinfunction "2_2") (pintype "unspecified"))
      (node (ref "J14") (pin "1") (pinfunction "1_1") (pintype "unspecified"))
      (node (ref "J14") (pin "3") (pinfunction "3_3") (pintype "unspecified"))
      (node (ref "J15") (pin "1") (pinfunction "1_1") (pintype "unspecified"))
      (node (ref "J15") (pin "3") (pinfunction "3_3") (pintype "unspecified"))
      (node (ref "J16") (pin "1") (pinfunction "1_1") (pintype "unspecified"))
      (node (ref "J16") (pin "4") (pinfunction "4_4") (pintype "unspecified"))
      (node (ref "J17") (pin "1") (pinfunction "1_1") (pintype "unspecified"))
      (node (ref "J17") (pin "4") (pinfunction "4_4") (pintype "unspecified"))
      (node (ref "J18") (pin "1") (pinfunction "1_1") (pintype "unspecified"))
      (node (ref "J18") (pin "4") (pinfunction "4_4") (pintype "unspecified"))
      (node (ref "J19") (pin "1") (pinfunction "1_1") (pintype "unspecified"))
      (node (ref "J19") (pin "4") (pinfunction "4_4") (pintype "unspecified"))
      (node (ref "J8") (pin "1") (pinfunction "1_1") (pintype "unspecified"))
      (node (ref "J8") (pin "4") (pinfunction "4_4") (pintype "unspecified"))
      (node (ref "J9") (pin "1") (pinfunction "1_1") (pintype "unspecified"))
      (node (ref "J9") (pin "4") (pinfunction "4_4") (pintype "unspecified"))
      (node (ref "LEDPWR2") (pin "1") (pinfunction "C_1") (pintype "input"))
      (node (ref "R122") (pin "2") (pinfunction "~_2") (pintype "unspecified"))
      (node (ref "R129") (pin "2") (pinfunction "~_2") (pintype "unspecified"))
      (node (ref "R140") (pin "2") (pinfunction "~_2") (pintype "unspecified"))
      (node (ref "R147") (pin "2") (pinfunction "~_2") (pintype "unspecified"))
      (node (ref "R60") (pin "2") (pinfunction "~_2") (pintype "unspecified"))
      (node (ref "R64") (pin "2") (pinfunction "~_2") (pintype "unspecified"))
      (node (ref "ROW_MUX2") (pin "12") (pinfunction "GND_12") (pintype "unspecified"))
      (node (ref "ROW_MUX2") (pin "15") (pinfunction "~{E}_15") (pintype "input"))
      (node (ref "ROW_MUX2") (pin "16") (pinfunction "I15_16") (pintype "unspecified"))
      (node (ref "ROW_MUX2") (pin "17") (pinfunction "I14_17") (pintype "unspecified"))
      (node (ref "ROW_MUX2") (pin "18") (pinfunction "I13_18") (pintype "unspecified"))
      (node (ref "ROW_MUX2") (pin "19") (pinfunction "I12_19") (pintype "unspecified"))
      (node (ref "ROW_MUX2") (pin "20") (pinfunction "I11_20") (pintype "unspecified"))
      (node (ref "ROW_MUX2") (pin "21") (pinfunction "I10_21") (pintype "unspecified"))
      (node (ref "ROW_MUX2") (pin "22") (pinfunction "I9_22") (pintype "unspecified"))
      (node (ref "ROW_MUX2") (pin "23") (pinfunction "I8_23") (pintype "unspecified"))
      (node (ref "RV4") (pin "3") (pinfunction "3_3") (pintype "unspecified"))
      (node (ref "RV4") (pin "4") (pinfunction "EH_4") (pintype "unspecified"))
      (node (ref "RV4") (pin "5") (pinfunction "EH_5") (pintype "unspecified"))
      (node (ref "RV5") (pin "3") (pinfunction "3_3") (pintype "unspecified"))
      (node (ref "RV5") (pin "4") (pinfunction "EH_4") (pintype "unspecified"))
      (node (ref "RV5") (pin "5") (pinfunction "EH_5") (pintype "unspecified"))
      (node (ref "RV6") (pin "3") (pinfunction "3_3") (pintype "unspecified"))
      (node (ref "RV6") (pin "4") (pinfunction "EH_4") (pintype "unspecified"))
      (node (ref "RV6") (pin "5") (pinfunction "EH_5") (pintype "unspecified"))
      (node (ref "SW49") (pin "1") (pinfunction "1_1") (pintype "unspecified"))
      (node (ref "SW49") (pin "3") (pinfunction "3_3") (pintype "unspecified"))
      (node (ref "Screen2") (pin "1") (pinfunction "Pin_1_1") (pintype "unspecified"))
      (node (ref "U23") (pin "4") (pinfunction "VSS_4") (pintype "unspecified"))
      (node (ref "U24") (pin "G1") (pinfunction "G1_G1") (pintype "unspecified"))
      (node (ref "U24") (pin "G3") (pinfunction "G3_G3") (pintype "unspecified"))
      (node (ref "U25") (pin "5") (pinfunction "GND_5") (pintype "unspecified"))
      (node (ref "U25") (pin "8") (pinfunction "VCC_8") (pintype "unspecified"))
      (node (ref "U26") (pin "2") (pinfunction "2_2") (pintype "unspecified"))
      (node (ref "U27") (pin "1") (pinfunction "1_1") (pintype "unspecified"))
      (node (ref "U28") (pin "2") (pinfunction "2_2") (pintype "unspecified"))
      (node (ref "U29") (pin "2") (pinfunction "2_2") (pintype "unspecified"))
      (node (ref "U30") (pin "2") (pinfunction "2_2") (pintype "unspecified"))
      (node (ref "U31") (pin "1") (pinfunction "1_1") (pintype "unspecified"))
      (node (ref "U32") (pin "2") (pinfunction "2_2") (pintype "unspecified"))
      (node (ref "U33") (pin "2") (pinfunction "2_2") (pintype "unspecified"))
      (node (ref "U34") (pin "4") (pinfunction "VSS_4") (pintype "unspecified"))
      (node (ref "U35") (pin "2") (pinfunction "2_2") (pintype "unspecified"))
      (node (ref "U36") (pin "1") (pinfunction "1_1") (pintype "unspecified"))
      (node (ref "U37") (pin "2") (pinfunction "2_2") (pintype "unspecified"))
      (node (ref "U38") (pin "2") (pinfunction "2_2") (pintype "unspecified"))
      (node (ref "U39") (pin "4") (pinfunction "VSS_4") (pintype "unspecified"))
      (node (ref "U8") (pin "1") (pinfunction "#1OE_1") (pintype "unspecified"))
      (node (ref "U8") (pin "10") (pinfunction "#3OE_10") (pintype "unspecified"))
      (node (ref "U8") (pin "11") (pinfunction "4Y_11") (pintype "unspecified"))
      (node (ref "U8") (pin "12") (pinfunction "4A_12") (pintype "unspecified"))
      (node (ref "U8") (pin "13") (pinfunction "#4OE_13") (pintype "unspecified"))
      (node (ref "U8") (pin "4") (pinfunction "#2OE_4") (pintype "unspecified"))
      (node (ref "U8") (pin "7") (pinfunction "GND_7") (pintype "unspecified"))
      (node (ref "U8") (pin "8") (pinfunction "3Y_8") (pintype "unspecified"))
      (node (ref "U8") (pin "9") (pinfunction "3A_9") (pintype "unspecified"))
    )
    (net (code "26") (name "LED") (class "Default")
      (node (ref "U24") (pin "6") (pinfunction "6_6") (pintype "bidirectional"))
      (node (ref "U8") (pin "2") (pinfunction "1A_2") (pintype "unspecified"))
    )
    (net (code "27") (name "LEDCNTRL") (class "Default")
      (node (ref "D61") (pin "4") (pinfunction "DIN_4") (pintype "input"))
      (node (ref "R20") (pin "2") (pinfunction "~_2") (pintype "unspecified"))
    )
    (net (code "28") (name "MAIN") (class "Default")
      (node (ref "COL_MUX2") (pin "18") (pinfunction "I13_18") (pintype "unspecified"))
      (node (ref "RV6") (pin "2") (pinfunction "2_2") (pintype "unspecified"))
    )
    (net (code "29") (name "MIDI_OUT") (class "Default")
      (node (ref "R86") (pin "2") (pinfunction "~_2") (pintype "unspecified"))
      (node (ref "R94") (pin "2") (pinfunction "~_2") (pintype "unspecified"))
      (node (ref "U8") (pin "6") (pinfunction "2Y_6") (pintype "unspecified"))
    )
    (net (code "30") (name "MIDI_RX") (class "Default")
      (node (ref "R88") (pin "2") (pinfunction "~_2") (pintype "unspecified"))
      (node (ref "U24") (pin "0") (pinfunction "0_0") (pintype "bidirectional"))
      (node (ref "U25") (pin "6") (pinfunction "VO2_6") (pintype "unspecified"))
    )
    (net (code "31") (name "MIDI_TX") (class "Default")
      (node (ref "U24") (pin "1") (pinfunction "1_1") (pintype "bidirectional"))
      (node (ref "U8") (pin "5") (pinfunction "2A_5") (pintype "unspecified"))
    )
    (net (code "32") (name "MRC") (class "Default")
      (node (ref "R95") (pin "2") (pinfunction "~_2") (pintype "unspecified"))
      (node (ref "U24") (pin "7") (pinfunction "7_7") (pintype "bidirectional"))
    )
    (net (code "33") (name "MRR") (class "Default")
      (node (ref "ROW_MUX2") (pin "1") (pinfunction "COM_1") (pintype "unspecified"))
      (node (ref "U24") (pin "22") (pinfunction "22_22") (pintype "bidirectional"))
    )
    (net (code "34") (name "MUXC1") (class "Default")
      (node (ref "COL_MUX2") (pin "10") (pinfunction "S0_10") (pintype "input"))
      (node (ref "U24") (pin "8") (pinfunction "8_8") (pintype "bidirectional"))
    )
    (net (code "35") (name "MUXC2") (class "Default")
      (node (ref "COL_MUX2") (pin "11") (pinfunction "S1_11") (pintype "input"))
      (node (ref "U24") (pin "9") (pinfunction "9_9") (pintype "bidirectional"))
    )
    (net (code "36") (name "MUXC3") (class "Default")
      (node (ref "COL_MUX2") (pin "14") (pinfunction "S2_14") (pintype "input"))
      (node (ref "U24") (pin "10") (pinfunction "10_10") (pintype "bidirectional"))
    )
    (net (code "37") (name "MUXC4") (class "Default")
      (node (ref "COL_MUX2") (pin "13") (pinfunction "S3_13") (pintype "input"))
      (node (ref "U24") (pin "11") (pinfunction "11_11") (pintype "bidirectional"))
    )
    (net (code "38") (name "MUXR1") (class "Default")
      (node (ref "ROW_MUX2") (pin "10") (pinfunction "S0_10") (pintype "input"))
      (node (ref "U24") (pin "2") (pinfunction "2_2") (pintype "bidirectional"))
    )
    (net (code "39") (name "MUXR2") (class "Default")
      (node (ref "ROW_MUX2") (pin "11") (pinfunction "S1_11") (pintype "input"))
      (node (ref "U24") (pin "3") (pinfunction "3_3") (pintype "bidirectional"))
    )
    (net (code "40") (name "MUXR3") (class "Default")
      (node (ref "ROW_MUX2") (pin "14") (pinfunction "S2_14") (pintype "input"))
      (node (ref "U24") (pin "4") (pinfunction "4_4") (pintype "bidirectional"))
    )
    (net (code "41") (name "MUXR4") (class "Default")
      (node (ref "ROW_MUX2") (pin "13") (pinfunction "S3_13") (pintype "input"))
      (node (ref "U24") (pin "5") (pinfunction "5_5") (pintype "bidirectional"))
    )
    (net (code "42") (name "Net-(C71-~-Pad1)") (class "Default")
      (node (ref "C71") (pin "1") (pinfunction "~_1") (pintype "unspecified"))
      (node (ref "C72") (pin "1") (pinfunction "1_1") (pintype "input"))
      (node (ref "R89") (pin "1") (pinfunction "~_1") (pintype "unspecified"))
      (node (ref "U24") (pin "G2") (pinfunction "G2_G2") (pintype "unspecified"))
    )
    (net (code "43") (name "Net-(C71-~-Pad2)") (class "Default")
      (node (ref "C71") (pin "2") (pinfunction "~_2") (pintype "unspecified"))
      (node (ref "C72") (pin "2") (pinfunction "2_2") (pintype "input"))
      (node (ref "R90") (pin "1") (pinfunction "~_1") (pintype "unspecified"))
      (node (ref "U24") (pin "3.3V_1") (pinfunction "3.3V_1_3.3V_1") (pintype "unspecified"))
    )
    (net (code "44") (name "Net-(C122-Pad1)") (class "Default")
      (node (ref "C122") (pin "1") (pinfunction "1_1") (pintype "unspecified"))
      (node (ref "R114") (pin "2") (pinfunction "2_2") (pintype "input"))
    )
    (net (code "45") (name "Net-(C123-Pad1)") (class "Default")
      (node (ref "C123") (pin "1") (pinfunction "1_1") (pintype "unspecified"))
      (node (ref "R119") (pin "2") (pinfunction "2_2") (pintype "input"))
    )
    (net (code "46") (name "Net-(C129-Pad1)") (class "Default")
      (node (ref "C129") (pin "1") (pinfunction "1_1") (pintype "unspecified"))
      (node (ref "R130") (pin "2") (pinfunction "2_2") (pintype "input"))
    )
    (net (code "47") (name "Net-(C130-Pad1)") (class "Default")
      (node (ref "C130") (pin "1") (pinfunction "1_1") (pintype "unspecified"))
      (node (ref "R137") (pin "2") (pinfunction "2_2") (pintype "input"))
    )
    (net (code "48") (name "Net-(C136-Pad1)") (class "Default")
      (node (ref "C136") (pin "1") (pinfunction "1_1") (pintype "unspecified"))
      (node (ref "R148") (pin "2") (pinfunction "2_2") (pintype "input"))
    )
    (net (code "49") (name "Net-(C137-Pad1)") (class "Default")
      (node (ref "C137") (pin "1") (pinfunction "1_1") (pintype "unspecified"))
      (node (ref "R155") (pin "2") (pinfunction "2_2") (pintype "input"))
    )
    (net (code "50") (name "Net-(COL_MUX2-COM)") (class "Default")
      (node (ref "C77") (pin "2") (pinfunction "~_2") (pintype "unspecified"))
      (node (ref "COL_MUX2") (pin "1") (pinfunction "COM_1") (pintype "unspecified"))
      (node (ref "R95") (pin "1") (pinfunction "~_1") (pintype "unspecified"))
    )
    (net (code "51") (name "Net-(D49-A)") (class "Default")
      (node (ref "D49") (pin "2") (pinfunction "A_2") (pintype "unspecified"))
      (node (ref "R62") (pin "1") (pinfunction "~_1") (pintype "unspecified"))
    )
    (net (code "52") (name "Net-(D50-A)") (class "Default")
      (node (ref "D50") (pin "2") (pinfunction "A_2") (pintype "unspecified"))
      (node (ref "R66") (pin "1") (pinfunction "~_1") (pintype "unspecified"))
    )
    (net (code "53") (name "Net-(D50-K)") (class "Default")
      (node (ref "D50") (pin "1") (pinfunction "K_1") (pintype "unspecified"))
      (node (ref "R67") (pin "2") (pinfunction "~_2") (pintype "unspecified"))
      (node (ref "U23") (pin "6") (pinfunction "INB-_6") (pintype "unspecified"))
    )
    (net (code "54") (name "Net-(D61-DOUT)") (class "Default")
      (node (ref "D61") (pin "2") (pinfunction "DOUT_2") (pintype "output"))
      (node (ref "D62") (pin "4") (pinfunction "DIN_4") (pintype "input"))
    )
    (net (code "55") (name "Net-(D61-VSS)") (class "Default")
      (node (ref "C78") (pin "1") (pinfunction "~_1") (pintype "unspecified"))
      (node (ref "D61") (pin "3") (pinfunction "VSS_3") (pintype "unspecified"))
      (node (ref "D62") (pin "1") (pinfunction "VDD_1") (pintype "unspecified"))
    )
    (net (code "56") (name "Net-(D62-DOUT)") (class "Default")
      (node (ref "C79") (pin "1") (pinfunction "~_1") (pintype "unspecified"))
      (node (ref "D62") (pin "2") (pinfunction "DOUT_2") (pintype "output"))
      (node (ref "D62") (pin "3") (pinfunction "VSS_3") (pintype "unspecified"))
      (node (ref "D63") (pin "1") (pinfunction "VDD_1") (pintype "unspecified"))
      (node (ref "D63") (pin "4") (pinfunction "DIN_4") (pintype "input"))
    )
    (net (code "57") (name "Net-(D63-DOUT)") (class "Default")
      (node (ref "D63") (pin "2") (pinfunction "DOUT_2") (pintype "output"))
      (node (ref "D64") (pin "4") (pinfunction "DIN_4") (pintype "input"))
    )
    (net (code "58") (name "Net-(D63-VSS)") (class "Default")
      (node (ref "C80") (pin "1") (pinfunction "~_1") (pintype "unspecified"))
      (node (ref "D63") (pin "3") (pinfunction "VSS_3") (pintype "unspecified"))
      (node (ref "D64") (pin "1") (pinfunction "VDD_1") (pintype "unspecified"))
    )
    (net (code "59") (name "Net-(D64-DOUT)") (class "Default")
      (node (ref "D64") (pin "2") (pinfunction "DOUT_2") (pintype "output"))
      (node (ref "D65") (pin "4") (pinfunction "DIN_4") (pintype "input"))
    )
    (net (code "60") (name "Net-(D64-VSS)") (class "Default")
      (node (ref "C81") (pin "1") (pinfunction "~_1") (pintype "unspecified"))
      (node (ref "D64") (pin "3") (pinfunction "VSS_3") (pintype "unspecified"))
      (node (ref "D65") (pin "1") (pinfunction "VDD_1") (pintype "unspecified"))
    )
    (net (code "61") (name "Net-(D65-DOUT)") (class "Default")
      (node (ref "D65") (pin "2") (pinfunction "DOUT_2") (pintype "output"))
      (node (ref "D66") (pin "4") (pinfunction "DIN_4") (pintype "input"))
    )
    (net (code "62") (name "Net-(D65-VSS)") (class "Default")
      (node (ref "C82") (pin "1") (pinfunction "~_1") (pintype "unspecified"))
      (node (ref "D65") (pin "3") (pinfunction "VSS_3") (pintype "unspecified"))
      (node (ref "D66") (pin "1") (pinfunction "VDD_1") (pintype "unspecified"))
    )
    (net (code "63") (name "Net-(D66-DOUT)") (class "Default")
      (node (ref "D66") (pin "2") (pinfunction "DOUT_2") (pintype "output"))
      (node (ref "D67") (pin "4") (pinfunction "DIN_4") (pintype "input"))
    )
    (net (code "64") (name "Net-(D66-VSS)") (class "Default")
      (node (ref "C65") (pin "1") (pinfunction "~_1") (pintype "unspecified"))
      (node (ref "D66") (pin "3") (pinfunction "VSS_3") (pintype "unspecified"))
      (node (ref "D67") (pin "1") (pinfunction "VDD_1") (pintype "unspecified"))
    )
    (net (code "65") (name "Net-(D67-DOUT)") (class "Default")
      (node (ref "D67") (pin "2") (pinfunction "DOUT_2") (pintype "output"))
      (node (ref "D68") (pin "4") (pinfunction "DIN_4") (pintype "input"))
    )
    (net (code "66") (name "Net-(D67-VSS)") (class "Default")
      (node (ref "C83") (pin "1") (pinfunction "~_1") (pintype "unspecified"))
      (node (ref "D67") (pin "3") (pinfunction "VSS_3") (pintype "unspecified"))
      (node (ref "D68") (pin "1") (pinfunction "VDD_1") (pintype "unspecified"))
    )
    (net (code "67") (name "Net-(D68-DOUT)") (class "Default")
      (node (ref "D68") (pin "2") (pinfunction "DOUT_2") (pintype "output"))
      (node (ref "D69") (pin "4") (pinfunction "DIN_4") (pintype "input"))
    )
    (net (code "68") (name "Net-(D68-VSS)") (class "Default")
      (node (ref "C84") (pin "1") (pinfunction "~_1") (pintype "unspecified"))
      (node (ref "D68") (pin "3") (pinfunction "VSS_3") (pintype "unspecified"))
      (node (ref "D69") (pin "1") (pinfunction "VDD_1") (pintype "unspecified"))
    )
    (net (code "69") (name "Net-(D69-DOUT)") (class "Default")
      (node (ref "D69") (pin "2") (pinfunction "DOUT_2") (pintype "output"))
      (node (ref "D70") (pin "4") (pinfunction "DIN_4") (pintype "input"))
    )
    (net (code "70") (name "Net-(D69-VSS)") (class "Default")
      (node (ref "C85") (pin "1") (pinfunction "~_1") (pintype "unspecified"))
      (node (ref "D69") (pin "3") (pinfunction "VSS_3") (pintype "unspecified"))
      (node (ref "D70") (pin "1") (pinfunction "VDD_1") (pintype "unspecified"))
    )
    (net (code "71") (name "Net-(D70-DOUT)") (class "Default")
      (node (ref "D70") (pin "2") (pinfunction "DOUT_2") (pintype "output"))
      (node (ref "D71") (pin "4") (pinfunction "DIN_4") (pintype "input"))
    )
    (net (code "72") (name "Net-(D70-VSS)") (class "Default")
      (node (ref "C86") (pin "1") (pinfunction "~_1") (pintype "unspecified"))
      (node (ref "D70") (pin "3") (pinfunction "VSS_3") (pintype "unspecified"))
      (node (ref "D71") (pin "1") (pinfunction "VDD_1") (pintype "unspecified"))
    )
    (net (code "73") (name "Net-(D71-DOUT)") (class "Default")
      (node (ref "D71") (pin "2") (pinfunction "DOUT_2") (pintype "output"))
      (node (ref "D72") (pin "4") (pinfunction "DIN_4") (pintype "input"))
    )
    (net (code "74") (name "Net-(D71-VSS)") (class "Default")
      (node (ref "C87") (pin "1") (pinfunction "~_1") (pintype "unspecified"))
      (node (ref "D71") (pin "3") (pinfunction "VSS_3") (pintype "unspecified"))
      (node (ref "D72") (pin "1") (pinfunction "VDD_1") (pintype "unspecified"))
    )
    (net (code "75") (name "Net-(D72-DOUT)") (class "Default")
      (node (ref "D72") (pin "2") (pinfunction "DOUT_2") (pintype "output"))
      (node (ref "D73") (pin "4") (pinfunction "DIN_4") (pintype "input"))
    )
    (net (code "76") (name "Net-(D72-VSS)") (class "Default")
      (node (ref "C66") (pin "1") (pinfunction "~_1") (pintype "unspecified"))
      (node (ref "D72") (pin "3") (pinfunction "VSS_3") (pintype "unspecified"))
      (node (ref "D73") (pin "1") (pinfunction "VDD_1") (pintype "unspecified"))
    )
    (net (code "77") (name "Net-(D73-DOUT)") (class "Default")
      (node (ref "D73") (pin "2") (pinfunction "DOUT_2") (pintype "output"))
      (node (ref "D74") (pin "4") (pinfunction "DIN_4") (pintype "input"))
    )
    (net (code "78") (name "Net-(D73-VSS)") (class "Default")
      (node (ref "C88") (pin "1") (pinfunction "~_1") (pintype "unspecified"))
      (node (ref "D73") (pin "3") (pinfunction "VSS_3") (pintype "unspecified"))
      (node (ref "D74") (pin "1") (pinfunction "VDD_1") (pintype "unspecified"))
    )
    (net (code "79") (name "Net-(D74-DOUT)") (class "Default")
      (node (ref "D74") (pin "2") (pinfunction "DOUT_2") (pintype "output"))
      (node (ref "D75") (pin "4") (pinfunction "DIN_4") (pintype "input"))
    )
    (net (code "80") (name "Net-(D74-VSS)") (class "Default")
      (node (ref "C89") (pin "1") (pinfunction "~_1") (pintype "unspecified"))
      (node (ref "D74") (pin "3") (pinfunction "VSS_3") (pintype "unspecified"))
      (node (ref "D75") (pin "1") (pinfunction "VDD_1") (pintype "unspecified"))
    )
    (net (code "81") (name "Net-(D75-DOUT)") (class "Default")
      (node (ref "D75") (pin "2") (pinfunction "DOUT_2") (pintype "output"))
      (node (ref "D76") (pin "4") (pinfunction "DIN_4") (pintype "input"))
    )
    (net (code "82") (name "Net-(D75-VSS)") (class "Default")
      (node (ref "C90") (pin "1") (pinfunction "~_1") (pintype "unspecified"))
      (node (ref "D75") (pin "3") (pinfunction "VSS_3") (pintype "unspecified"))
      (node (ref "D76") (pin "1") (pinfunction "VDD_1") (pintype "unspecified"))
    )
    (net (code "83") (name "Net-(D76-DOUT)") (class "Default")
      (node (ref "D76") (pin "2") (pinfunction "DOUT_2") (pintype "output"))
      (node (ref "D77") (pin "4") (pinfunction "DIN_4") (pintype "input"))
    )
    (net (code "84") (name "Net-(D76-VSS)") (class "Default")
      (node (ref "C91") (pin "1") (pinfunction "~_1") (pintype "unspecified"))
      (node (ref "D76") (pin "3") (pinfunction "VSS_3") (pintype "unspecified"))
      (node (ref "D77") (pin "1") (pinfunction "VDD_1") (pintype "unspecified"))
    )
    (net (code "85") (name "Net-(D77-DOUT)") (class "Default")
      (node (ref "D77") (pin "2") (pinfunction "DOUT_2") (pintype "output"))
      (node (ref "D78") (pin "4") (pinfunction "DIN_4") (pintype "input"))
    )
    (net (code "86") (name "Net-(D77-VSS)") (class "Default")
      (node (ref "C92") (pin "1") (pinfunction "~_1") (pintype "unspecified"))
      (node (ref "D77") (pin "3") (pinfunction "VSS_3") (pintype "unspecified"))
      (node (ref "D78") (pin "1") (pinfunction "VDD_1") (pintype "unspecified"))
    )
    (net (code "87") (name "Net-(D78-VSS)") (class "Default")
      (node (ref "C67") (pin "1") (pinfunction "~_1") (pintype "unspecified"))
      (node (ref "D78") (pin "3") (pinfunction "VSS_3") (pintype "unspecified"))
      (node (ref "D79") (pin "1") (pinfunction "VDD_1") (pintype "unspecified"))
    )
    (net (code "88") (name "Net-(D79-DOUT)") (class "Default")
      (node (ref "D79") (pin "2") (pinfunction "DOUT_2") (pintype "output"))
      (node (ref "D80") (pin "4") (pinfunction "DIN_4") (pintype "input"))
    )
    (net (code "89") (name "Net-(D79-VSS)") (class "Default")
      (node (ref "C93") (pin "1") (pinfunction "~_1") (pintype "unspecified"))
      (node (ref "D79") (pin "3") (pinfunction "VSS_3") (pintype "unspecified"))
      (node (ref "D80") (pin "1") (pinfunction "VDD_1") (pintype "unspecified"))
    )
    (net (code "90") (name "Net-(D80-DOUT)") (class "Default")
      (node (ref "D80") (pin "2") (pinfunction "DOUT_2") (pintype "output"))
      (node (ref "D81") (pin "4") (pinfunction "DIN_4") (pintype "input"))
    )
    (net (code "91") (name "Net-(D80-VSS)") (class "Default")
      (node (ref "C94") (pin "1") (pinfunction "~_1") (pintype "unspecified"))
      (node (ref "D80") (pin "3") (pinfunction "VSS_3") (pintype "unspecified"))
      (node (ref "D81") (pin "1") (pinfunction "VDD_1") (pintype "unspecified"))
    )
    (net (code "92") (name "Net-(D81-DOUT)") (class "Default")
      (node (ref "D81") (pin "2") (pinfunction "DOUT_2") (pintype "output"))
      (node (ref "D82") (pin "4") (pinfunction "DIN_4") (pintype "input"))
    )
    (net (code "93") (name "Net-(D81-VSS)") (class "Default")
      (node (ref "C95") (pin "1") (pinfunction "~_1") (pintype "unspecified"))
      (node (ref "D81") (pin "3") (pinfunction "VSS_3") (pintype "unspecified"))
      (node (ref "D82") (pin "1") (pinfunction "VDD_1") (pintype "unspecified"))
    )
    (net (code "94") (name "Net-(D82-DOUT)") (class "Default")
      (node (ref "D82") (pin "2") (pinfunction "DOUT_2") (pintype "output"))
      (node (ref "D83") (pin "4") (pinfunction "DIN_4") (pintype "input"))
    )
    (net (code "95") (name "Net-(D82-VSS)") (class "Default")
      (node (ref "C96") (pin "1") (pinfunction "~_1") (pintype "unspecified"))
      (node (ref "D82") (pin "3") (pinfunction "VSS_3") (pintype "unspecified"))
      (node (ref "D83") (pin "1") (pinfunction "VDD_1") (pintype "unspecified"))
    )
    (net (code "96") (name "Net-(D83-DOUT)") (class "Default")
      (node (ref "D83") (pin "2") (pinfunction "DOUT_2") (pintype "output"))
      (node (ref "D84") (pin "4") (pinfunction "DIN_4") (pintype "input"))
    )
    (net (code "97") (name "Net-(D83-VSS)") (class "Default")
      (node (ref "C97") (pin "1") (pinfunction "~_1") (pintype "unspecified"))
      (node (ref "D83") (pin "3") (pinfunction "VSS_3") (pintype "unspecified"))
      (node (ref "D84") (pin "1") (pinfunction "VDD_1") (pintype "unspecified"))
    )
    (net (code "98") (name "Net-(D84-DOUT)") (class "Default")
      (node (ref "D84") (pin "2") (pinfunction "DOUT_2") (pintype "output"))
      (node (ref "D85") (pin "4") (pinfunction "DIN_4") (pintype "input"))
    )
    (net (code "99") (name "Net-(D84-VSS)") (class "Default")
      (node (ref "C68") (pin "1") (pinfunction "~_1") (pintype "unspecified"))
      (node (ref "D84") (pin "3") (pinfunction "VSS_3") (pintype "unspecified"))
      (node (ref "D85") (pin "1") (pinfunction "VDD_1") (pintype "unspecified"))
    )
    (net (code "100") (name "Net-(D85-DOUT)") (class "Default")
      (node (ref "D85") (pin "2") (pinfunction "DOUT_2") (pintype "output"))
      (node (ref "D86") (pin "4") (pinfunction "DIN_4") (pintype "input"))
    )
    (net (code "101") (name "Net-(D85-VSS)") (class "Default")
      (node (ref "C98") (pin "1") (pinfunction "~_1") (pintype "unspecified"))
      (node (ref "D85") (pin "3") (pinfunction "VSS_3") (pintype "unspecified"))
      (node (ref "D86") (pin "1") (pinfunction "VDD_1") (pintype "unspecified"))
    )
    (net (code "102") (name "Net-(D86-DOUT)") (class "Default")
      (node (ref "D86") (pin "2") (pinfunction "DOUT_2") (pintype "output"))
      (node (ref "D87") (pin "4") (pinfunction "DIN_4") (pintype "input"))
    )
    (net (code "103") (name "Net-(D86-VSS)") (class "Default")
      (node (ref "C99") (pin "1") (pinfunction "~_1") (pintype "unspecified"))
      (node (ref "D86") (pin "3") (pinfunction "VSS_3") (pintype "unspecified"))
      (node (ref "D87") (pin "1") (pinfunction "VDD_1") (pintype "unspecified"))
    )
    (net (code "104") (name "Net-(D87-DOUT)") (class "Default")
      (node (ref "D87") (pin "2") (pinfunction "DOUT_2") (pintype "output"))
      (node (ref "D88") (pin "4") (pinfunction "DIN_4") (pintype "input"))
    )
    (net (code "105") (name "Net-(D87-VSS)") (class "Default")
      (node (ref "C100") (pin "1") (pinfunction "~_1") (pintype "unspecified"))
      (node (ref "D87") (pin "3") (pinfunction "VSS_3") (pintype "unspecified"))
      (node (ref "D88") (pin "1") (pinfunction "VDD_1") (pintype "unspecified"))
    )
    (net (code "106") (name "Net-(D88-DOUT)") (class "Default")
      (node (ref "D88") (pin "2") (pinfunction "DOUT_2") (pintype "output"))
      (node (ref "D89") (pin "4") (pinfunction "DIN_4") (pintype "input"))
    )
    (net (code "107") (name "Net-(D88-VSS)") (class "Default")
      (node (ref "C101") (pin "1") (pinfunction "~_1") (pintype "unspecified"))
      (node (ref "D88") (pin "3") (pinfunction "VSS_3") (pintype "unspecified"))
      (node (ref "D89") (pin "1") (pinfunction "VDD_1") (pintype "unspecified"))
    )
    (net (code "108") (name "Net-(D89-DOUT)") (class "Default")
      (node (ref "D89") (pin "2") (pinfunction "DOUT_2") (pintype "output"))
      (node (ref "D90") (pin "4") (pinfunction "DIN_4") (pintype "input"))
    )
    (net (code "109") (name "Net-(D89-VSS)") (class "Default")
      (node (ref "C102") (pin "1") (pinfunction "~_1") (pintype "unspecified"))
      (node (ref "D89") (pin "3") (pinfunction "VSS_3") (pintype "unspecified"))
      (node (ref "D90") (pin "1") (pinfunction "VDD_1") (pintype "unspecified"))
    )
    (net (code "110") (name "Net-(D90-DOUT)") (class "Default")
      (node (ref "D90") (pin "2") (pinfunction "DOUT_2") (pintype "output"))
      (node (ref "D91") (pin "4") (pinfunction "DIN_4") (pintype "input"))
    )
    (net (code "111") (name "Net-(D90-VSS)") (class "Default")
      (node (ref "C69") (pin "1") (pinfunction "~_1") (pintype "unspecified"))
      (node (ref "D90") (pin "3") (pinfunction "VSS_3") (pintype "unspecified"))
      (node (ref "D91") (pin "1") (pinfunction "VDD_1") (pintype "unspecified"))
    )
    (net (code "112") (name "Net-(D91-DOUT)") (class "Default")
      (node (ref "D91") (pin "2") (pinfunction "DOUT_2") (pintype "output"))
      (node (ref "D92") (pin "4") (pinfunction "DIN_4") (pintype "input"))
    )
    (net (code "113") (name "Net-(D91-VSS)") (class "Default")
      (node (ref "C103") (pin "1") (pinfunction "~_1") (pintype "unspecified"))
      (node (ref "D91") (pin "3") (pinfunction "VSS_3") (pintype "unspecified"))
      (node (ref "D92") (pin "1") (pinfunction "VDD_1") (pintype "unspecified"))
    )
    (net (code "114") (name "Net-(D92-DOUT)") (class "Default")
      (node (ref "D92") (pin "2") (pinfunction "DOUT_2") (pintype "output"))
      (node (ref "D93") (pin "4") (pinfunction "DIN_4") (pintype "input"))
    )
    (net (code "115") (name "Net-(D92-VSS)") (class "Default")
      (node (ref "C104") (pin "1") (pinfunction "~_1") (pintype "unspecified"))
      (node (ref "D92") (pin "3") (pinfunction "VSS_3") (pintype "unspecified"))
      (node (ref "D93") (pin "1") (pinfunction "VDD_1") (pintype "unspecified"))
    )
    (net (code "116") (name "Net-(D93-DOUT)") (class "Default")
      (node (ref "D93") (pin "2") (pinfunction "DOUT_2") (pintype "output"))
      (node (ref "D94") (pin "4") (pinfunction "DIN_4") (pintype "input"))
    )
    (net (code "117") (name "Net-(D93-VSS)") (class "Default")
      (node (ref "C105") (pin "1") (pinfunction "~_1") (pintype "unspecified"))
      (node (ref "D93") (pin "3") (pinfunction "VSS_3") (pintype "unspecified"))
      (node (ref "D94") (pin "1") (pinfunction "VDD_1") (pintype "unspecified"))
    )
    (net (code "118") (name "Net-(D94-DOUT)") (class "Default")
      (node (ref "D94") (pin "2") (pinfunction "DOUT_2") (pintype "output"))
      (node (ref "D95") (pin "4") (pinfunction "DIN_4") (pintype "input"))
    )
    (net (code "119") (name "Net-(D94-VSS)") (class "Default")
      (node (ref "C106") (pin "1") (pinfunction "~_1") (pintype "unspecified"))
      (node (ref "D94") (pin "3") (pinfunction "VSS_3") (pintype "unspecified"))
      (node (ref "D95") (pin "1") (pinfunction "VDD_1") (pintype "unspecified"))
    )
    (net (code "120") (name "Net-(D95-DOUT)") (class "Default")
      (node (ref "D95") (pin "2") (pinfunction "DOUT_2") (pintype "output"))
      (node (ref "D96") (pin "4") (pinfunction "DIN_4") (pintype "input"))
    )
    (net (code "121") (name "Net-(D95-VSS)") (class "Default")
      (node (ref "C107") (pin "1") (pinfunction "~_1") (pintype "unspecified"))
      (node (ref "D95") (pin "3") (pinfunction "VSS_3") (pintype "unspecified"))
      (node (ref "D96") (pin "1") (pinfunction "VDD_1") (pintype "unspecified"))
    )
    (net (code "122") (name "Net-(D96-DOUT)") (class "Default")
      (node (ref "D96") (pin "2") (pinfunction "DOUT_2") (pintype "output"))
      (node (ref "D97") (pin "4") (pinfunction "DIN_4") (pintype "input"))
    )
    (net (code "123") (name "Net-(D96-VSS)") (class "Default")
      (node (ref "C70") (pin "1") (pinfunction "~_1") (pintype "unspecified"))
      (node (ref "D96") (pin "3") (pinfunction "VSS_3") (pintype "unspecified"))
      (node (ref "D97") (pin "1") (pinfunction "VDD_1") (pintype "unspecified"))
    )
    (net (code "124") (name "Net-(D97-DOUT)") (class "Default")
      (node (ref "D97") (pin "2") (pinfunction "DOUT_2") (pintype "output"))
      (node (ref "D98") (pin "4") (pinfunction "DIN_4") (pintype "input"))
    )
    (net (code "125") (name "Net-(D97-VSS)") (class "Default")
      (node (ref "C108") (pin "1") (pinfunction "~_1") (pintype "unspecified"))
      (node (ref "D97") (pin "3") (pinfunction "VSS_3") (pintype "unspecified"))
      (node (ref "D98") (pin "1") (pinfunction "VDD_1") (pintype "unspecified"))
    )
    (net (code "126") (name "Net-(D98-DOUT)") (class "Default")
      (node (ref "D98") (pin "2") (pinfunction "DOUT_2") (pintype "output"))
      (node (ref "D99") (pin "4") (pinfunction "DIN_4") (pintype "input"))
    )
    (net (code "127") (name "Net-(D98-VSS)") (class "Default")
      (node (ref "C109") (pin "1") (pinfunction "~_1") (pintype "unspecified"))
      (node (ref "D98") (pin "3") (pinfunction "VSS_3") (pintype "unspecified"))
      (node (ref "D99") (pin "1") (pinfunction "VDD_1") (pintype "unspecified"))
    )
    (net (code "128") (name "Net-(D100-DIN)") (class "Default")
      (node (ref "D100") (pin "4") (pinfunction "DIN_4") (pintype "input"))
      (node (ref "D99") (pin "2") (pinfunction "DOUT_2") (pintype "output"))
    )
    (net (code "129") (name "Net-(D100-DOUT)") (class "Default")
      (node (ref "D100") (pin "2") (pinfunction "DOUT_2") (pintype "output"))
      (node (ref "D101") (pin "4") (pinfunction "DIN_4") (pintype "input"))
    )
    (net (code "130") (name "Net-(D100-VDD)") (class "Default")
      (node (ref "C110") (pin "1") (pinfunction "~_1") (pintype "unspecified"))
      (node (ref "D100") (pin "1") (pinfunction "VDD_1") (pintype "unspecified"))
      (node (ref "D99") (pin "3") (pinfunction "VSS_3") (pintype "unspecified"))
    )
    (net (code "131") (name "Net-(D100-VSS)") (class "Default")
      (node (ref "C111") (pin "1") (pinfunction "~_1") (pintype "unspecified"))
      (node (ref "D100") (pin "3") (pinfunction "VSS_3") (pintype "unspecified"))
      (node (ref "D101") (pin "1") (pinfunction "VDD_1") (pintype "unspecified"))
    )
    (net (code "132") (name "Net-(D101-DOUT)") (class "Default")
      (node (ref "D101") (pin "2") (pinfunction "DOUT_2") (pintype "output"))
      (node (ref "D102") (pin "4") (pinfunction "DIN_4") (pintype "input"))
    )
    (net (code "133") (name "Net-(D101-VSS)") (class "Default")
      (node (ref "C112") (pin "1") (pinfunction "~_1") (pintype "unspecified"))
      (node (ref "D101") (pin "3") (pinfunction "VSS_3") (pintype "unspecified"))
      (node (ref "D102") (pin "1") (pinfunction "VDD_1") (pintype "unspecified"))
    )
    (net (code "134") (name "Net-(D103-A)") (class "Default")
      (node (ref "D103") (pin "2") (pinfunction "A_2") (pintype "unspecified"))
      (node (ref "R87") (pin "1") (pinfunction "~_1") (pintype "unspecified"))
      (node (ref "U25") (pin "3") (pinfunction "C2_3") (pintype "unspecified"))
    )
    (net (code "135") (name "Net-(D103-K)") (class "Default")
      (node (ref "D103") (pin "1") (pinfunction "K_1") (pintype "unspecified"))
      (node (ref "J12") (pin "4") (pinfunction "4_4") (pintype "unspecified"))
      (node (ref "J14") (pin "2") (pinfunction "2_2") (pintype "unspecified"))
      (node (ref "U25") (pin "2") (pinfunction "C1_2") (pintype "unspecified"))
    )
    (net (code "136") (name "Net-(D104-DOUT)") (class "Default")
      (node (ref "D104") (pin "2") (pinfunction "DOUT_2") (pintype "output"))
      (node (ref "D105") (pin "4") (pinfunction "DIN_4") (pintype "input"))
    )
    (net (code "137") (name "Net-(D104-VSS)") (class "Default")
      (node (ref "C113") (pin "1") (pinfunction "~_1") (pintype "unspecified"))
      (node (ref "D104") (pin "3") (pinfunction "VSS_3") (pintype "unspecified"))
      (node (ref "D105") (pin "1") (pinfunction "VDD_1") (pintype "unspecified"))
    )
    (net (code "138") (name "Net-(D105-DOUT)") (class "Default")
      (node (ref "D105") (pin "2") (pinfunction "DOUT_2") (pintype "output"))
      (node (ref "D106") (pin "4") (pinfunction "DIN_4") (pintype "input"))
    )
    (net (code "139") (name "Net-(D105-VSS)") (class "Default")
      (node (ref "C114") (pin "1") (pinfunction "~_1") (pintype "unspecified"))
      (node (ref "D105") (pin "3") (pinfunction "VSS_3") (pintype "unspecified"))
      (node (ref "D106") (pin "1") (pinfunction "VDD_1") (pintype "unspecified"))
    )
    (net (code "140") (name "Net-(D106-DOUT)") (class "Default")
      (node (ref "D106") (pin "2") (pinfunction "DOUT_2") (pintype "output"))
      (node (ref "D107") (pin "4") (pinfunction "DIN_4") (pintype "input"))
    )
    (net (code "141") (name "Net-(D106-VSS)") (class "Default")
      (node (ref "C115") (pin "1") (pinfunction "~_1") (pintype "unspecified"))
      (node (ref "D106") (pin "3") (pinfunction "VSS_3") (pintype "unspecified"))
      (node (ref "D107") (pin "1") (pinfunction "VDD_1") (pintype "unspecified"))
    )
    (net (code "142") (name "Net-(D107-DOUT)") (class "Default")
      (node (ref "D107") (pin "2") (pinfunction "DOUT_2") (pintype "output"))
      (node (ref "D108") (pin "4") (pinfunction "DIN_4") (pintype "input"))
    )
    (net (code "143") (name "Net-(D107-VSS)") (class "Default")
      (node (ref "C116") (pin "1") (pinfunction "~_1") (pintype "unspecified"))
      (node (ref "D107") (pin "3") (pinfunction "VSS_3") (pintype "unspecified"))
      (node (ref "D108") (pin "1") (pinfunction "VDD_1") (pintype "unspecified"))
    )
    (net (code "144") (name "Net-(D108-DOUT)") (class "Default")
      (node (ref "D108") (pin "2") (pinfunction "DOUT_2") (pintype "output"))
      (node (ref "D109") (pin "4") (pinfunction "DIN_4") (pintype "input"))
    )
    (net (code "145") (name "Net-(D108-VSS)") (class "Default")
      (node (ref "C117") (pin "1") (pinfunction "~_1") (pintype "unspecified"))
      (node (ref "D108") (pin "3") (pinfunction "VSS_3") (pintype "unspecified"))
      (node (ref "D109") (pin "1") (pinfunction "VDD_1") (pintype "unspecified"))
    )
    (net (code "146") (name "Net-(D109-DOUT)") (class "Default")
      (node (ref "D109") (pin "2") (pinfunction "DOUT_2") (pintype "output"))
      (node (ref "D110") (pin "4") (pinfunction "DIN_4") (pintype "input"))
    )
    (net (code "147") (name "Net-(D110-VSS)") (class "Default")
      (node (ref "C118") (pin "1") (pinfunction "~_1") (pintype "unspecified"))
      (node (ref "D110") (pin "3") (pinfunction "VSS_3") (pintype "unspecified"))
      (node (ref "D113") (pin "1") (pinfunction "VDD_1") (pintype "unspecified"))
    )
    (net (code "148") (name "Net-(D111-DIN)") (class "Default")
      (node (ref "D111") (pin "4") (pinfunction "DIN_4") (pintype "input"))
      (node (ref "D112") (pin "2") (pinfunction "DOUT_2") (pintype "output"))
    )
    (net (code "149") (name "Net-(D111-VDD)") (class "Default")
      (node (ref "C120") (pin "1") (pinfunction "~_1") (pintype "unspecified"))
      (node (ref "D111") (pin "1") (pinfunction "VDD_1") (pintype "unspecified"))
      (node (ref "D112") (pin "3") (pinfunction "VSS_3") (pintype "unspecified"))
    )
    (net (code "150") (name "Net-(D112-DIN)") (class "Default")
      (node (ref "D112") (pin "4") (pinfunction "DIN_4") (pintype "input"))
      (node (ref "D113") (pin "2") (pinfunction "DOUT_2") (pintype "output"))
    )
    (net (code "151") (name "Net-(D112-VDD)") (class "Default")
      (node (ref "C119") (pin "1") (pinfunction "~_1") (pintype "unspecified"))
      (node (ref "D112") (pin "1") (pinfunction "VDD_1") (pintype "unspecified"))
      (node (ref "D113") (pin "3") (pinfunction "VSS_3") (pintype "unspecified"))
    )
    (net (code "152") (name "Net-(D114-A)") (class "Default")
      (node (ref "D114") (pin "2") (pinfunction "A_2") (pintype "unspecified"))
      (node (ref "R121") (pin "1") (pinfunction "~_1") (pintype "unspecified"))
    )
    (net (code "153") (name "Net-(D115-A)") (class "Default")
      (node (ref "D115") (pin "2") (pinfunction "A_2") (pintype "unspecified"))
      (node (ref "R124") (pin "1") (pinfunction "~_1") (pintype "unspecified"))
    )
    (net (code "154") (name "Net-(D115-K)") (class "Default")
      (node (ref "D115") (pin "1") (pinfunction "K_1") (pintype "unspecified"))
      (node (ref "R134") (pin "2") (pinfunction "~_2") (pintype "unspecified"))
      (node (ref "U34") (pin "6") (pinfunction "INB-_6") (pintype "unspecified"))
    )
    (net (code "155") (name "Net-(D116-A)") (class "Default")
      (node (ref "D116") (pin "2") (pinfunction "A_2") (pintype "unspecified"))
      (node (ref "R139") (pin "1") (pinfunction "~_1") (pintype "unspecified"))
    )
    (net (code "156") (name "Net-(D117-A)") (class "Default")
      (node (ref "D117") (pin "2") (pinfunction "A_2") (pintype "unspecified"))
      (node (ref "R142") (pin "1") (pinfunction "~_1") (pintype "unspecified"))
    )
    (net (code "157") (name "Net-(D117-K)") (class "Default")
      (node (ref "D117") (pin "1") (pinfunction "K_1") (pintype "unspecified"))
      (node (ref "R152") (pin "2") (pinfunction "~_2") (pintype "unspecified"))
      (node (ref "U39") (pin "6") (pinfunction "INB-_6") (pintype "unspecified"))
    )
    (net (code "158") (name "Net-(J8-Pad2)") (class "Default")
      (node (ref "J8") (pin "2") (pinfunction "2_2") (pintype "unspecified"))
      (node (ref "R102") (pin "2") (pinfunction "~_2") (pintype "unspecified"))
      (node (ref "U27") (pin "2") (pinfunction "2_2") (pintype "unspecified"))
    )
    (net (code "159") (name "Net-(J8-Pad3)") (class "Default")
      (node (ref "J8") (pin "3") (pinfunction "3_3") (pintype "unspecified"))
      (node (ref "R103") (pin "2") (pinfunction "~_2") (pintype "unspecified"))
      (node (ref "U26") (pin "1") (pinfunction "1_1") (pintype "unspecified"))
    )
    (net (code "160") (name "Net-(J9-Pad2)") (class "Default")
      (node (ref "J9") (pin "2") (pinfunction "2_2") (pintype "unspecified"))
      (node (ref "R104") (pin "2") (pinfunction "~_2") (pintype "unspecified"))
      (node (ref "U29") (pin "1") (pinfunction "1_1") (pintype "unspecified"))
    )
    (net (code "161") (name "Net-(J9-Pad3)") (class "Default")
      (node (ref "J9") (pin "3") (pinfunction "3_3") (pintype "unspecified"))
      (node (ref "R105") (pin "2") (pinfunction "~_2") (pintype "unspecified"))
      (node (ref "U28") (pin "1") (pinfunction "1_1") (pintype "unspecified"))
    )
    (net (code "162") (name "Net-(J12-Pad5)") (class "Default")
      (node (ref "J12") (pin "5") (pinfunction "5_5") (pintype "unspecified"))
      (node (ref "J14") (pin "4") (pinfunction "4_4") (pintype "unspecified"))
      (node (ref "R87") (pin "2") (pinfunction "~_2") (pintype "unspecified"))
    )
    (net (code "163") (name "Net-(J13-Pad4)") (class "Default")
      (node (ref "J13") (pin "4") (pinfunction "4_4") (pintype "unspecified"))
      (node (ref "R85") (pin "1") (pinfunction "~_1") (pintype "unspecified"))
    )
    (net (code "164") (name "Net-(J13-Pad5)") (class "Default")
      (node (ref "J13") (pin "5") (pinfunction "5_5") (pintype "unspecified"))
      (node (ref "R86") (pin "1") (pinfunction "~_1") (pintype "unspecified"))
    )
    (net (code "165") (name "Net-(J15-Pad2)") (class "Default")
      (node (ref "J15") (pin "2") (pinfunction "2_2") (pintype "unspecified"))
      (node (ref "R93") (pin "1") (pinfunction "~_1") (pintype "unspecified"))
    )
    (net (code "166") (name "Net-(J15-Pad4)") (class "Default")
      (node (ref "J15") (pin "4") (pinfunction "4_4") (pintype "unspecified"))
      (node (ref "R94") (pin "1") (pinfunction "~_1") (pintype "unspecified"))
    )
    (net (code "167") (name "Net-(J16-Pad2)") (class "Default")
      (node (ref "J16") (pin "2") (pinfunction "2_2") (pintype "unspecified"))
      (node (ref "R125") (pin "2") (pinfunction "~_2") (pintype "unspecified"))
      (node (ref "U31") (pin "2") (pinfunction "2_2") (pintype "unspecified"))
    )
    (net (code "168") (name "Net-(J16-Pad3)") (class "Default")
      (node (ref "J16") (pin "3") (pinfunction "3_3") (pintype "unspecified"))
      (node (ref "R126") (pin "2") (pinfunction "~_2") (pintype "unspecified"))
      (node (ref "U30") (pin "1") (pinfunction "1_1") (pintype "unspecified"))
    )
    (net (code "169") (name "Net-(J17-Pad2)") (class "Default")
      (node (ref "J17") (pin "2") (pinfunction "2_2") (pintype "unspecified"))
      (node (ref "R127") (pin "2") (pinfunction "~_2") (pintype "unspecified"))
      (node (ref "U33") (pin "1") (pinfunction "1_1") (pintype "unspecified"))
    )
    (net (code "170") (name "Net-(J17-Pad3)") (class "Default")
      (node (ref "J17") (pin "3") (pinfunction "3_3") (pintype "unspecified"))
      (node (ref "R128") (pin "2") (pinfunction "~_2") (pintype "unspecified"))
      (node (ref "U32") (pin "1") (pinfunction "1_1") (pintype "unspecified"))
    )
    (net (code "171") (name "Net-(J18-Pad2)") (class "Default")
      (node (ref "J18") (pin "2") (pinfunction "2_2") (pintype "unspecified"))
      (node (ref "R143") (pin "2") (pinfunction "~_2") (pintype "unspecified"))
      (node (ref "U36") (pin "2") (pinfunction "2_2") (pintype "unspecified"))
    )
    (net (code "172") (name "Net-(J18-Pad3)") (class "Default")
      (node (ref "J18") (pin "3") (pinfunction "3_3") (pintype "unspecified"))
      (node (ref "R144") (pin "2") (pinfunction "~_2") (pintype "unspecified"))
      (node (ref "U35") (pin "1") (pinfunction "1_1") (pintype "unspecified"))
    )
    (net (code "173") (name "Net-(J19-Pad2)") (class "Default")
      (node (ref "J19") (pin "2") (pinfunction "2_2") (pintype "unspecified"))
      (node (ref "R145") (pin "2") (pinfunction "~_2") (pintype "unspecified"))
      (node (ref "U38") (pin "1") (pinfunction "1_1") (pintype "unspecified"))
    )
    (net (code "174") (name "Net-(J19-Pad3)") (class "Default")
      (node (ref "J19") (pin "3") (pinfunction "3_3") (pintype "unspecified"))
      (node (ref "R146") (pin "2") (pinfunction "~_2") (pintype "unspecified"))
      (node (ref "U37") (pin "1") (pinfunction "1_1") (pintype "unspecified"))
    )
    (net (code "175") (name "Net-(LEDPWR2-A)") (class "Default")
      (node (ref "LEDPWR2") (pin "2") (pinfunction "A_2") (pintype "input"))
      (node (ref "U24") (pin "23") (pinfunction "23_23") (pintype "bidirectional"))
    )
    (net (code "176") (name "Net-(R96-~-Pad2)") (class "Default")
      (node (ref "R96") (pin "2") (pinfunction "~_2") (pintype "unspecified"))
      (node (ref "U24") (pin "14") (pinfunction "14_14") (pintype "bidirectional"))
    )
    (net (code "177") (name "Net-(R97-~-Pad2)") (class "Default")
      (node (ref "R97") (pin "2") (pinfunction "~_2") (pintype "unspecified"))
      (node (ref "U24") (pin "15") (pinfunction "15_15") (pintype "bidirectional"))
    )
    (net (code "178") (name "Net-(R98-~-Pad2)") (class "Default")
      (node (ref "R98") (pin "2") (pinfunction "~_2") (pintype "unspecified"))
      (node (ref "U24") (pin "16") (pinfunction "16_16") (pintype "bidirectional"))
    )
    (net (code "179") (name "Net-(R99-~-Pad2)") (class "Default")
      (node (ref "R99") (pin "2") (pinfunction "~_2") (pintype "unspecified"))
      (node (ref "U24") (pin "17") (pinfunction "17_17") (pintype "bidirectional"))
    )
    (net (code "180") (name "Net-(R100-~-Pad2)") (class "Default")
      (node (ref "R100") (pin "2") (pinfunction "~_2") (pintype "unspecified"))
      (node (ref "U24") (pin "20") (pinfunction "20_20") (pintype "bidirectional"))
    )
    (net (code "181") (name "Net-(R101-~-Pad2)") (class "Default")
      (node (ref "R101") (pin "2") (pinfunction "~_2") (pintype "unspecified"))
      (node (ref "U24") (pin "21") (pinfunction "21_21") (pintype "bidirectional"))
    )
    (net (code "182") (name "Net-(R102-~-Pad1)") (class "Default")
      (node (ref "R102") (pin "1") (pinfunction "~_1") (pintype "unspecified"))
      (node (ref "R103") (pin "1") (pinfunction "~_1") (pintype "unspecified"))
      (node (ref "R114") (pin "1") (pinfunction "1_1") (pintype "input"))
    )
    (net (code "183") (name "Net-(R104-~-Pad1)") (class "Default")
      (node (ref "R104") (pin "1") (pinfunction "~_1") (pintype "unspecified"))
      (node (ref "R105") (pin "1") (pinfunction "~_1") (pintype "unspecified"))
      (node (ref "R119") (pin "1") (pinfunction "1_1") (pintype "input"))
    )
    (net (code "184") (name "Net-(R125-~-Pad1)") (class "Default")
      (node (ref "R125") (pin "1") (pinfunction "~_1") (pintype "unspecified"))
      (node (ref "R126") (pin "1") (pinfunction "~_1") (pintype "unspecified"))
      (node (ref "R130") (pin "1") (pinfunction "1_1") (pintype "input"))
    )
    (net (code "185") (name "Net-(R127-~-Pad1)") (class "Default")
      (node (ref "R127") (pin "1") (pinfunction "~_1") (pintype "unspecified"))
      (node (ref "R128") (pin "1") (pinfunction "~_1") (pintype "unspecified"))
      (node (ref "R137") (pin "1") (pinfunction "1_1") (pintype "input"))
    )
    (net (code "186") (name "Net-(R143-~-Pad1)") (class "Default")
      (node (ref "R143") (pin "1") (pinfunction "~_1") (pintype "unspecified"))
      (node (ref "R144") (pin "1") (pinfunction "~_1") (pintype "unspecified"))
      (node (ref "R148") (pin "1") (pinfunction "1_1") (pintype "input"))
    )
    (net (code "187") (name "Net-(R145-~-Pad1)") (class "Default")
      (node (ref "R145") (pin "1") (pinfunction "~_1") (pintype "unspecified"))
      (node (ref "R146") (pin "1") (pinfunction "~_1") (pintype "unspecified"))
      (node (ref "R155") (pin "1") (pinfunction "1_1") (pintype "input"))
    )
    (net (code "188") (name "Net-(U8-1Y)") (class "Default")
      (node (ref "R20") (pin "1") (pinfunction "~_1") (pintype "unspecified"))
      (node (ref "U8") (pin "3") (pinfunction "1Y_3") (pintype "unspecified"))
    )
    (net (code "189") (name "Net-(U23A-INA+)") (class "Default")
      (node (ref "C122") (pin "2") (pinfunction "2_2") (pintype "unspecified"))
      (node (ref "R115") (pin "1") (pinfunction "~_1") (pintype "unspecified"))
      (node (ref "U23") (pin "3") (pinfunction "INA+_3") (pintype "unspecified"))
    )
    (net (code "190") (name "Net-(U23A-OUTA)") (class "Default")
      (node (ref "R116") (pin "1") (pinfunction "~_1") (pintype "unspecified"))
      (node (ref "R62") (pin "2") (pinfunction "~_2") (pintype "unspecified"))
      (node (ref "U23") (pin "1") (pinfunction "OUTA_1") (pintype "output"))
    )
    (net (code "191") (name "Net-(U23B-INB+)") (class "Default")
      (node (ref "C123") (pin "2") (pinfunction "2_2") (pintype "unspecified"))
      (node (ref "R118") (pin "1") (pinfunction "~_1") (pintype "unspecified"))
      (node (ref "U23") (pin "5") (pinfunction "INB+_5") (pintype "unspecified"))
    )
    (net (code "192") (name "Net-(U23B-OUTB)") (class "Default")
      (node (ref "R117") (pin "1") (pinfunction "~_1") (pintype "unspecified"))
      (node (ref "R66") (pin "2") (pinfunction "~_2") (pintype "unspecified"))
      (node (ref "U23") (pin "7") (pinfunction "OUTB_7") (pintype "output"))
    )
    (net (code "193") (name "Net-(U34A-INA+)") (class "Default")
      (node (ref "C129") (pin "2") (pinfunction "2_2") (pintype "unspecified"))
      (node (ref "R131") (pin "1") (pinfunction "~_1") (pintype "unspecified"))
      (node (ref "U34") (pin "3") (pinfunction "INA+_3") (pintype "unspecified"))
    )
    (net (code "194") (name "Net-(U34A-OUTA)") (class "Default")
      (node (ref "R121") (pin "2") (pinfunction "~_2") (pintype "unspecified"))
      (node (ref "R133") (pin "1") (pinfunction "~_1") (pintype "unspecified"))
      (node (ref "U34") (pin "1") (pinfunction "OUTA_1") (pintype "output"))
    )
    (net (code "195") (name "Net-(U34B-INB+)") (class "Default")
      (node (ref "C130") (pin "2") (pinfunction "2_2") (pintype "unspecified"))
      (node (ref "R136") (pin "1") (pinfunction "~_1") (pintype "unspecified"))
      (node (ref "U34") (pin "5") (pinfunction "INB+_5") (pintype "unspecified"))
    )
    (net (code "196") (name "Net-(U34B-OUTB)") (class "Default")
      (node (ref "R124") (pin "2") (pinfunction "~_2") (pintype "unspecified"))
      (node (ref "R135") (pin "1") (pinfunction "~_1") (pintype "unspecified"))
      (node (ref "U34") (pin "7") (pinfunction "OUTB_7") (pintype "output"))
    )
    (net (code "197") (name "Net-(U39A-INA+)") (class "Default")
      (node (ref "C136") (pin "2") (pinfunction "2_2") (pintype "unspecified"))
      (node (ref "R149") (pin "1") (pinfunction "~_1") (pintype "unspecified"))
      (node (ref "U39") (pin "3") (pinfunction "INA+_3") (pintype "unspecified"))
    )
    (net (code "198") (name "Net-(U39A-OUTA)") (class "Default")
      (node (ref "R139") (pin "2") (pinfunction "~_2") (pintype "unspecified"))
      (node (ref "R151") (pin "1") (pinfunction "~_1") (pintype "unspecified"))
      (node (ref "U39") (pin "1") (pinfunction "OUTA_1") (pintype "output"))
    )
    (net (code "199") (name "Net-(U39B-INB+)") (class "Default")
      (node (ref "C137") (pin "2") (pinfunction "2_2") (pintype "unspecified"))
      (node (ref "R154") (pin "1") (pinfunction "~_1") (pintype "unspecified"))
      (node (ref "U39") (pin "5") (pinfunction "INB+_5") (pintype "unspecified"))
    )
    (net (code "200") (name "Net-(U39B-OUTB)") (class "Default")
      (node (ref "R142") (pin "2") (pinfunction "~_2") (pintype "unspecified"))
      (node (ref "R153") (pin "1") (pinfunction "~_1") (pintype "unspecified"))
      (node (ref "U39") (pin "7") (pinfunction "OUTB_7") (pintype "output"))
    )
    (net (code "201") (name "ROW1") (class "Default")
      (node (ref "ROW_MUX2") (pin "9") (pinfunction "I0_9") (pintype "unspecified"))
      (node (ref "SW1") (pin "1") (pinfunction "1_1") (pintype "unspecified"))
      (node (ref "SW15") (pin "1") (pinfunction "1_1") (pintype "unspecified"))
      (node (ref "SW22") (pin "1") (pinfunction "1_1") (pintype "unspecified"))
      (node (ref "SW29") (pin "1") (pinfunction "1_1") (pintype "unspecified"))
      (node (ref "SW36") (pin "1") (pinfunction "1_1") (pintype "unspecified"))
      (node (ref "SW8") (pin "1") (pinfunction "1_1") (pintype "unspecified"))
    )
    (net (code "202") (name "ROW2") (class "Default")
      (node (ref "ROW_MUX2") (pin "8") (pinfunction "I1_8") (pintype "unspecified"))
      (node (ref "SW16") (pin "1") (pinfunction "1_1") (pintype "unspecified"))
      (node (ref "SW2") (pin "1") (pinfunction "1_1") (pintype "unspecified"))
      (node (ref "SW23") (pin "1") (pinfunction "1_1") (pintype "unspecified"))
      (node (ref "SW30") (pin "1") (pinfunction "1_1") (pintype "unspecified"))
      (node (ref "SW37") (pin "1") (pinfunction "1_1") (pintype "unspecified"))
      (node (ref "SW9") (pin "1") (pinfunction "1_1") (pintype "unspecified"))
    )
    (net (code "203") (name "ROW3") (class "Default")
      (node (ref "ROW_MUX2") (pin "7") (pinfunction "I2_7") (pintype "unspecified"))
      (node (ref "SW10") (pin "1") (pinfunction "1_1") (pintype "unspecified"))
      (node (ref "SW17") (pin "1") (pinfunction "1_1") (pintype "unspecified"))
      (node (ref "SW24") (pin "1") (pinfunction "1_1") (pintype "unspecified"))
      (node (ref "SW3") (pin "1") (pinfunction "1_1") (pintype "unspecified"))
      (node (ref "SW31") (pin "1") (pinfunction "1_1") (pintype "unspecified"))
      (node (ref "SW38") (pin "1") (pinfunction "1_1") (pintype "unspecified"))
    )
    (net (code "204") (name "ROW4") (class "Default")
      (node (ref "ROW_MUX2") (pin "6") (pinfunction "I3_6") (pintype "unspecified"))
      (node (ref "SW11") (pin "1") (pinfunction "1_1") (pintype "unspecified"))
      (node (ref "SW18") (pin "1") (pinfunction "1_1") (pintype "unspecified"))
      (node (ref "SW25") (pin "1") (pinfunction "1_1") (pintype "unspecified"))
      (node (ref "SW32") (pin "1") (pinfunction "1_1") (pintype "unspecified"))
      (node (ref "SW39") (pin "1") (pinfunction "1_1") (pintype "unspecified"))
      (node (ref "SW4") (pin "1") (pinfunction "1_1") (pintype "unspecified"))
    )
    (net (code "205") (name "ROW5") (class "Default")
      (node (ref "ROW_MUX2") (pin "4") (pinfunction "I5_4") (pintype "unspecified"))
      (node (ref "ROW_MUX2") (pin "5") (pinfunction "I4_5") (pintype "unspecified"))
      (node (ref "SW12") (pin "1") (pinfunction "1_1") (pintype "unspecified"))
      (node (ref "SW19") (pin "1") (pinfunction "1_1") (pintype "unspecified"))
      (node (ref "SW26") (pin "1") (pinfunction "1_1") (pintype "unspecified"))
      (node (ref "SW33") (pin "1") (pinfunction "1_1") (pintype "unspecified"))
      (node (ref "SW40") (pin "1") (pinfunction "1_1") (pintype "unspecified"))
      (node (ref "SW5") (pin "1") (pinfunction "1_1") (pintype "unspecified"))
    )
    (net (code "206") (name "ROW6") (class "Default")
      (node (ref "ROW_MUX2") (pin "3") (pinfunction "I6_3") (pintype "unspecified"))
      (node (ref "SW13") (pin "1") (pinfunction "1_1") (pintype "unspecified"))
      (node (ref "SW20") (pin "1") (pinfunction "1_1") (pintype "unspecified"))
      (node (ref "SW27") (pin "1") (pinfunction "1_1") (pintype "unspecified"))
      (node (ref "SW34") (pin "1") (pinfunction "1_1") (pintype "unspecified"))
      (node (ref "SW41") (pin "1") (pinfunction "1_1") (pintype "unspecified"))
      (node (ref "SW6") (pin "1") (pinfunction "1_1") (pintype "unspecified"))
    )
    (net (code "207") (name "ROW7") (class "Default")
      (node (ref "ROW_MUX2") (pin "2") (pinfunction "I7_2") (pintype "unspecified"))
      (node (ref "SW14") (pin "1") (pinfunction "1_1") (pintype "unspecified"))
      (node (ref "SW21") (pin "1") (pinfunction "1_1") (pintype "unspecified"))
      (node (ref "SW28") (pin "1") (pinfunction "1_1") (pintype "unspecified"))
      (node (ref "SW35") (pin "1") (pinfunction "1_1") (pintype "unspecified"))
      (node (ref "SW42") (pin "1") (pinfunction "1_1") (pintype "unspecified"))
      (node (ref "SW7") (pin "1") (pinfunction "1_1") (pintype "unspecified"))
    )
    (net (code "208") (name "SCL") (class "Default")
      (node (ref "R91") (pin "1") (pinfunction "~_1") (pintype "unspecified"))
      (node (ref "R92") (pin "2") (pinfunction "~_2") (pintype "unspecified"))
      (node (ref "Screen2") (pin "3") (pinfunction "Pin_3_3") (pintype "unspecified"))
      (node (ref "U24") (pin "19") (pinfunction "19_19") (pintype "bidirectional"))
    )
    (net (code "209") (name "SDA") (class "Default")
      (node (ref "R91") (pin "2") (pinfunction "~_2") (pintype "unspecified"))
      (node (ref "Screen2") (pin "4") (pinfunction "Pin_4_4") (pintype "unspecified"))
      (node (ref "U24") (pin "18") (pinfunction "18_18") (pintype "bidirectional"))
    )
    (net (code "210") (name "TPWR") (class "Default")
      (node (ref "SW49") (pin "2") (pinfunction "2_2") (pintype "unspecified"))
      (node (ref "U24") (pin "VIN") (pinfunction "VIN_VIN") (pintype "unspecified"))
    )
    (net (code "211") (name "VIN_FUSED") (class "Default")
      (node (ref "C5") (pin "2") (pinfunction "2_2") (pintype "input"))
      (node (ref "C6") (pin "2") (pinfunction "2_2") (pintype "unspecified"))
      (node (ref "D44") (pin "1") (pinfunction "K_1") (pintype "input"))
      (node (ref "F1") (pin "2") (pinfunction "2_2") (pintype "unspecified"))
      (node (ref "SW49") (pin "4") (pinfunction "4_4") (pintype "unspecified"))
      (node (ref "SW49") (pin "6") (pinfunction "6_6") (pintype "unspecified"))
      (node (ref "U6") (pin "1") (pinfunction "1_1") (pintype "unspecified"))
    )
    (net (code "212") (name "VIN_RAW") (class "Default")
      (node (ref "F1") (pin "1") (pinfunction "1_1") (pintype "unspecified"))
      (node (ref "J1") (pin "1") (pinfunction "1_1") (pintype "unspecified"))
    )
    (net (code "213") (name "VLED") (class "Default")
      (node (ref "C121") (pin "1") (pinfunction "1_1") (pintype "input"))
      (node (ref "C61") (pin "1") (pinfunction "~_1") (pintype "unspecified"))
      (node (ref "C7") (pin "2") (pinfunction "2_2") (pintype "unspecified"))
      (node (ref "C76") (pin "1") (pinfunction "~_1") (pintype "unspecified"))
      (node (ref "D110") (pin "1") (pinfunction "VDD_1") (pintype "unspecified"))
      (node (ref "D61") (pin "1") (pinfunction "VDD_1") (pintype "unspecified"))
      (node (ref "U6") (pin "2") (pinfunction "2_2") (pintype "unspecified"))
    )
    (net (code "214") (name "VREF") (class "Default")
      (node (ref "C124") (pin "2") (pinfunction "2_2") (pintype "input"))
      (node (ref "C127") (pin "2") (pinfunction "2_2") (pintype "input"))
      (node (ref "C131") (pin "2") (pinfunction "2_2") (pintype "input"))
      (node (ref "C134") (pin "2") (pinfunction "2_2") (pintype "input"))
      (node (ref "C48") (pin "2") (pinfunction "2_2") (pintype "input"))
      (node (ref "C51") (pin "2") (pinfunction "2_2") (pintype "input"))
      (node (ref "R115") (pin "2") (pinfunction "~_2") (pintype "unspecified"))
      (node (ref "R118") (pin "2") (pinfunction "~_2") (pintype "unspecified"))
      (node (ref "R120") (pin "2") (pinfunction "~_2") (pintype "unspecified"))
      (node (ref "R122") (pin "1") (pinfunction "~_1") (pintype "unspecified"))
      (node (ref "R123") (pin "2") (pinfunction "~_2") (pintype "unspecified"))
      (node (ref "R129") (pin "1") (pinfunction "~_1") (pintype "unspecified"))
      (node (ref "R131") (pin "2") (pinfunction "~_2") (pintype "unspecified"))
      (node (ref "R132") (pin "1") (pinfunction "~_1") (pintype "unspecified"))
      (node (ref "R134") (pin "1") (pinfunction "~_1") (pintype "unspecified"))
      (node (ref "R136") (pin "2") (pinfunction "~_2") (pintype "unspecified"))
      (node (ref "R138") (pin "2") (pinfunction "~_2") (pintype "unspecified"))
      (node (ref "R140") (pin "1") (pinfunction "~_1") (pintype "unspecified"))
      (node (ref "R141") (pin "2") (pinfunction "~_2") (pintype "unspecified"))
      (node (ref "R147") (pin "1") (pinfunction "~_1") (pintype "unspecified"))
      (node (ref "R149") (pin "2") (pinfunction "~_2") (pintype "unspecified"))
      (node (ref "R150") (pin "1") (pinfunction "~_1") (pintype "unspecified"))
      (node (ref "R152") (pin "1") (pinfunction "~_1") (pintype "unspecified"))
      (node (ref "R154") (pin "2") (pinfunction "~_2") (pintype "unspecified"))
      (node (ref "R60") (pin "1") (pinfunction "~_1") (pintype "unspecified"))
      (node (ref "R61") (pin "2") (pinfunction "~_2") (pintype "unspecified"))
      (node (ref "R63") (pin "1") (pinfunction "~_1") (pintype "unspecified"))
      (node (ref "R64") (pin "1") (pinfunction "~_1") (pintype "unspecified"))
      (node (ref "R65") (pin "2") (pinfunction "~_2") (pintype "unspecified"))
      (node (ref "R67") (pin "1") (pinfunction "~_1") (pintype "unspecified"))
      (node (ref "R89") (pin "2") (pinfunction "~_2") (pintype "unspecified"))
      (node (ref "R90") (pin "2") (pinfunction "~_2") (pintype "unspecified"))
    )
    (net (code "215") (name "unconnected-(D104-VDD-Pad1)") (class "Default")
      (node (ref "D104") (pin "1") (pinfunction "VDD_1") (pintype "unspecified"))
    )
    (net (code "216") (name "unconnected-(J12-Pad1)") (class "Default")
      (node (ref "J12") (pin "1") (pinfunction "1_1") (pintype "unspecified"))
    )
    (net (code "217") (name "unconnected-(J12-Pad3)") (class "Default")
      (node (ref "J12") (pin "3") (pinfunction "3_3") (pintype "unspecified+no_connect"))
    )
    (net (code "218") (name "unconnected-(J12-Pad6)") (class "Default")
      (node (ref "J12") (pin "6") (pinfunction "6_6") (pintype "unspecified+no_connect"))
    )
    (net (code "219") (name "unconnected-(J12-Pad7)") (class "Default")
      (node (ref "J12") (pin "7") (pinfunction "7_7") (pintype "unspecified+no_connect"))
    )
    (net (code "220") (name "unconnected-(J13-Pad1)") (class "Default")
      (node (ref "J13") (pin "1") (pinfunction "1_1") (pintype "unspecified+no_connect"))
    )
    (net (code "221") (name "unconnected-(J13-Pad3)") (class "Default")
      (node (ref "J13") (pin "3") (pinfunction "3_3") (pintype "unspecified+no_connect"))
    )
    (net (code "222") (name "unconnected-(J13-Pad6)") (class "Default")
      (node (ref "J13") (pin "6") (pinfunction "6_6") (pintype "unspecified+no_connect"))
    )
    (net (code "223") (name "unconnected-(J13-Pad7)") (class "Default")
      (node (ref "J13") (pin "7") (pinfunction "7_7") (pintype "unspecified+no_connect"))
    )
    (net (code "224") (name "unconnected-(U24-ON{slash}OFF-PadON-OFF)") (class "Default")
      (node (ref "U24") (pin "ON-OFF") (pinfunction "ON/OFF_ON-OFF") (pintype "bidirectional+no_connect"))
    )
    (net (code "225") (name "unconnected-(U24-PROGRAM-PadPGM)") (class "Default")
      (node (ref "U24") (pin "PGM") (pinfunction "PROGRAM_PGM") (pintype "bidirectional+no_connect"))
    )
    (net (code "226") (name "unconnected-(U24-Pad12)") (class "Default")
      (node (ref "U24") (pin "12") (pinfunction "12_12") (pintype "bidirectional+no_connect"))
    )
    (net (code "227") (name "unconnected-(U24-Pad13)") (class "Default")
      (node (ref "U24") (pin "13") (pinfunction "13_13") (pintype "bidirectional+no_connect"))
    )
    (net (code "228") (name "unconnected-(U24-PadVBAT)") (class "Default")
      (node (ref "U24") (pin "VBAT") (pinfunction "VBAT_VBAT") (pintype "unspecified+no_connect"))
    )
    (net (code "229") (name "unconnected-(U25-NC-Pad1)") (class "Default")
      (node (ref "U25") (pin "1") (pinfunction "NC_1") (pintype "unspecified+no_connect"))
    )
    (net (code "230") (name "unconnected-(U25-NC-Pad4)") (class "Default")
      (node (ref "U25") (pin "4") (pinfunction "NC_4") (pintype "unspecified+no_connect"))
    )
  )
)
